# PX4FMUv2_3.net
KiCad netlist of a schematic drawn in EAGLE
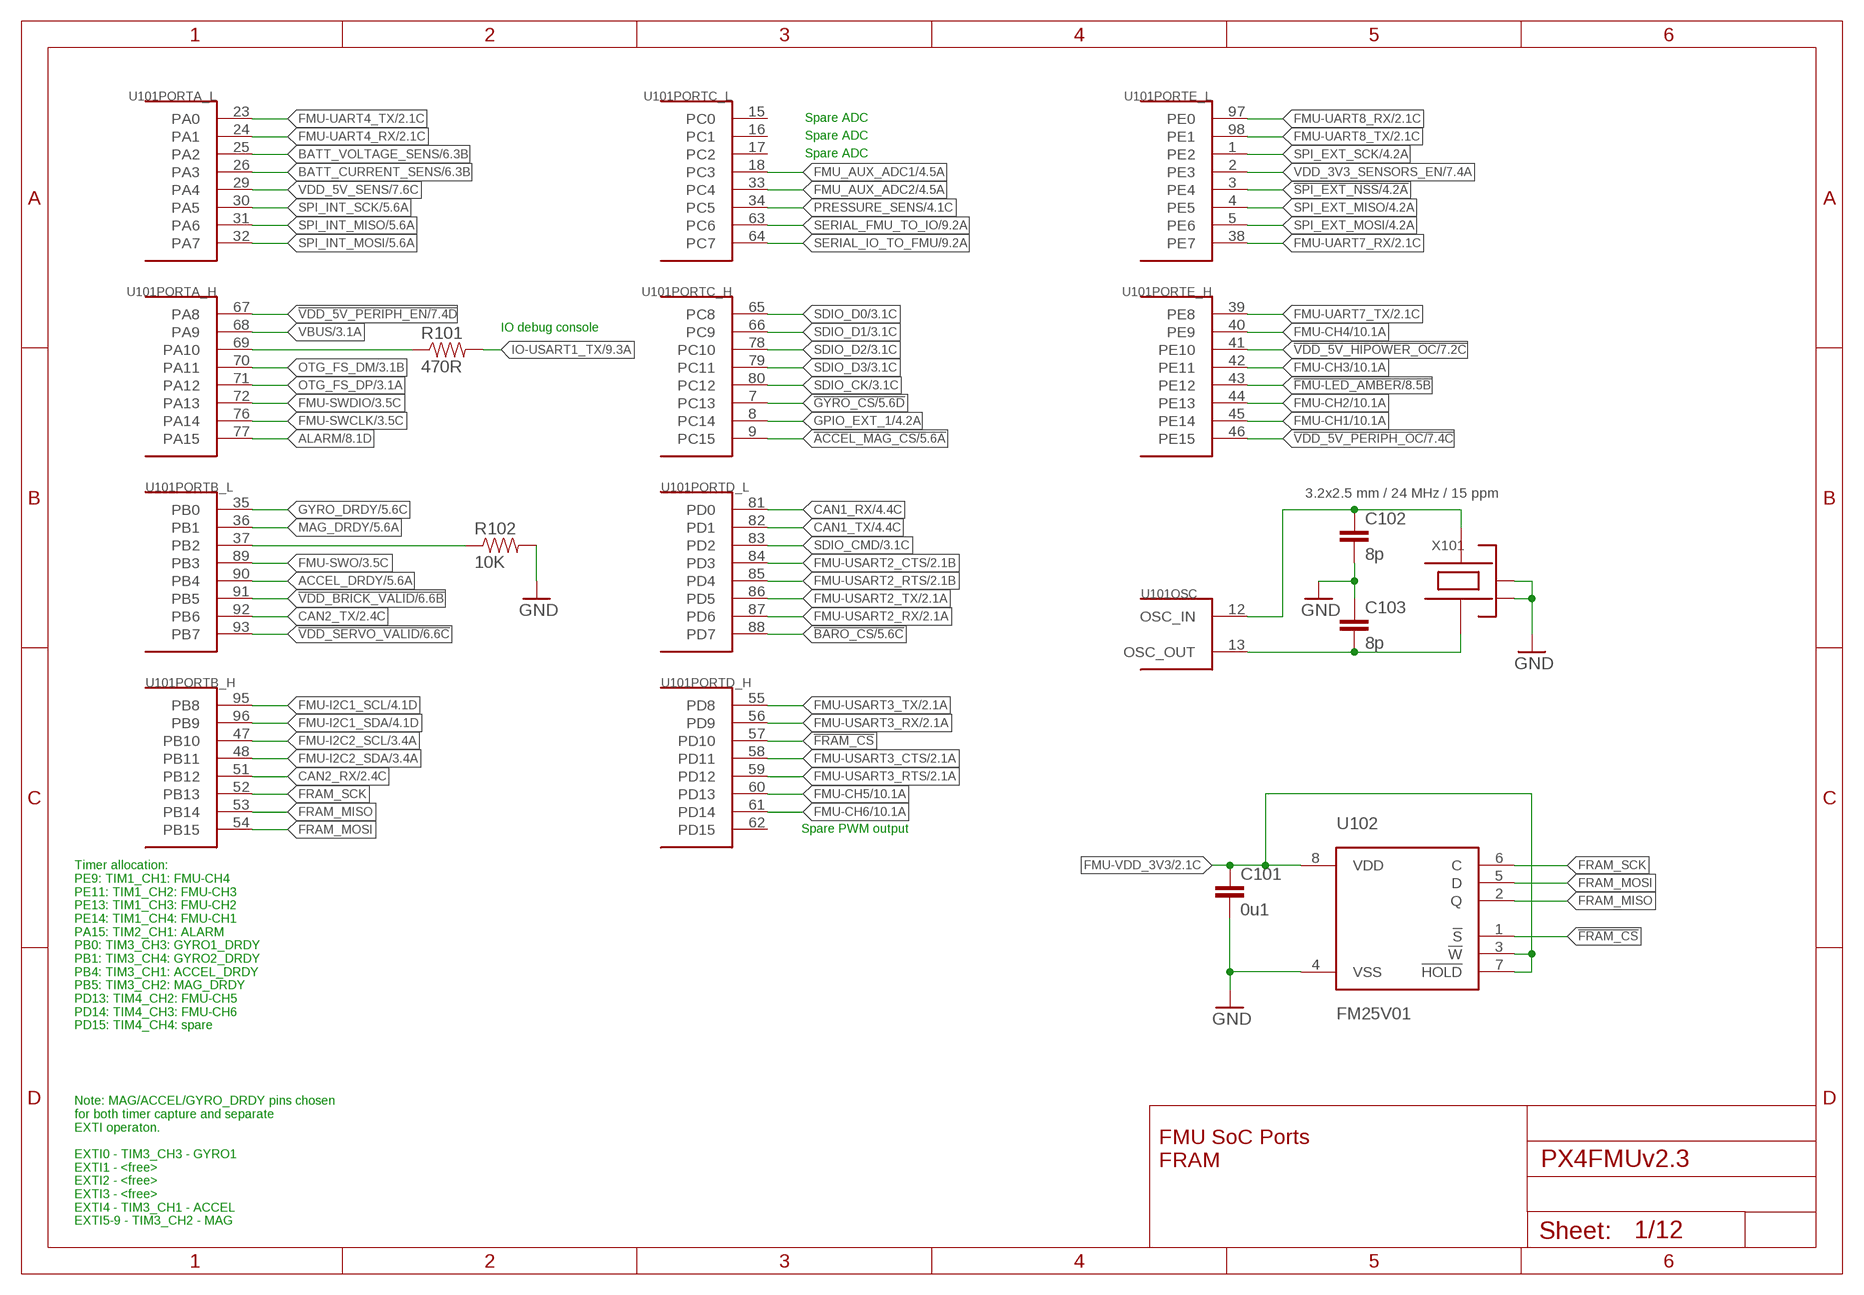
[diagram p0: schematic, sheet 1]
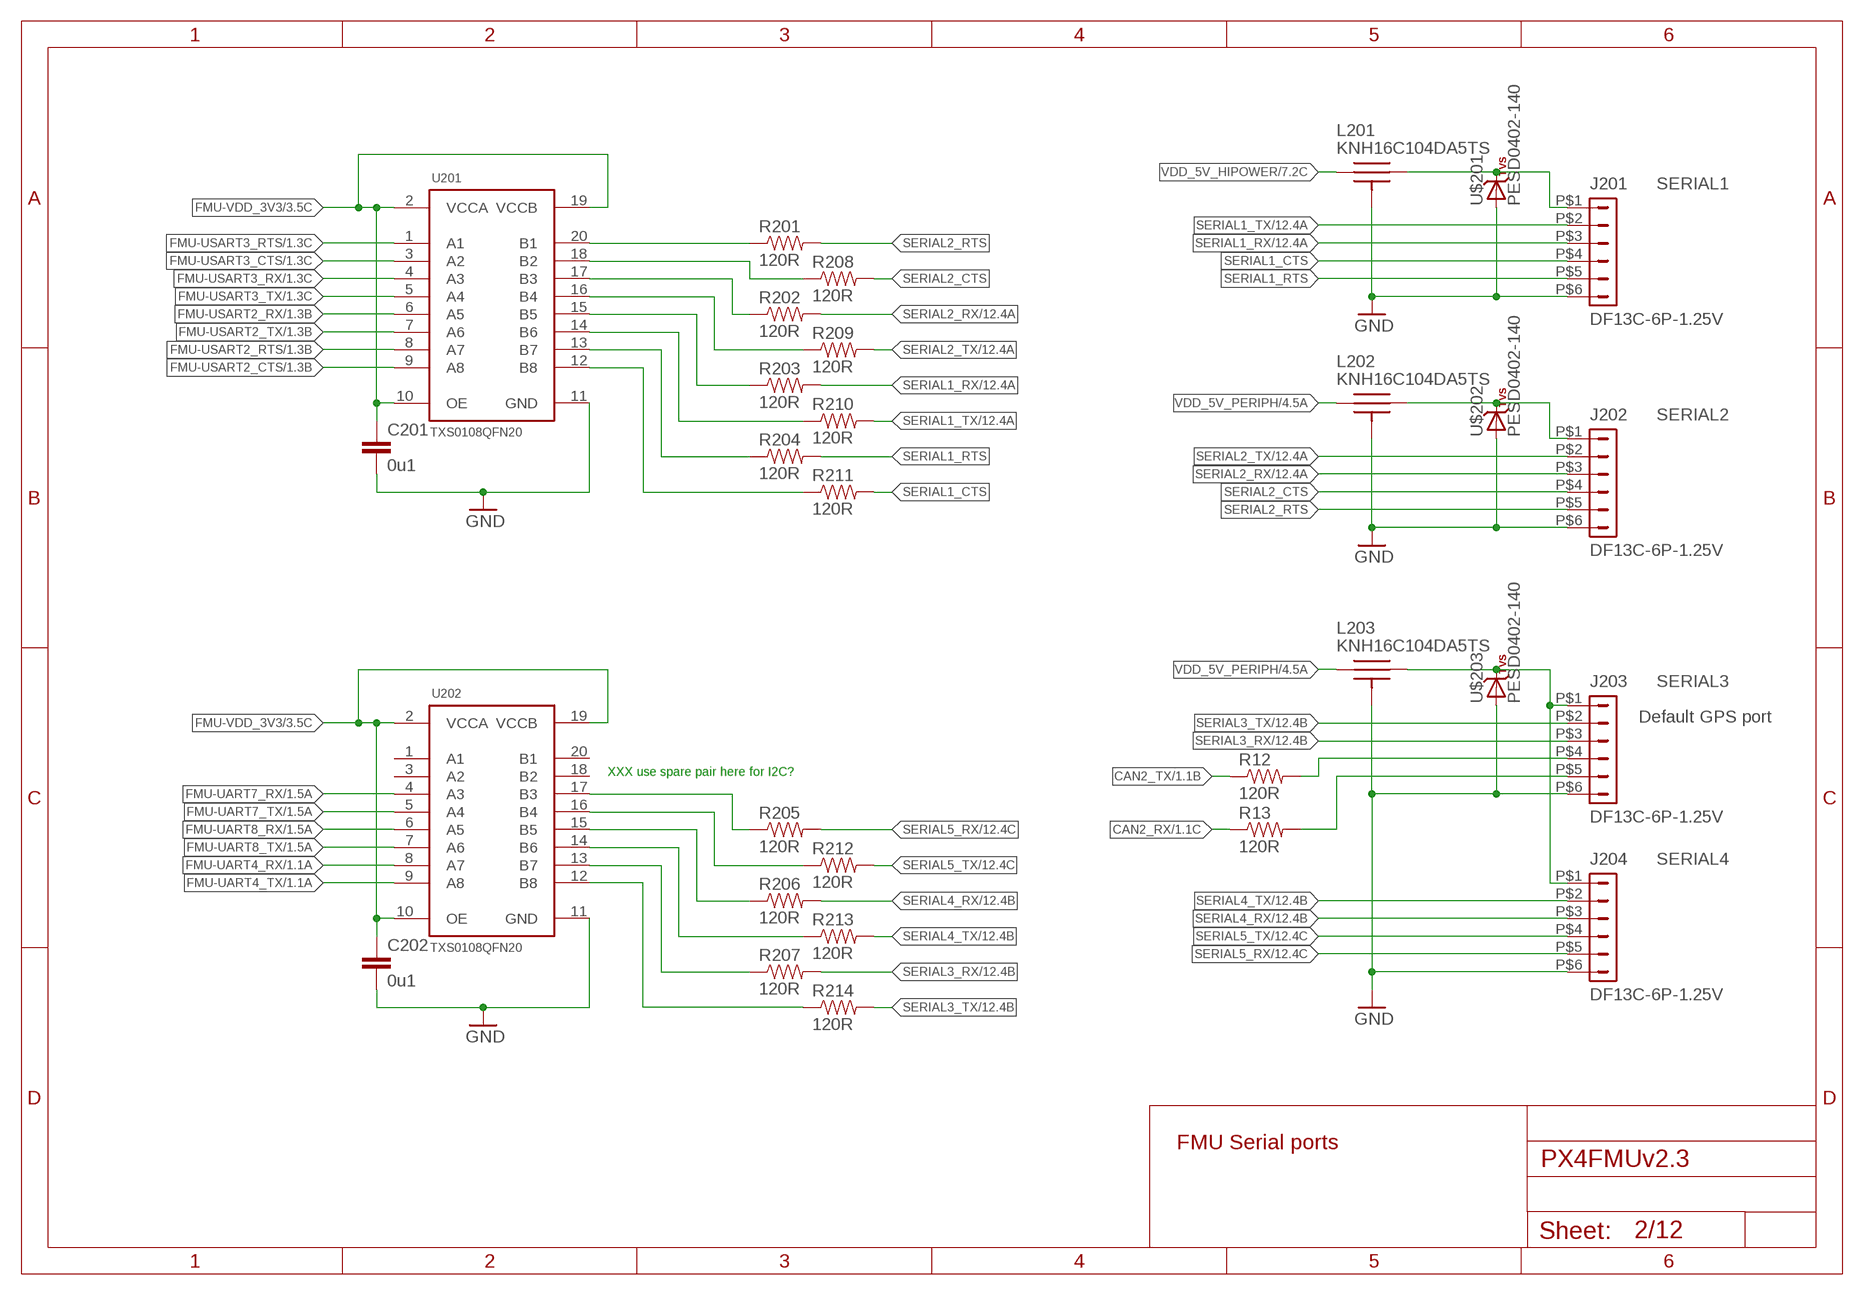
[diagram p1: schematic, sheet 2]
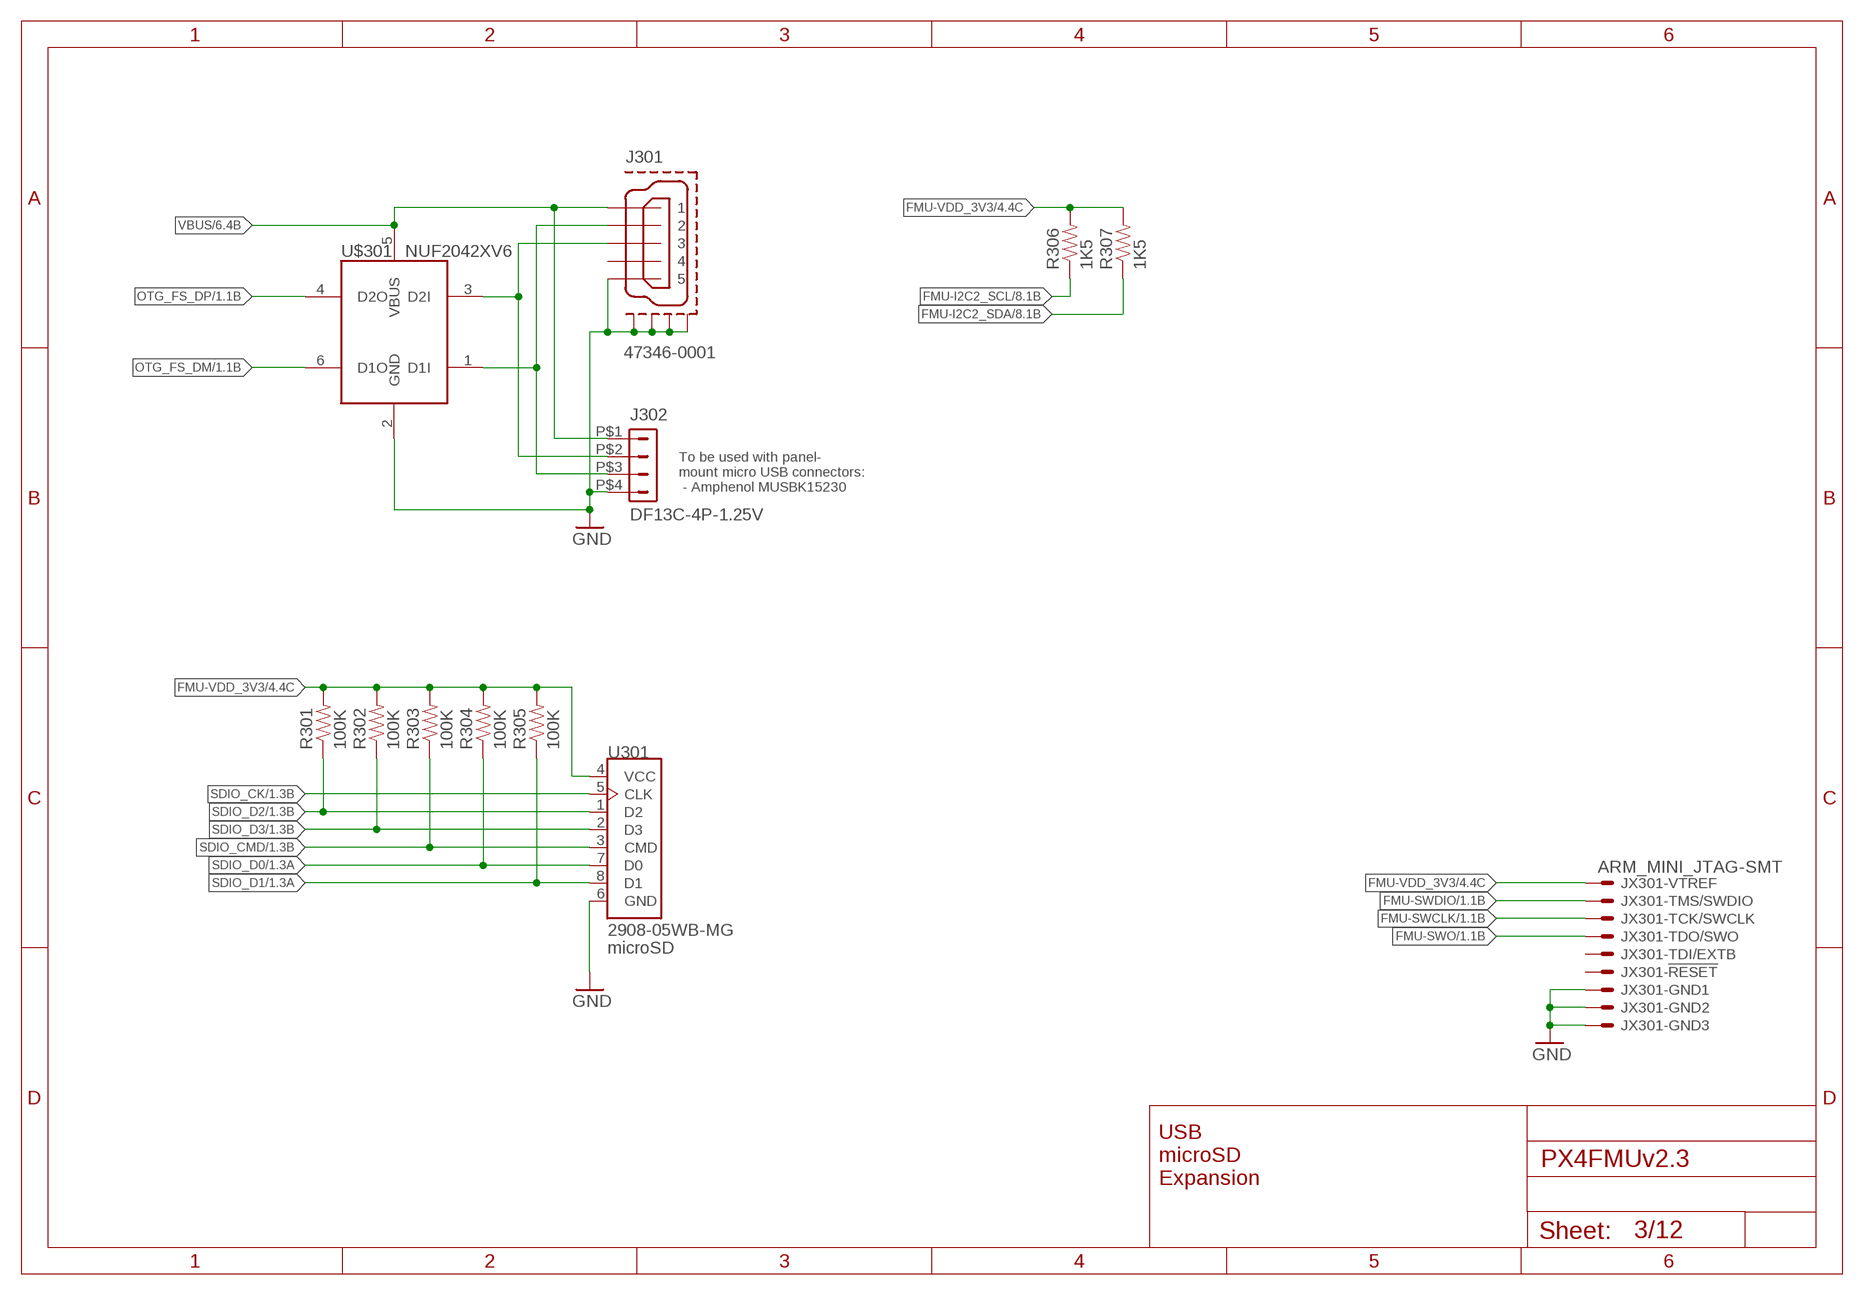
[diagram p2: schematic, sheet 3]
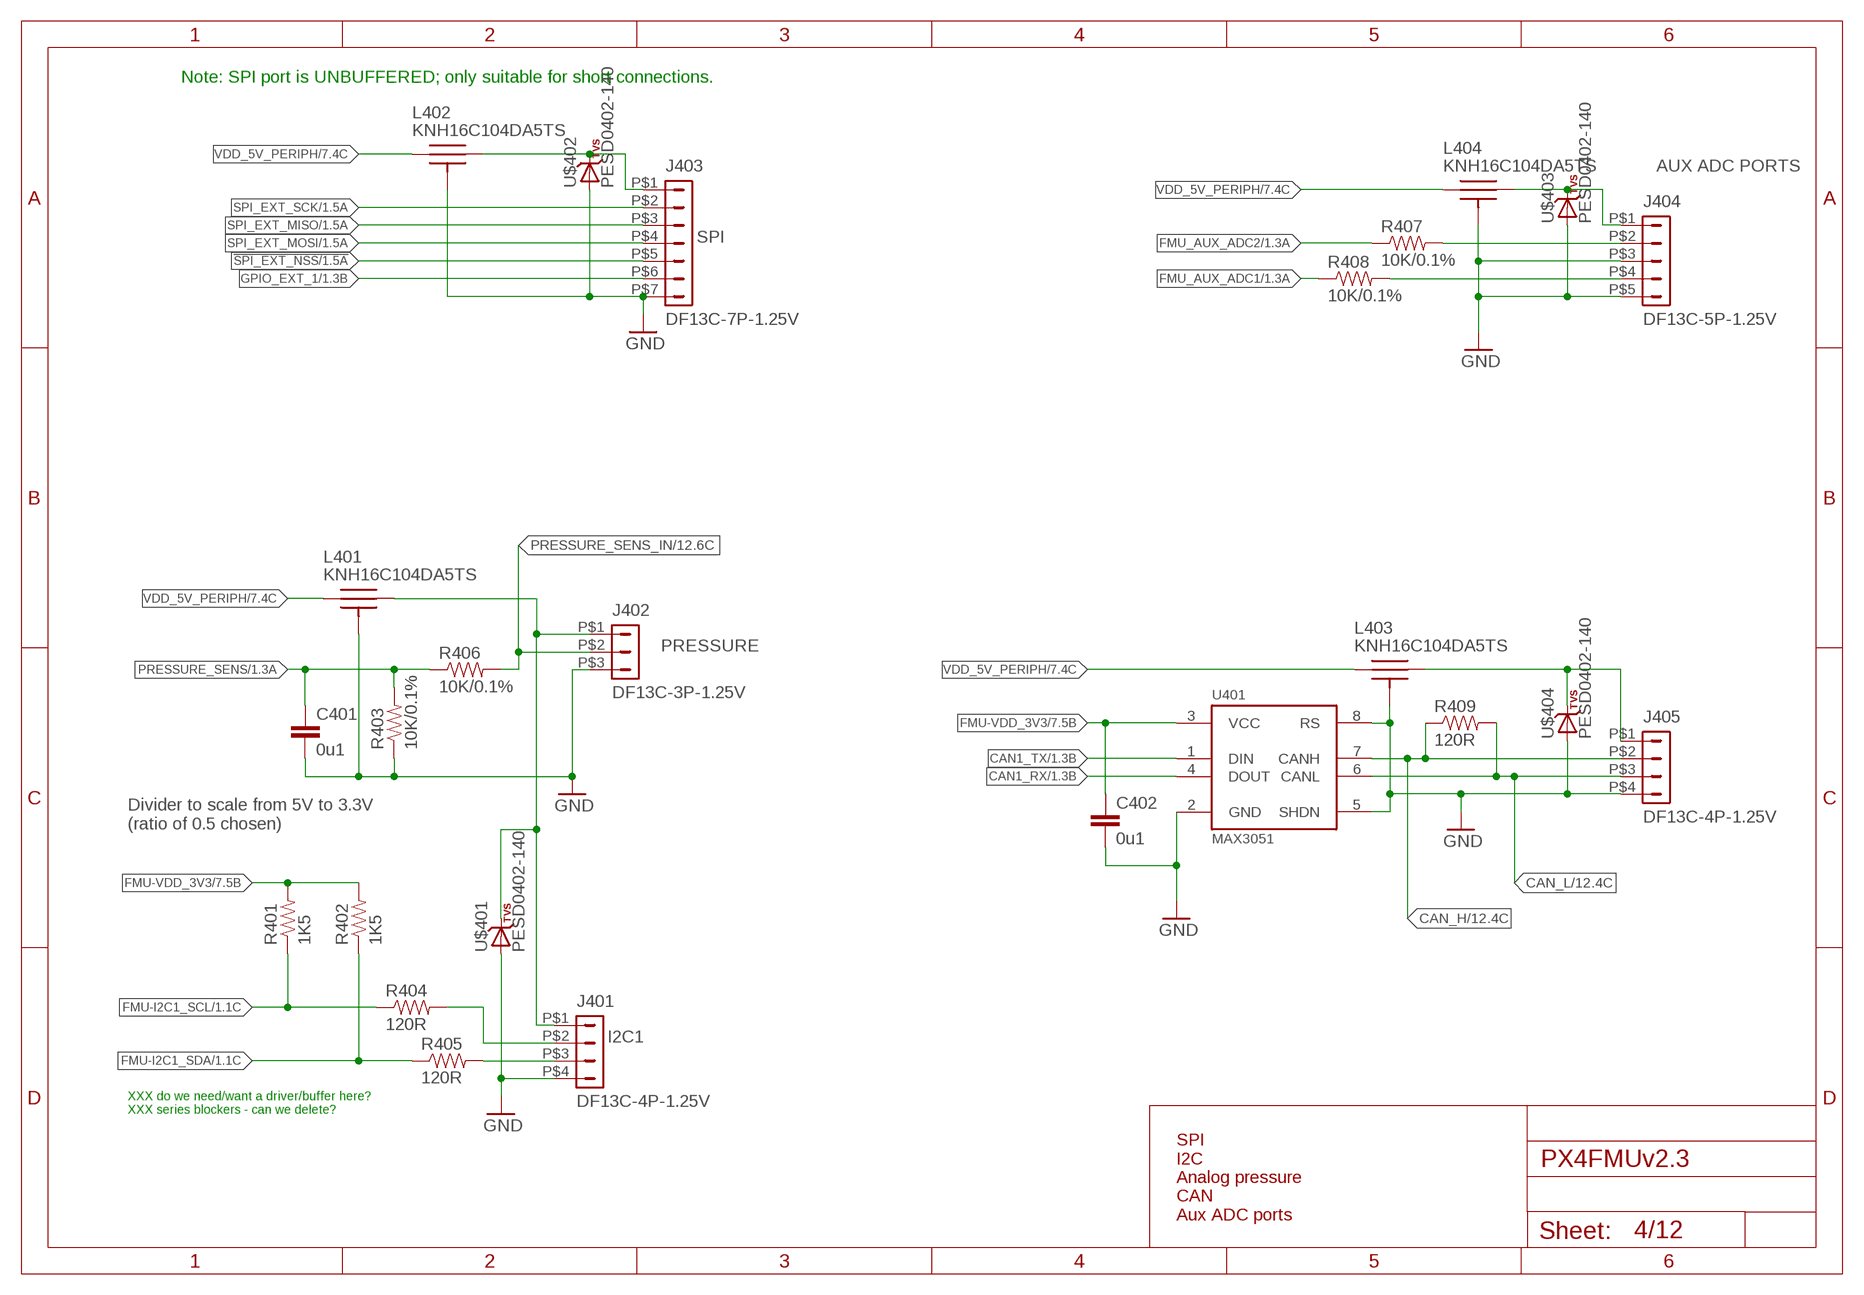
[diagram p3: schematic, sheet 4]
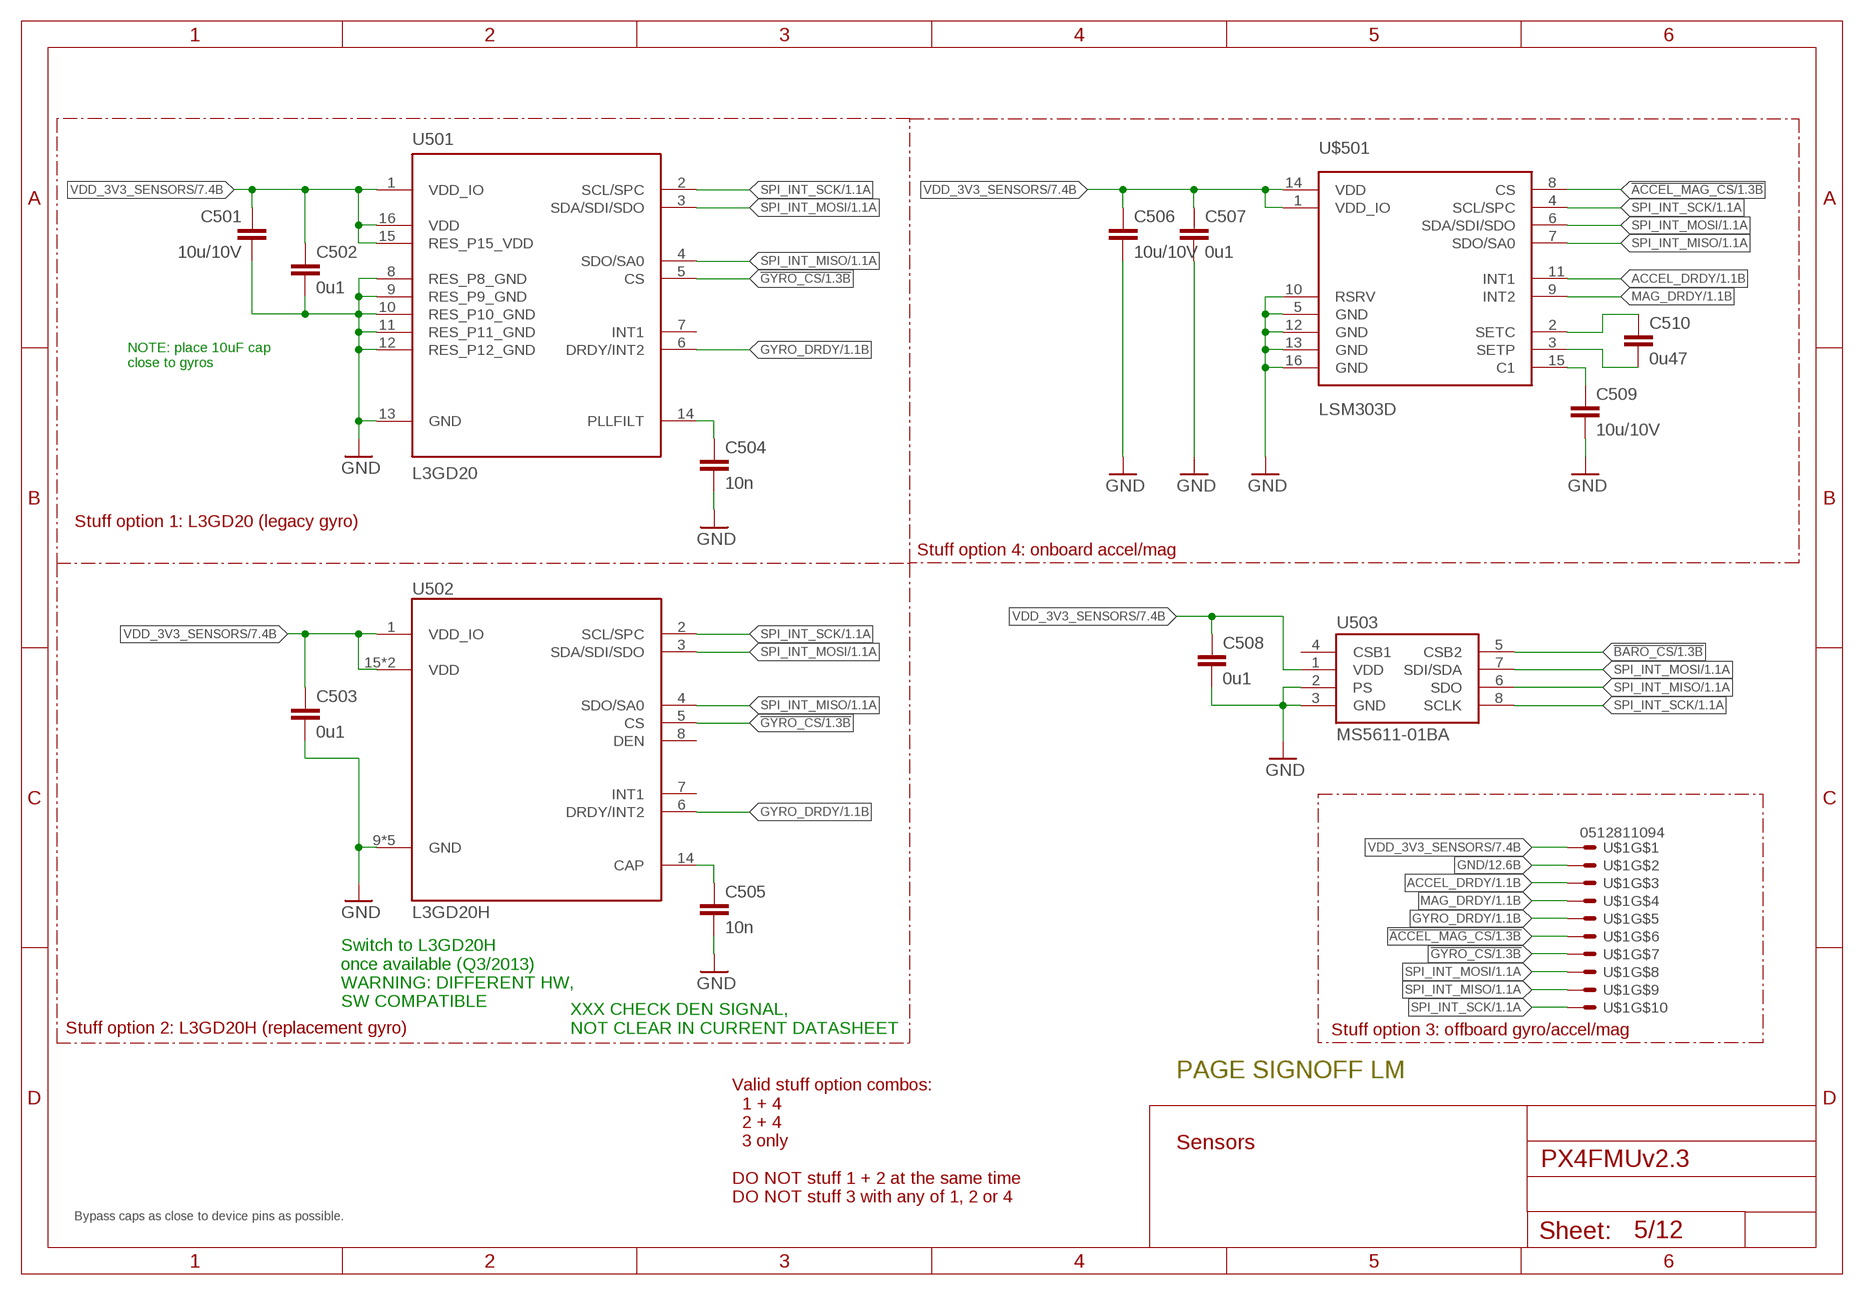
[diagram p4: schematic, sheet 5]
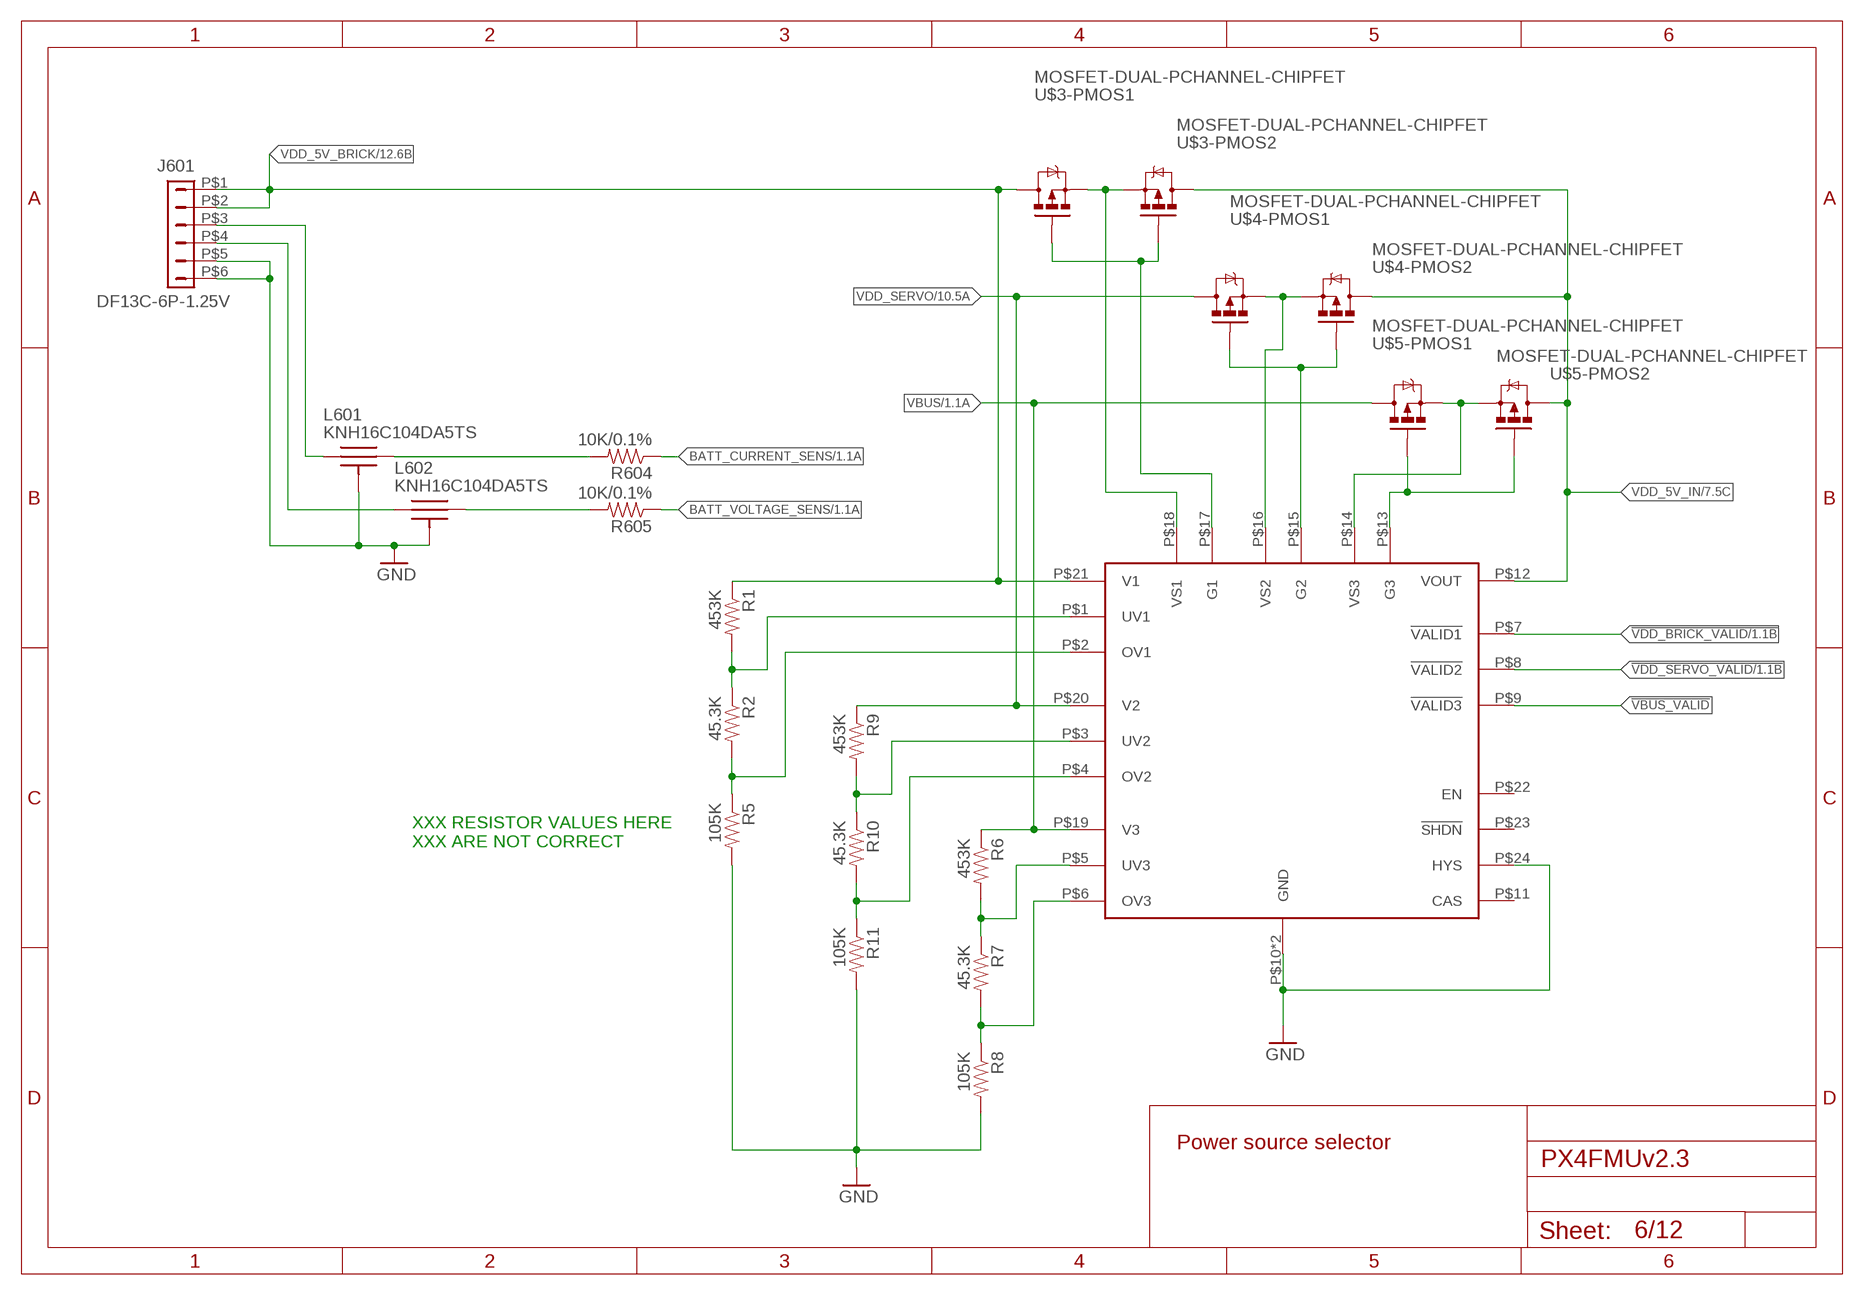
[diagram p5: schematic, sheet 6]
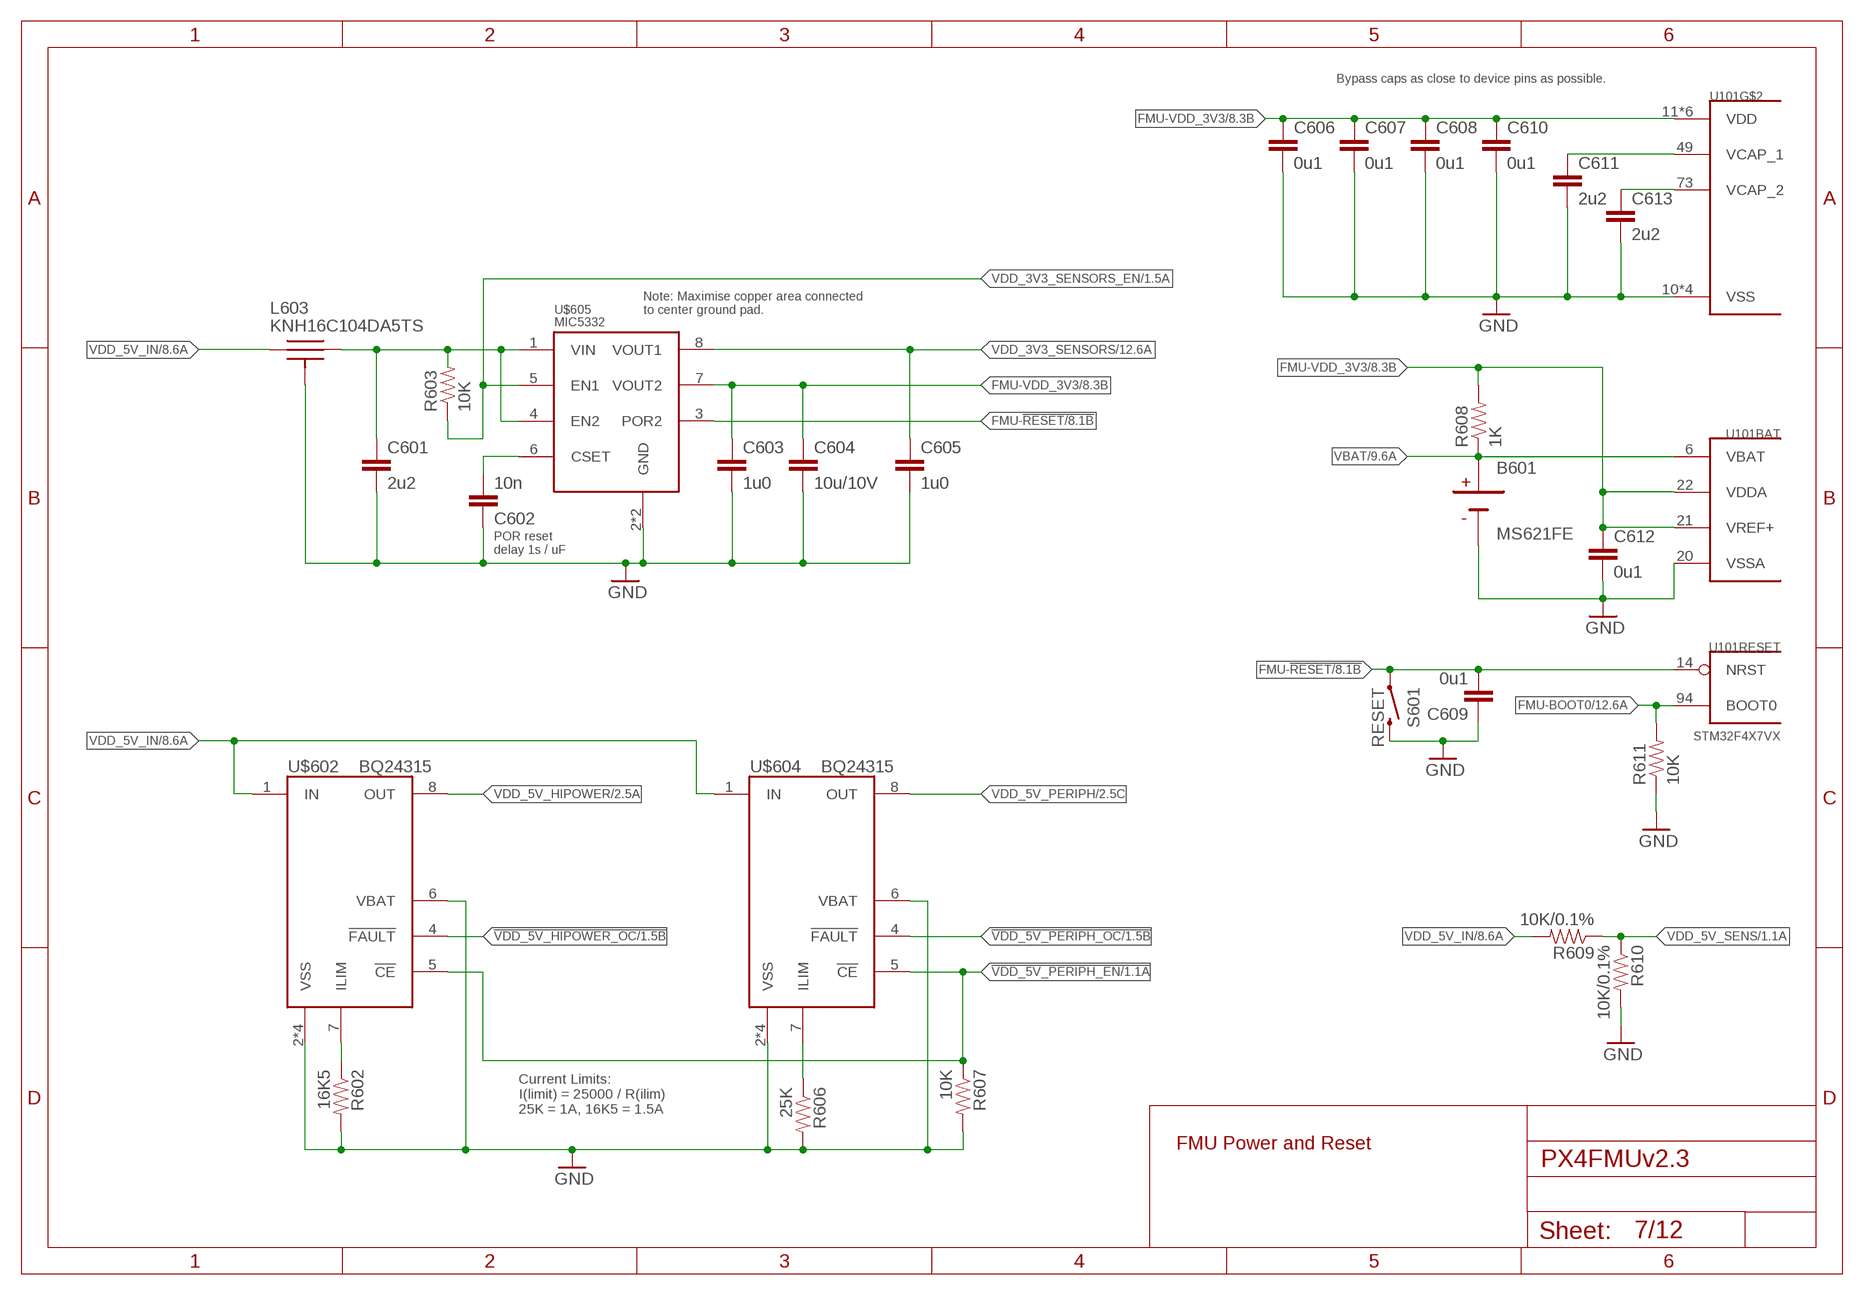
[diagram p6: schematic, sheet 7]
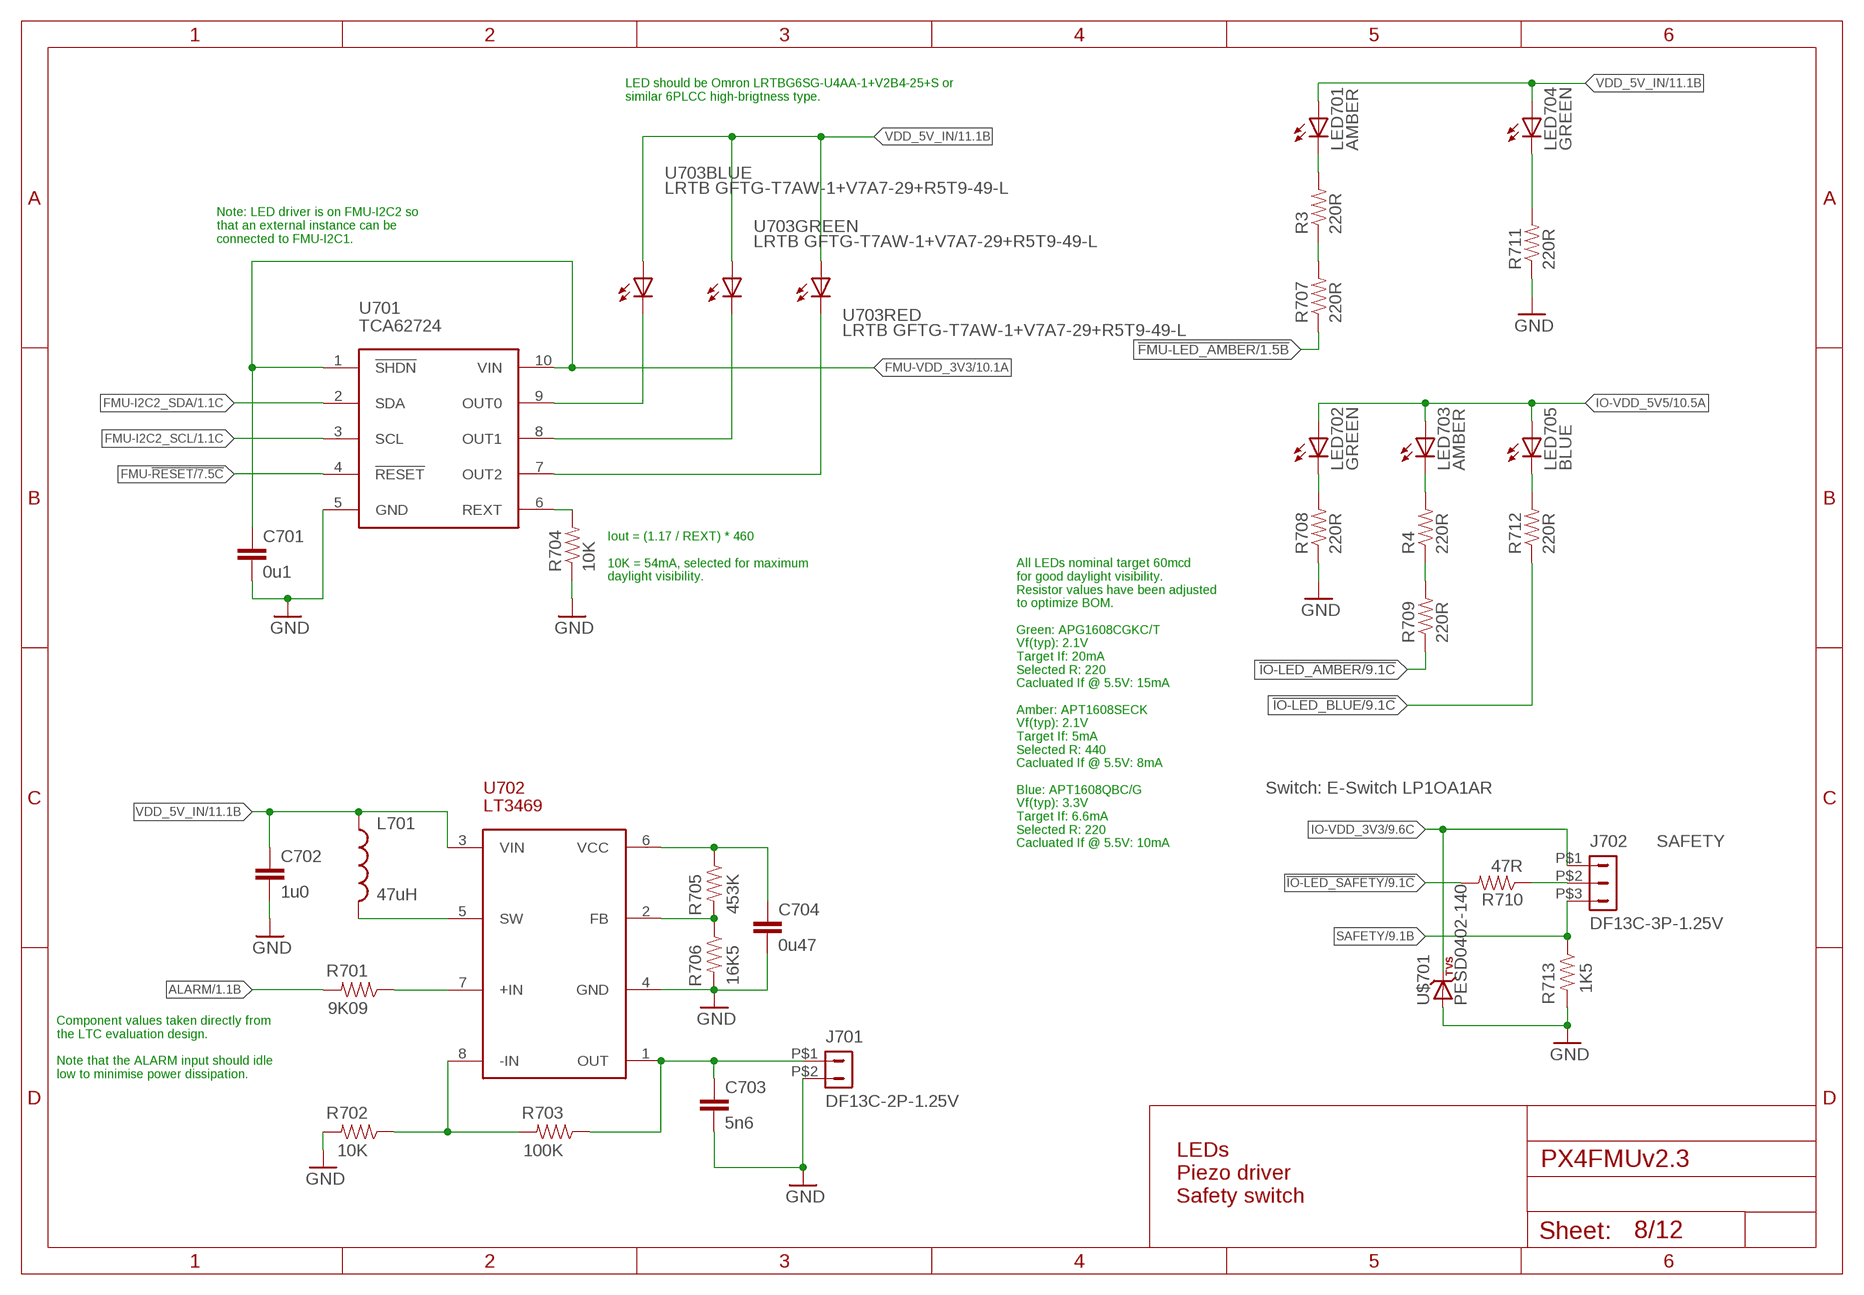
[diagram p7: schematic, sheet 8]
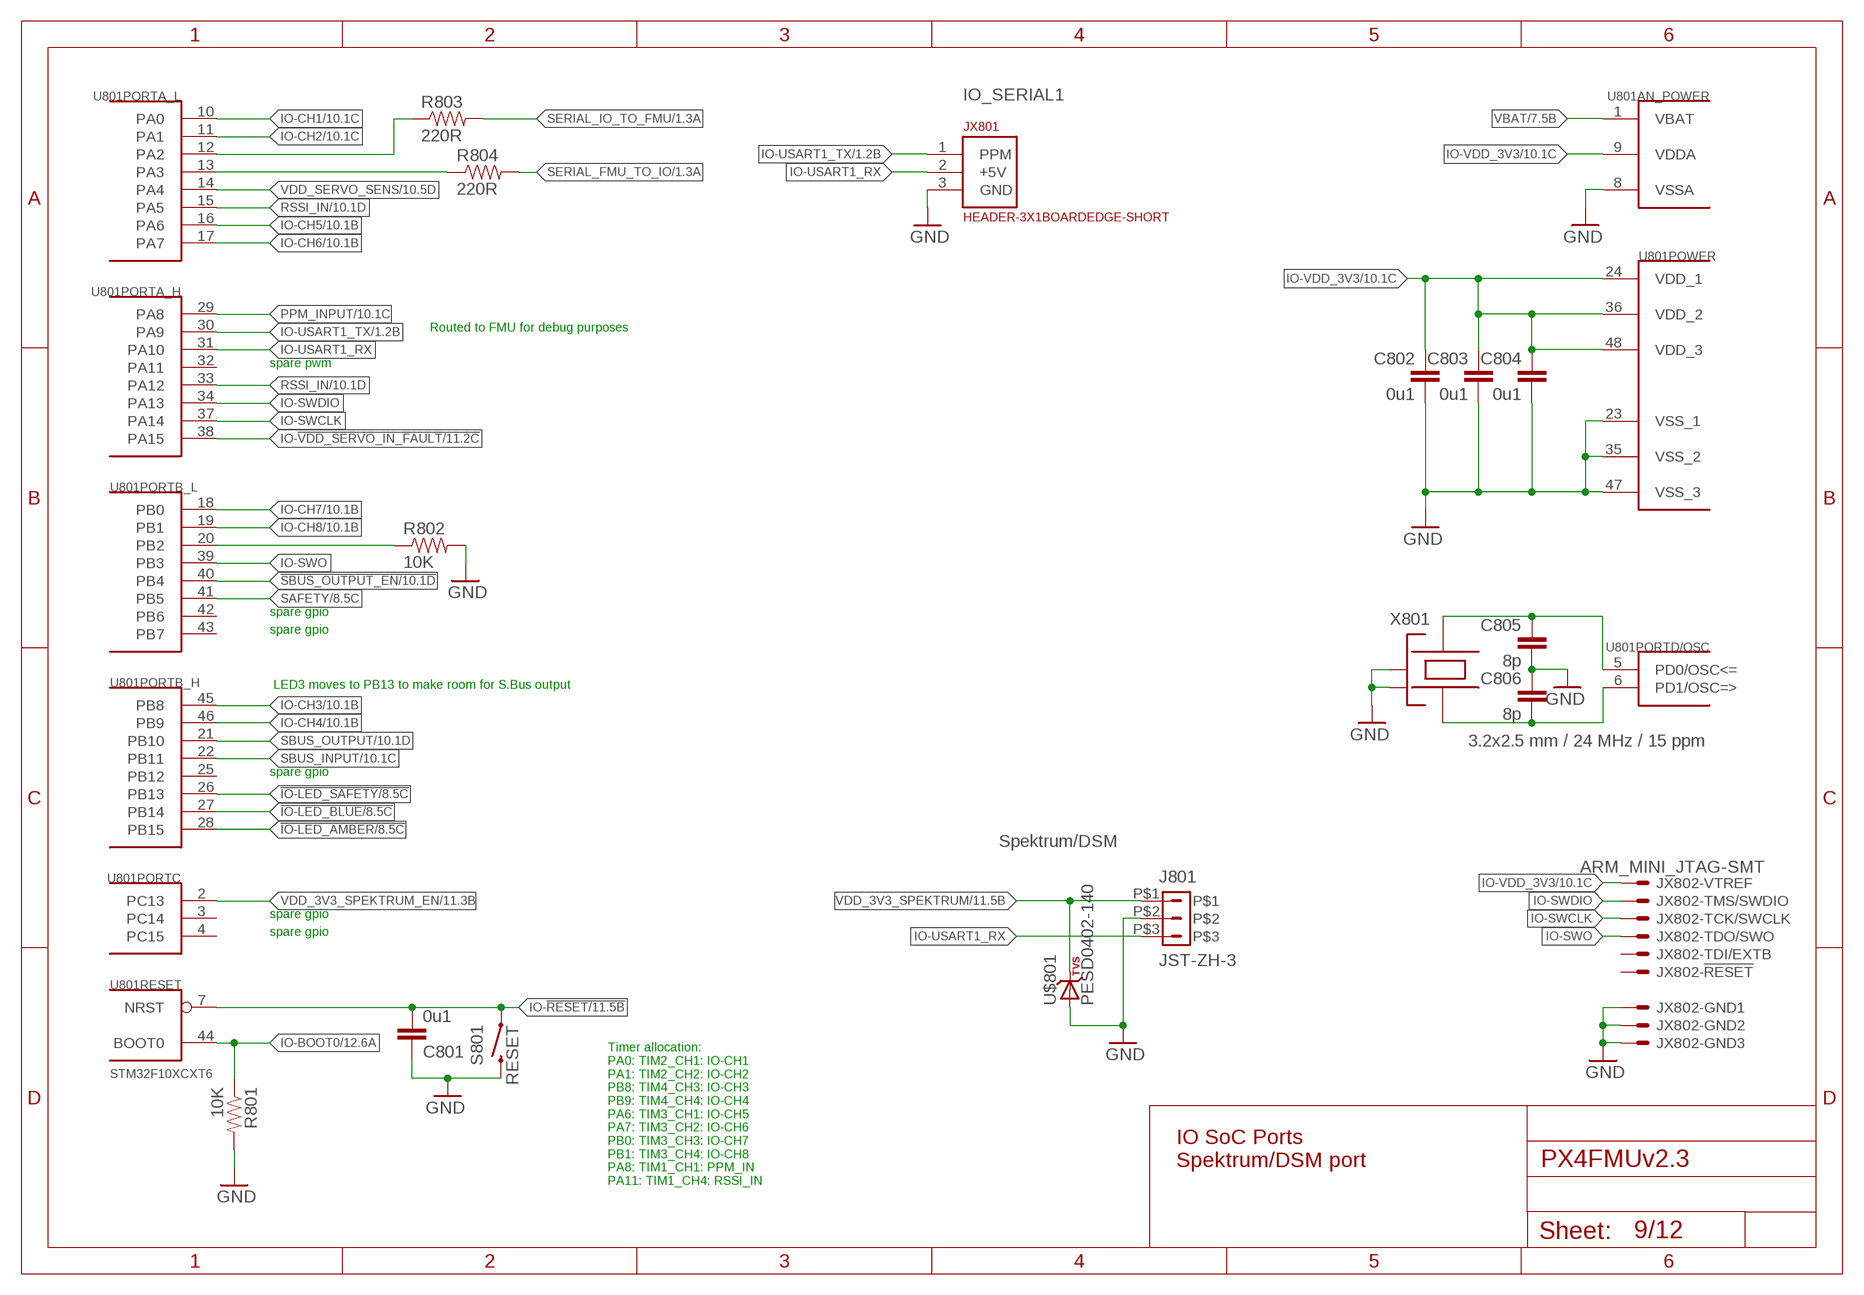
[diagram p8: schematic, sheet 9]
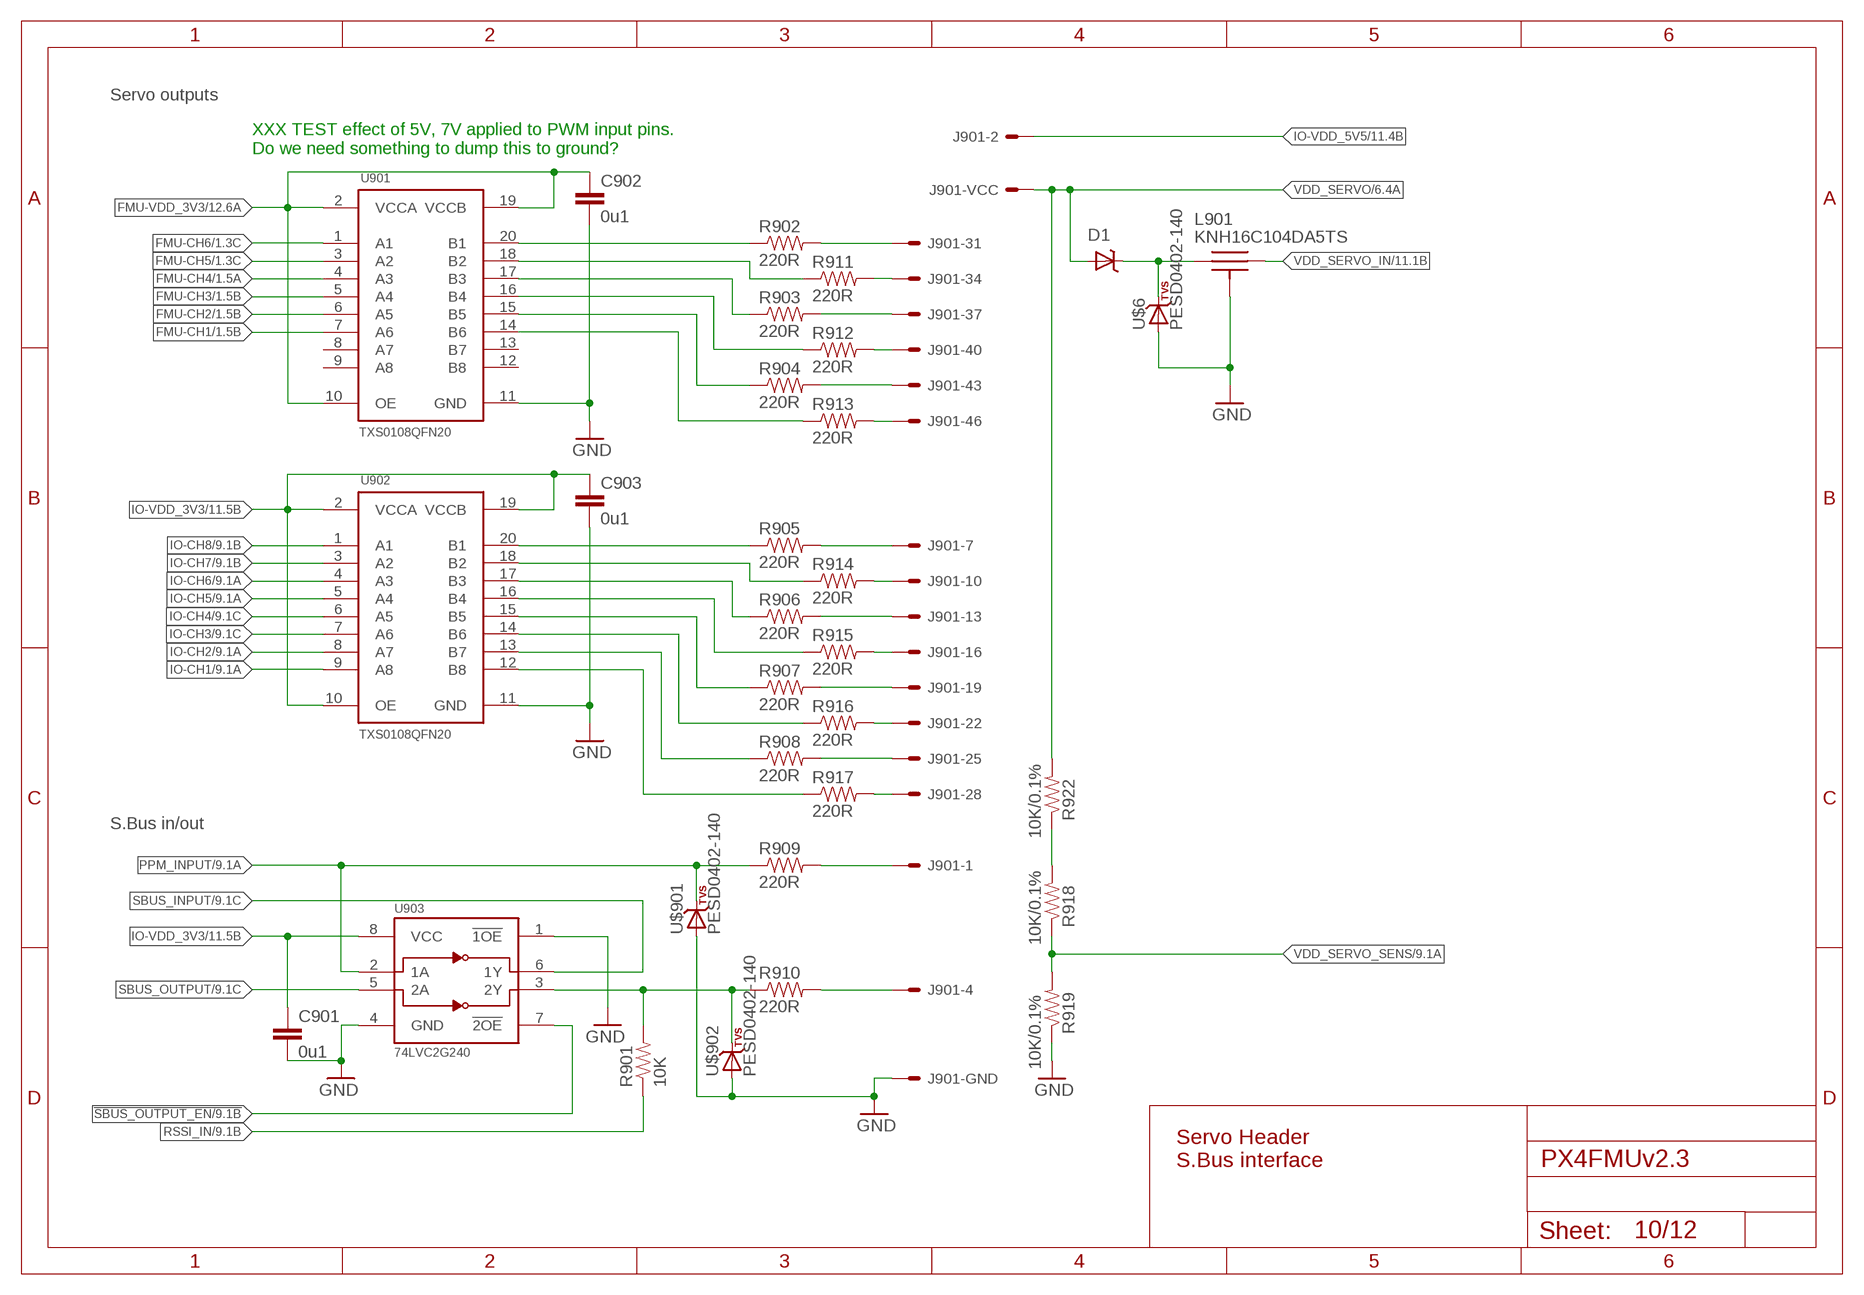
[diagram p9: schematic, sheet 10]
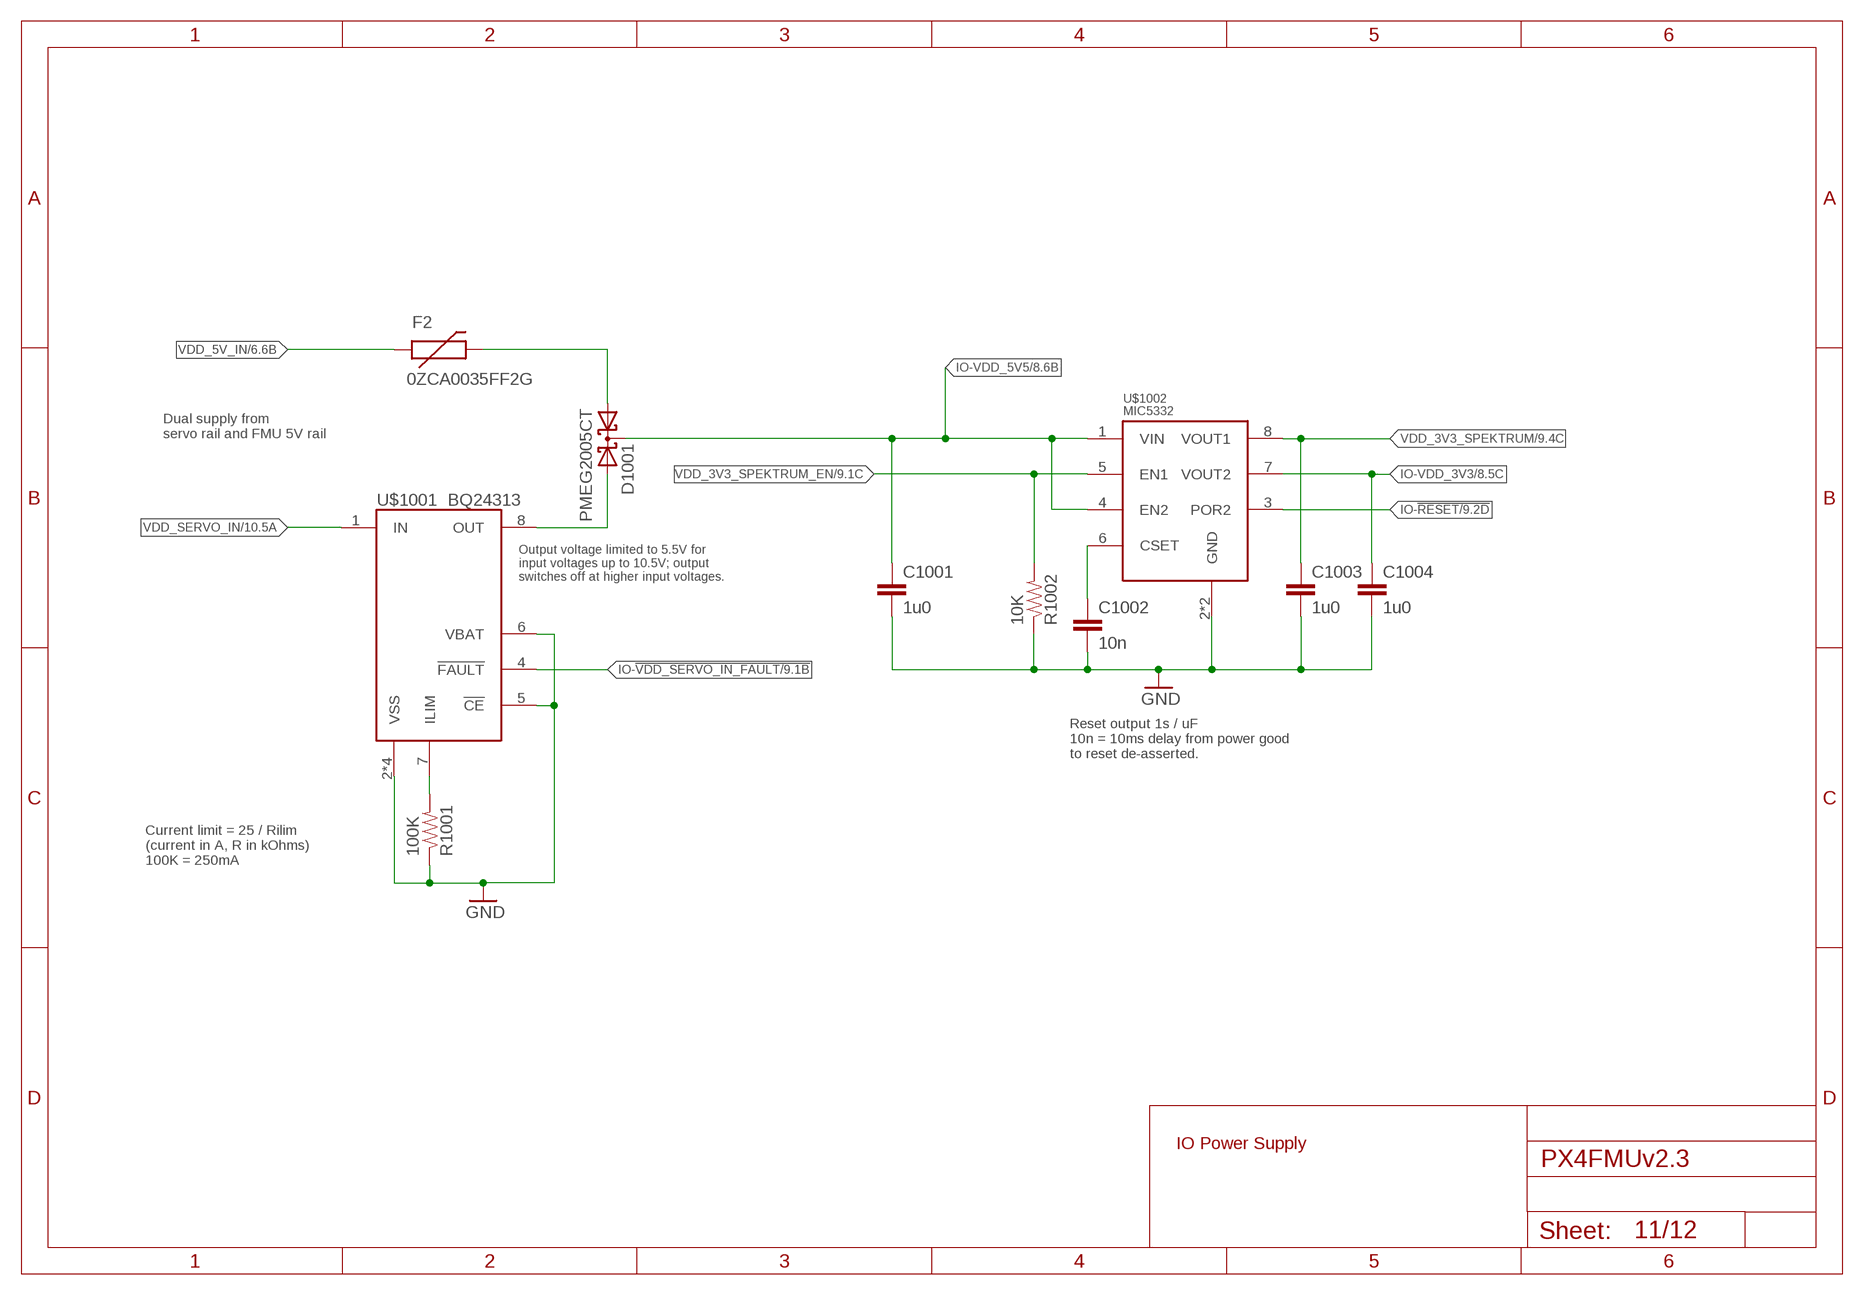
[diagram p10: schematic, sheet 11]
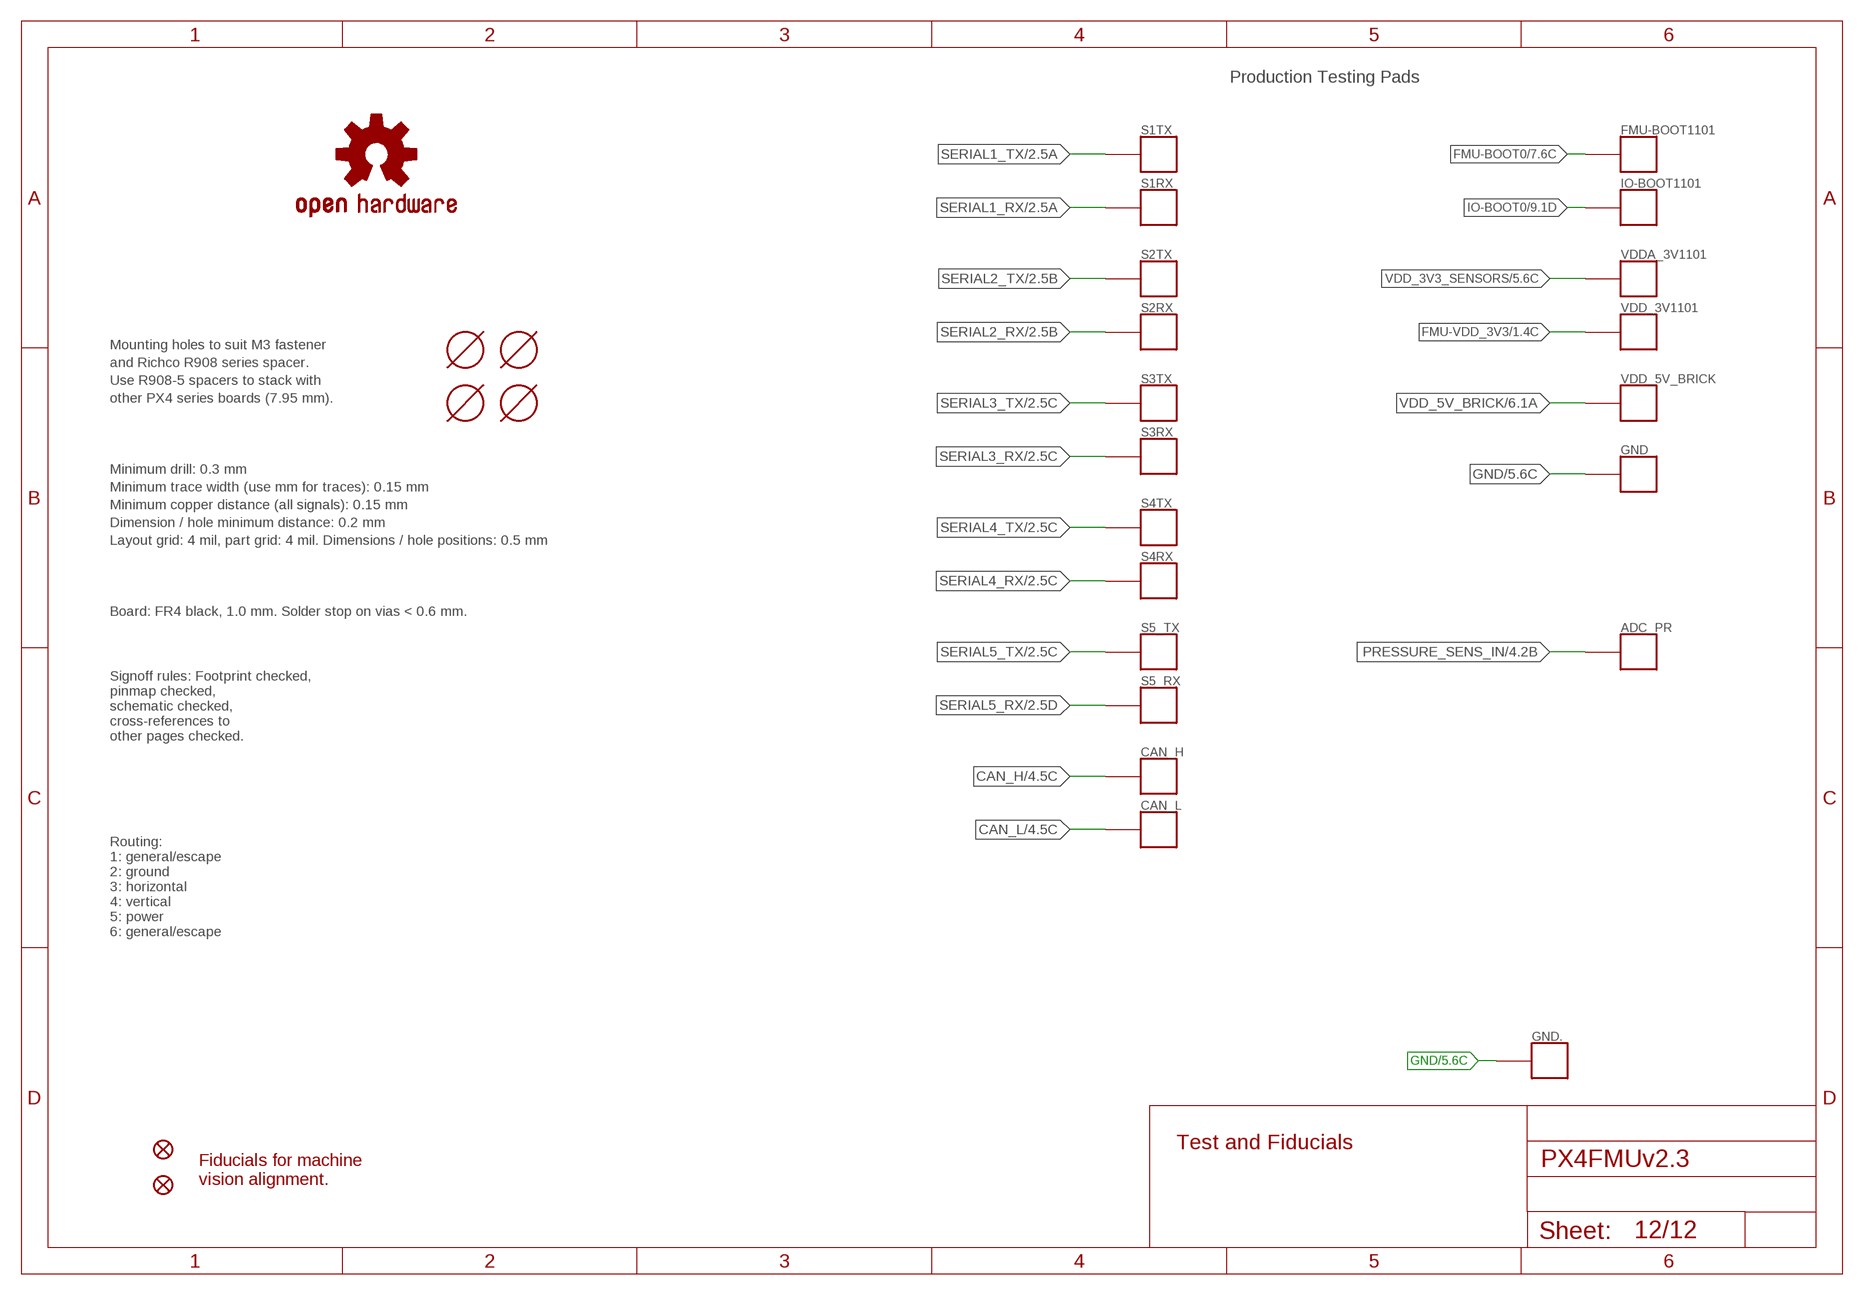
[diagram p11: schematic, sheet 12]

(export (version "E")
  (design (tool "Eeschema 10.0.6"))
  (components
    (comp (ref "C201")
      (value "0u1")
      (footprint "eagle-import:0402-CAP")
      (fields (field (name "PARTNO") "CC0402ZRY5V7BB104"))
      (libsource (lib "eagle-import") (part "CAP0402"))
    )
    (comp (ref "C202")
      (value "0u1")
      (footprint "eagle-import:0402-CAP")
      (fields (field (name "PARTNO") "CC0402ZRY5V7BB104"))
      (libsource (lib "eagle-import") (part "CAP0402"))
    )
    (comp (ref "J201")
      (value "DF13C-6P-1.25V")
      (footprint "eagle-import:DF13C-6P-1.25V")
      (fields (field (name "PARTNO") "DF13C-6P-1.25V(20)"))
      (libsource (lib "eagle-import") (part "DF13-6P-1.25V"))
    )
    (comp (ref "J202")
      (value "DF13C-6P-1.25V")
      (footprint "eagle-import:DF13C-6P-1.25V")
      (fields (field (name "PARTNO") "DF13C-6P-1.25V(20)"))
      (libsource (lib "eagle-import") (part "DF13-6P-1.25V"))
    )
    (comp (ref "J203")
      (value "DF13C-6P-1.25V")
      (footprint "eagle-import:DF13C-6P-1.25V")
      (fields (field (name "PARTNO") "DF13C-6P-1.25V(20)"))
      (libsource (lib "eagle-import") (part "DF13-6P-1.25V"))
    )
    (comp (ref "J204")
      (value "DF13C-6P-1.25V")
      (footprint "eagle-import:DF13C-6P-1.25V")
      (fields (field (name "PARTNO") "DF13C-6P-1.25V(20)"))
      (libsource (lib "eagle-import") (part "DF13-6P-1.25V"))
    )
    (comp (ref "L201")
      (value "KNH16C104DA5TS")
      (footprint "eagle-import:KYOCERA-KNH16-DA")
      (libsource (lib "eagle-import") (part "KNH16C104DA5TS"))
    )
    (comp (ref "L202")
      (value "KNH16C104DA5TS")
      (footprint "eagle-import:KYOCERA-KNH16-DA")
      (libsource (lib "eagle-import") (part "KNH16C104DA5TS"))
    )
    (comp (ref "L203")
      (value "KNH16C104DA5TS")
      (footprint "eagle-import:KYOCERA-KNH16-DA")
      (libsource (lib "eagle-import") (part "KNH16C104DA5TS"))
    )
    (comp (ref "R12")
      (value "120R")
      (footprint "eagle-import:0402-RES")
      (fields (field (name "PARTNO") "RC0402FR-07120RL"))
      (libsource (lib "eagle-import") (part "RESISTOR0402-RES"))
    )
    (comp (ref "R13")
      (value "120R")
      (footprint "eagle-import:0402-RES")
      (fields (field (name "PARTNO") "RC0402FR-07120RL"))
      (libsource (lib "eagle-import") (part "RESISTOR0402-RES"))
    )
    (comp (ref "R201")
      (value "120R")
      (footprint "eagle-import:0402-RES")
      (fields (field (name "PARTNO") "RC0402FR-07120RL"))
      (libsource (lib "eagle-import") (part "RESISTOR0402-RES"))
    )
    (comp (ref "R202")
      (value "120R")
      (footprint "eagle-import:0402-RES")
      (fields (field (name "PARTNO") "RC0402FR-07120RL"))
      (libsource (lib "eagle-import") (part "RESISTOR0402-RES"))
    )
    (comp (ref "R203")
      (value "120R")
      (footprint "eagle-import:0402-RES")
      (fields (field (name "PARTNO") "RC0402FR-07120RL"))
      (libsource (lib "eagle-import") (part "RESISTOR0402-RES"))
    )
    (comp (ref "R204")
      (value "120R")
      (footprint "eagle-import:0402-RES")
      (fields (field (name "PARTNO") "RC0402FR-07120RL"))
      (libsource (lib "eagle-import") (part "RESISTOR0402-RES"))
    )
    (comp (ref "R205")
      (value "120R")
      (footprint "eagle-import:0402-RES")
      (fields (field (name "PARTNO") "RC0402FR-07120RL"))
      (libsource (lib "eagle-import") (part "RESISTOR0402-RES"))
    )
    (comp (ref "R206")
      (value "120R")
      (footprint "eagle-import:0402-RES")
      (fields (field (name "PARTNO") "RC0402FR-07120RL"))
      (libsource (lib "eagle-import") (part "RESISTOR0402-RES"))
    )
    (comp (ref "R207")
      (value "120R")
      (footprint "eagle-import:0402-RES")
      (fields (field (name "PARTNO") "RC0402FR-07120RL"))
      (libsource (lib "eagle-import") (part "RESISTOR0402-RES"))
    )
    (comp (ref "R208")
      (value "120R")
      (footprint "eagle-import:0402-RES")
      (fields (field (name "PARTNO") "RC0402FR-07120RL"))
      (libsource (lib "eagle-import") (part "RESISTOR0402-RES"))
    )
    (comp (ref "R209")
      (value "120R")
      (footprint "eagle-import:0402-RES")
      (fields (field (name "PARTNO") "RC0402FR-07120RL"))
      (libsource (lib "eagle-import") (part "RESISTOR0402-RES"))
    )
    (comp (ref "R210")
      (value "120R")
      (footprint "eagle-import:0402-RES")
      (fields (field (name "PARTNO") "RC0402FR-07120RL"))
      (libsource (lib "eagle-import") (part "RESISTOR0402-RES"))
    )
    (comp (ref "R211")
      (value "120R")
      (footprint "eagle-import:0402-RES")
      (fields (field (name "PARTNO") "RC0402FR-07120RL"))
      (libsource (lib "eagle-import") (part "RESISTOR0402-RES"))
    )
    (comp (ref "R212")
      (value "120R")
      (footprint "eagle-import:0402-RES")
      (fields (field (name "PARTNO") "RC0402FR-07120RL"))
      (libsource (lib "eagle-import") (part "RESISTOR0402-RES"))
    )
    (comp (ref "R213")
      (value "120R")
      (footprint "eagle-import:0402-RES")
      (fields (field (name "PARTNO") "RC0402FR-07120RL"))
      (libsource (lib "eagle-import") (part "RESISTOR0402-RES"))
    )
    (comp (ref "R214")
      (value "120R")
      (footprint "eagle-import:0402-RES")
      (fields (field (name "PARTNO") "RC0402FR-07120RL"))
      (libsource (lib "eagle-import") (part "RESISTOR0402-RES"))
    )
    (comp (ref "U$201")
      (value "PESD0402-140")
      (footprint "eagle-import:0402-TVS")
      (libsource (lib "eagle-import") (part "DIODE-TVS"))
    )
    (comp (ref "U$202")
      (value "PESD0402-140")
      (footprint "eagle-import:0402-TVS")
      (libsource (lib "eagle-import") (part "DIODE-TVS"))
    )
    (comp (ref "U$203")
      (value "PESD0402-140")
      (footprint "eagle-import:0402-TVS")
      (libsource (lib "eagle-import") (part "DIODE-TVS"))
    )
    (comp (ref "U201")
      (value "TXS0108QFN20")
      (footprint "eagle-import:QFN20-RGY")
      (fields (field (name "PARTNO") "TXS0108ERGYR"))
      (libsource (lib "eagle-import") (part "TXS0108QFN20"))
    )
    (comp (ref "U202")
      (value "TXS0108QFN20")
      (footprint "eagle-import:QFN20-RGY")
      (fields (field (name "PARTNO") "TXS0108ERGYR"))
      (libsource (lib "eagle-import") (part "TXS0108QFN20"))
    )
    (comp (ref "C901")
      (value "0u1")
      (footprint "eagle-import:0402-CAP")
      (fields (field (name "PARTNO") "CC0402ZRY5V7BB104"))
      (libsource (lib "eagle-import") (part "CAP0402"))
    )
    (comp (ref "C902")
      (value "0u1")
      (footprint "eagle-import:0402-CAP")
      (fields (field (name "PARTNO") "CC0402ZRY5V7BB104"))
      (libsource (lib "eagle-import") (part "CAP0402"))
    )
    (comp (ref "C903")
      (value "0u1")
      (footprint "eagle-import:0402-CAP")
      (fields (field (name "PARTNO") "CC0402ZRY5V7BB104"))
      (libsource (lib "eagle-import") (part "CAP0402"))
    )
    (comp (ref "D1")
      (value "MSS1P4-M3")
      (footprint "eagle-import:MICROSMP")
      (fields (field (name "PARTNO") "MSS1P4-M3/89A"))
      (libsource (lib "eagle-import") (part "DIODE-SCHOTTKY_MSMP"))
    )
    (comp (ref "J901")
      (value "HEADER-3X163X16RA")
      (footprint "eagle-import:3X16RA")
      (fields (field (name "BOM") "EXCLUDE"))
      (libsource (lib "eagle-import") (part "HEADER-3X163X16RA"))
    )
    (comp (ref "L901")
      (value "KNH16C104DA5TS")
      (footprint "eagle-import:KYOCERA-KNH16-DA")
      (libsource (lib "eagle-import") (part "KNH16C104DA5TS"))
    )
    (comp (ref "R901")
      (value "10K")
      (footprint "eagle-import:0402-RES")
      (fields (field (name "PARTNO") "RC0402FR-0710KL"))
      (libsource (lib "eagle-import") (part "RESISTOR0402-RES"))
    )
    (comp (ref "R902")
      (value "220R")
      (footprint "eagle-import:0402-RES")
      (fields (field (name "PARTNO") "RC0402FR-07220RL"))
      (libsource (lib "eagle-import") (part "RESISTOR0402-RES"))
    )
    (comp (ref "R903")
      (value "220R")
      (footprint "eagle-import:0402-RES")
      (fields (field (name "PARTNO") "RC0402FR-07220RL"))
      (libsource (lib "eagle-import") (part "RESISTOR0402-RES"))
    )
    (comp (ref "R904")
      (value "220R")
      (footprint "eagle-import:0402-RES")
      (fields (field (name "PARTNO") "RC0402FR-07220RL"))
      (libsource (lib "eagle-import") (part "RESISTOR0402-RES"))
    )
    (comp (ref "R905")
      (value "220R")
      (footprint "eagle-import:0402-RES")
      (fields (field (name "PARTNO") "RC0402FR-07220RL"))
      (libsource (lib "eagle-import") (part "RESISTOR0402-RES"))
    )
    (comp (ref "R906")
      (value "220R")
      (footprint "eagle-import:0402-RES")
      (fields (field (name "PARTNO") "RC0402FR-07220RL"))
      (libsource (lib "eagle-import") (part "RESISTOR0402-RES"))
    )
    (comp (ref "R907")
      (value "220R")
      (footprint "eagle-import:0402-RES")
      (fields (field (name "PARTNO") "RC0402FR-07220RL"))
      (libsource (lib "eagle-import") (part "RESISTOR0402-RES"))
    )
    (comp (ref "R908")
      (value "220R")
      (footprint "eagle-import:0402-RES")
      (fields (field (name "PARTNO") "RC0402FR-07220RL"))
      (libsource (lib "eagle-import") (part "RESISTOR0402-RES"))
    )
    (comp (ref "R909")
      (value "220R")
      (footprint "eagle-import:0402-RES")
      (fields (field (name "PARTNO") "RC0402FR-07220RL"))
      (libsource (lib "eagle-import") (part "RESISTOR0402-RES"))
    )
    (comp (ref "R910")
      (value "220R")
      (footprint "eagle-import:0402-RES")
      (fields (field (name "PARTNO") "RC0402FR-07220RL"))
      (libsource (lib "eagle-import") (part "RESISTOR0402-RES"))
    )
    (comp (ref "R911")
      (value "220R")
      (footprint "eagle-import:0402-RES")
      (fields (field (name "PARTNO") "RC0402FR-07220RL"))
      (libsource (lib "eagle-import") (part "RESISTOR0402-RES"))
    )
    (comp (ref "R912")
      (value "220R")
      (footprint "eagle-import:0402-RES")
      (fields (field (name "PARTNO") "RC0402FR-07220RL"))
      (libsource (lib "eagle-import") (part "RESISTOR0402-RES"))
    )
    (comp (ref "R913")
      (value "220R")
      (footprint "eagle-import:0402-RES")
      (fields (field (name "PARTNO") "RC0402FR-07220RL"))
      (libsource (lib "eagle-import") (part "RESISTOR0402-RES"))
    )
    (comp (ref "R914")
      (value "220R")
      (footprint "eagle-import:0402-RES")
      (fields (field (name "PARTNO") "RC0402FR-07220RL"))
      (libsource (lib "eagle-import") (part "RESISTOR0402-RES"))
    )
    (comp (ref "R915")
      (value "220R")
      (footprint "eagle-import:0402-RES")
      (fields (field (name "PARTNO") "RC0402FR-07220RL"))
      (libsource (lib "eagle-import") (part "RESISTOR0402-RES"))
    )
    (comp (ref "R916")
      (value "220R")
      (footprint "eagle-import:0402-RES")
      (fields (field (name "PARTNO") "RC0402FR-07220RL"))
      (libsource (lib "eagle-import") (part "RESISTOR0402-RES"))
    )
    (comp (ref "R917")
      (value "220R")
      (footprint "eagle-import:0402-RES")
      (fields (field (name "PARTNO") "RC0402FR-07220RL"))
      (libsource (lib "eagle-import") (part "RESISTOR0402-RES"))
    )
    (comp (ref "R918")
      (value "10K/0.1%")
      (footprint "eagle-import:0402-RES")
      (fields (field (name "PARTNO") "ERA-2AEB103X"))
      (libsource (lib "eagle-import") (part "RESISTOR0402-RES"))
    )
    (comp (ref "R919")
      (value "10K/0.1%")
      (footprint "eagle-import:0402-RES")
      (fields (field (name "PARTNO") "ERA-2AEB103X"))
      (libsource (lib "eagle-import") (part "RESISTOR0402-RES"))
    )
    (comp (ref "R922")
      (value "10K/0.1%")
      (footprint "eagle-import:0402-RES")
      (fields (field (name "PARTNO") "ERA-2AEB103X"))
      (libsource (lib "eagle-import") (part "RESISTOR0402-RES"))
    )
    (comp (ref "U$6")
      (value "PESD0402-140")
      (footprint "eagle-import:0402-TVS")
      (libsource (lib "eagle-import") (part "DIODE-TVS"))
    )
    (comp (ref "U$901")
      (value "PESD0402-140")
      (footprint "eagle-import:0402-TVS")
      (libsource (lib "eagle-import") (part "DIODE-TVS"))
    )
    (comp (ref "U$902")
      (value "PESD0402-140")
      (footprint "eagle-import:0402-TVS")
      (libsource (lib "eagle-import") (part "DIODE-TVS"))
    )
    (comp (ref "U901")
      (value "TXS0108QFN20")
      (footprint "eagle-import:QFN20-RGY")
      (fields (field (name "PARTNO") "TXS0108ERGYR"))
      (libsource (lib "eagle-import") (part "TXS0108QFN20"))
    )
    (comp (ref "U902")
      (value "TXS0108QFN20")
      (footprint "eagle-import:QFN20-RGY")
      (fields (field (name "PARTNO") "TXS0108ERGYR"))
      (libsource (lib "eagle-import") (part "TXS0108QFN20"))
    )
    (comp (ref "U903")
      (value "74LVC2G240")
      (footprint "eagle-import:TSSOP8_SOT505-2")
      (fields (field (name "PARTNO") "74LVC2G240DP,125"))
      (libsource (lib "eagle-import") (part "74LVC2G240-TSSOP-8"))
    )
    (comp (ref "C401")
      (value "0u1")
      (footprint "eagle-import:0402-CAP")
      (fields (field (name "PARTNO") "CC0402ZRY5V7BB104"))
      (libsource (lib "eagle-import") (part "CAP0402"))
    )
    (comp (ref "C402")
      (value "0u1")
      (footprint "eagle-import:0402-CAP")
      (fields (field (name "PARTNO") "CC0402ZRY5V7BB104"))
      (libsource (lib "eagle-import") (part "CAP0402"))
    )
    (comp (ref "J401")
      (value "DF13C-4P-1.25V")
      (footprint "eagle-import:DF13C-4P-1.25V")
      (fields (field (name "PARTNO") "DF13C-4P-1.25V(20)"))
      (libsource (lib "eagle-import") (part "DF13-4P-1.25V"))
    )
    (comp (ref "J402")
      (value "DF13C-3P-1.25V")
      (footprint "eagle-import:DF13C-3P-1.25V")
      (fields (field (name "PARTNO") "DF13C-3P-1.25V(20)"))
      (libsource (lib "eagle-import") (part "DF13-3P-1.25V"))
    )
    (comp (ref "J403")
      (value "DF13C-7P-1.25V")
      (footprint "eagle-import:DF13C-7P-1.25V")
      (fields (field (name "PARTNO") "DF13C-7P-1.25V(20)"))
      (libsource (lib "eagle-import") (part "DF13-7P-1.25V"))
    )
    (comp (ref "J404")
      (value "DF13C-5P-1.25V")
      (footprint "eagle-import:DF13C-5P-1.25V")
      (fields (field (name "PARTNO") "DF13C-5P-1.25V(20)"))
      (libsource (lib "eagle-import") (part "DF13-5P-1.25V"))
    )
    (comp (ref "J405")
      (value "DF13C-4P-1.25V")
      (footprint "eagle-import:DF13C-4P-1.25V")
      (fields (field (name "PARTNO") "DF13C-4P-1.25V(20)"))
      (libsource (lib "eagle-import") (part "DF13-4P-1.25V"))
    )
    (comp (ref "L401")
      (value "KNH16C104DA5TS")
      (footprint "eagle-import:KYOCERA-KNH16-DA")
      (libsource (lib "eagle-import") (part "KNH16C104DA5TS"))
    )
    (comp (ref "L402")
      (value "KNH16C104DA5TS")
      (footprint "eagle-import:KYOCERA-KNH16-DA")
      (libsource (lib "eagle-import") (part "KNH16C104DA5TS"))
    )
    (comp (ref "L403")
      (value "KNH16C104DA5TS")
      (footprint "eagle-import:KYOCERA-KNH16-DA")
      (libsource (lib "eagle-import") (part "KNH16C104DA5TS"))
    )
    (comp (ref "L404")
      (value "KNH16C104DA5TS")
      (footprint "eagle-import:KYOCERA-KNH16-DA")
      (libsource (lib "eagle-import") (part "KNH16C104DA5TS"))
    )
    (comp (ref "R401")
      (value "1K5")
      (footprint "eagle-import:0402-RES")
      (fields (field (name "PARTNO") "RC0402FR-071K5L"))
      (libsource (lib "eagle-import") (part "RESISTOR0402-RES"))
    )
    (comp (ref "R402")
      (value "1K5")
      (footprint "eagle-import:0402-RES")
      (fields (field (name "PARTNO") "RC0402FR-071K5L"))
      (libsource (lib "eagle-import") (part "RESISTOR0402-RES"))
    )
    (comp (ref "R403")
      (value "10K/0.1%")
      (footprint "eagle-import:0402-RES")
      (fields (field (name "PARTNO") "ERA-2AEB103X"))
      (libsource (lib "eagle-import") (part "RESISTOR0402-RES"))
    )
    (comp (ref "R404")
      (value "120R")
      (footprint "eagle-import:0402-RES")
      (fields (field (name "PARTNO") "RC0402FR-07120RL"))
      (libsource (lib "eagle-import") (part "RESISTOR0402-RES"))
    )
    (comp (ref "R405")
      (value "120R")
      (footprint "eagle-import:0402-RES")
      (fields (field (name "PARTNO") "RC0402FR-07120RL"))
      (libsource (lib "eagle-import") (part "RESISTOR0402-RES"))
    )
    (comp (ref "R406")
      (value "10K/0.1%")
      (footprint "eagle-import:0402-RES")
      (fields (field (name "PARTNO") "ERA-2AEB103X"))
      (libsource (lib "eagle-import") (part "RESISTOR0402-RES"))
    )
    (comp (ref "R407")
      (value "10K/0.1%")
      (footprint "eagle-import:0402-RES")
      (fields (field (name "PARTNO") "ERA-2AEB103X"))
      (libsource (lib "eagle-import") (part "RESISTOR0402-RES"))
    )
    (comp (ref "R408")
      (value "10K/0.1%")
      (footprint "eagle-import:0402-RES")
      (fields (field (name "PARTNO") "ERA-2AEB103X"))
      (libsource (lib "eagle-import") (part "RESISTOR0402-RES"))
    )
    (comp (ref "R409")
      (value "120R")
      (footprint "eagle-import:0402-RES")
      (fields (field (name "PARTNO") "RC0402FR-07120RL"))
      (libsource (lib "eagle-import") (part "RESISTOR0402-RES"))
    )
    (comp (ref "U$401")
      (value "PESD0402-140")
      (footprint "eagle-import:0402-TVS")
      (libsource (lib "eagle-import") (part "DIODE-TVS"))
    )
    (comp (ref "U$402")
      (value "PESD0402-140")
      (footprint "eagle-import:0402-TVS")
      (libsource (lib "eagle-import") (part "DIODE-TVS"))
    )
    (comp (ref "U$403")
      (value "PESD0402-140")
      (footprint "eagle-import:0402-TVS")
      (libsource (lib "eagle-import") (part "DIODE-TVS"))
    )
    (comp (ref "U$404")
      (value "PESD0402-140")
      (footprint "eagle-import:0402-TVS")
      (libsource (lib "eagle-import") (part "DIODE-TVS"))
    )
    (comp (ref "U401")
      (value "MAX3051")
      (footprint "eagle-import:SOT23-8")
      (fields (field (name "PARTNO") "MAX3051EKA"))
      (libsource (lib "eagle-import") (part "MAX3051MAX3051EKA"))
    )
    (comp (ref "ADC_PR")
      (value "PAD.04")
      (footprint "eagle-import:PAD.04X.04")
      (libsource (lib "eagle-import") (part "PAD.04"))
    )
    (comp (ref "CAN_H")
      (value "PAD.04")
      (footprint "eagle-import:PAD.04X.04")
      (libsource (lib "eagle-import") (part "PAD.04"))
    )
    (comp (ref "CAN_L")
      (value "PAD.04")
      (footprint "eagle-import:PAD.04X.04")
      (libsource (lib "eagle-import") (part "PAD.04"))
    )
    (comp (ref "FMU-BOOT1101")
      (value "PAD.04")
      (footprint "eagle-import:PAD.04X.04")
      (libsource (lib "eagle-import") (part "PAD.04"))
    )
    (comp (ref "GND")
      (value "PAD.04")
      (footprint "eagle-import:PAD.04X.04")
      (libsource (lib "eagle-import") (part "PAD.04"))
    )
    (comp (ref "GND.")
      (value "PAD.04")
      (footprint "eagle-import:PAD.04X.04")
      (libsource (lib "eagle-import") (part "PAD.04"))
    )
    (comp (ref "IO-BOOT1101")
      (value "PAD.04")
      (footprint "eagle-import:PAD.04X.04")
      (libsource (lib "eagle-import") (part "PAD.04"))
    )
    (comp (ref "JP1")
      (value "FIDUCIAL1.5X3")
      (footprint "eagle-import:FIDUCIAL-1.5X3")
      (libsource (lib "eagle-import") (part "FIDUCIAL1.5X3"))
    )
    (comp (ref "JP2")
      (value "FIDUCIAL1.5X3")
      (footprint "eagle-import:FIDUCIAL-1.5X3")
      (libsource (lib "eagle-import") (part "FIDUCIAL1.5X3"))
    )
    (comp (ref "M3_MOUNT1101")
      (value "MOUNT-HOLE3.1MM")
      (footprint "eagle-import:MOUNT-HOLE3.1")
      (libsource (lib "eagle-import") (part "MOUNT-HOLE3.1MM"))
    )
    (comp (ref "M3_MOUNT1102")
      (value "MOUNT-HOLE3.1MM")
      (footprint "eagle-import:MOUNT-HOLE3.1")
      (libsource (lib "eagle-import") (part "MOUNT-HOLE3.1MM"))
    )
    (comp (ref "M3_MOUNT1103")
      (value "MOUNT-HOLE3.1MM")
      (footprint "eagle-import:MOUNT-HOLE3.1")
      (libsource (lib "eagle-import") (part "MOUNT-HOLE3.1MM"))
    )
    (comp (ref "M3_MOUNT1104")
      (value "MOUNT-HOLE3.1MM")
      (footprint "eagle-import:MOUNT-HOLE3.1")
      (libsource (lib "eagle-import") (part "MOUNT-HOLE3.1MM"))
    )
    (comp (ref "OSHW_LOGO")
      (value "OSHW-LOGOS")
      (footprint "eagle-import:OSHW-LOGO-S")
      (libsource (lib "eagle-import") (part "OSHW-LOGOS"))
    )
    (comp (ref "S1RX")
      (value "PAD.04")
      (footprint "eagle-import:PAD.04X.04")
      (libsource (lib "eagle-import") (part "PAD.04"))
    )
    (comp (ref "S1TX")
      (value "PAD.04")
      (footprint "eagle-import:PAD.04X.04")
      (libsource (lib "eagle-import") (part "PAD.04"))
    )
    (comp (ref "S2RX")
      (value "PAD.04")
      (footprint "eagle-import:PAD.04X.04")
      (libsource (lib "eagle-import") (part "PAD.04"))
    )
    (comp (ref "S2TX")
      (value "PAD.04")
      (footprint "eagle-import:PAD.04X.04")
      (libsource (lib "eagle-import") (part "PAD.04"))
    )
    (comp (ref "S3RX")
      (value "PAD.04")
      (footprint "eagle-import:PAD.04X.04")
      (libsource (lib "eagle-import") (part "PAD.04"))
    )
    (comp (ref "S3TX")
      (value "PAD.04")
      (footprint "eagle-import:PAD.04X.04")
      (libsource (lib "eagle-import") (part "PAD.04"))
    )
    (comp (ref "S4RX")
      (value "PAD.04")
      (footprint "eagle-import:PAD.04X.04")
      (libsource (lib "eagle-import") (part "PAD.04"))
    )
    (comp (ref "S4TX")
      (value "PAD.04")
      (footprint "eagle-import:PAD.04X.04")
      (libsource (lib "eagle-import") (part "PAD.04"))
    )
    (comp (ref "S5_RX")
      (value "PAD.04")
      (footprint "eagle-import:PAD.04X.04")
      (libsource (lib "eagle-import") (part "PAD.04"))
    )
    (comp (ref "S5_TX")
      (value "PAD.04")
      (footprint "eagle-import:PAD.04X.04")
      (libsource (lib "eagle-import") (part "PAD.04"))
    )
    (comp (ref "VDDA_3V1101")
      (value "PAD.04")
      (footprint "eagle-import:PAD.04X.04")
      (libsource (lib "eagle-import") (part "PAD.04"))
    )
    (comp (ref "VDD_3V1101")
      (value "PAD.04")
      (footprint "eagle-import:PAD.04X.04")
      (libsource (lib "eagle-import") (part "PAD.04"))
    )
    (comp (ref "VDD_5V_BRICK")
      (value "PAD.04")
      (footprint "eagle-import:PAD.04X.04")
      (libsource (lib "eagle-import") (part "PAD.04"))
    )
    (comp (ref "J601")
      (value "DF13C-6P-1.25V")
      (footprint "eagle-import:DF13C-6P-1.25V")
      (fields (field (name "PARTNO") "DF13C-6P-1.25V(20)"))
      (libsource (lib "eagle-import") (part "DF13-6P-1.25V"))
    )
    (comp (ref "L601")
      (value "KNH16C104DA5TS")
      (footprint "eagle-import:KYOCERA-KNH16-DA")
      (libsource (lib "eagle-import") (part "KNH16C104DA5TS"))
    )
    (comp (ref "L602")
      (value "KNH16C104DA5TS")
      (footprint "eagle-import:KYOCERA-KNH16-DA")
      (libsource (lib "eagle-import") (part "KNH16C104DA5TS"))
    )
    (comp (ref "R1")
      (value "453K")
      (footprint "eagle-import:0402-RES")
      (fields (field (name "PARTNO") "RMCF0402FT453K"))
      (libsource (lib "eagle-import") (part "RESISTOR0402-RES"))
    )
    (comp (ref "R2")
      (value "45.3K")
      (footprint "eagle-import:0402-RES")
      (libsource (lib "eagle-import") (part "RESISTOR0402-RES"))
    )
    (comp (ref "R5")
      (value "105K")
      (footprint "eagle-import:0402-RES")
      (libsource (lib "eagle-import") (part "RESISTOR0402-RES"))
    )
    (comp (ref "R6")
      (value "453K")
      (footprint "eagle-import:0402-RES")
      (fields (field (name "PARTNO") "RMCF0402FT453K"))
      (libsource (lib "eagle-import") (part "RESISTOR0402-RES"))
    )
    (comp (ref "R7")
      (value "45.3K")
      (footprint "eagle-import:0402-RES")
      (libsource (lib "eagle-import") (part "RESISTOR0402-RES"))
    )
    (comp (ref "R8")
      (value "105K")
      (footprint "eagle-import:0402-RES")
      (libsource (lib "eagle-import") (part "RESISTOR0402-RES"))
    )
    (comp (ref "R9")
      (value "453K")
      (footprint "eagle-import:0402-RES")
      (fields (field (name "PARTNO") "RMCF0402FT453K"))
      (libsource (lib "eagle-import") (part "RESISTOR0402-RES"))
    )
    (comp (ref "R10")
      (value "45.3K")
      (footprint "eagle-import:0402-RES")
      (libsource (lib "eagle-import") (part "RESISTOR0402-RES"))
    )
    (comp (ref "R11")
      (value "105K")
      (footprint "eagle-import:0402-RES")
      (libsource (lib "eagle-import") (part "RESISTOR0402-RES"))
    )
    (comp (ref "R604")
      (value "10K/0.1%")
      (footprint "eagle-import:0402-RES")
      (fields (field (name "PARTNO") "ERA-2AEB103X"))
      (libsource (lib "eagle-import") (part "RESISTOR0402-RES"))
    )
    (comp (ref "R605")
      (value "10K/0.1%")
      (footprint "eagle-import:0402-RES")
      (fields (field (name "PARTNO") "ERA-2AEB103X"))
      (libsource (lib "eagle-import") (part "RESISTOR0402-RES"))
    )
    (comp (ref "U$2")
      (value "LTC4417")
      (footprint "eagle-import:MO-220")
      (libsource (lib "eagle-import") (part "LTC4117"))
    )
    (comp (ref "U$3")
      (value "MOSFET-DUAL-PCHANNEL-CHIPFET")
      (footprint "eagle-import:1206-8")
      (fields (field (name "PARTNO") "*"))
      (libsource (lib "eagle-import") (part "MOSFET-DUAL-PCHANNEL-CHIPFET"))
    )
    (comp (ref "U$4")
      (value "MOSFET-DUAL-PCHANNEL-CHIPFET")
      (footprint "eagle-import:1206-8")
      (fields (field (name "PARTNO") "*"))
      (libsource (lib "eagle-import") (part "MOSFET-DUAL-PCHANNEL-CHIPFET"))
    )
    (comp (ref "U$5")
      (value "MOSFET-DUAL-PCHANNEL-CHIPFET")
      (footprint "eagle-import:1206-8")
      (fields (field (name "PARTNO") "*"))
      (libsource (lib "eagle-import") (part "MOSFET-DUAL-PCHANNEL-CHIPFET"))
    )
    (comp (ref "J301")
      (value "47346-0001")
      (footprint "eagle-import:MOLEX-47346-0001")
      (libsource (lib "eagle-import") (part "MOLEX-47346-0001"))
    )
    (comp (ref "J302")
      (value "DF13C-4P-1.25V")
      (footprint "eagle-import:DF13C-4P-1.25V")
      (fields (field (name "PARTNO") "DF13C-4P-1.25V(20)"))
      (libsource (lib "eagle-import") (part "DF13-4P-1.25V"))
    )
    (comp (ref "JX301")
      (value "ARM_MINI_JTAG-SMT")
      (footprint "eagle-import:FTSH-105-01-XXX-DV-K")
      (fields (field (name "BOM") "EXCLUDE") (field (name "PARTNO") "M50-3900542"))
      (libsource (lib "eagle-import") (part "ARM_MINI_JTAG-SMT"))
    )
    (comp (ref "R301")
      (value "100K")
      (footprint "eagle-import:0402-RES")
      (fields (field (name "PARTNO") "RC0402FR-07100KL"))
      (libsource (lib "eagle-import") (part "RESISTOR0402-RES"))
    )
    (comp (ref "R302")
      (value "100K")
      (footprint "eagle-import:0402-RES")
      (fields (field (name "PARTNO") "RC0402FR-07100KL"))
      (libsource (lib "eagle-import") (part "RESISTOR0402-RES"))
    )
    (comp (ref "R303")
      (value "100K")
      (footprint "eagle-import:0402-RES")
      (fields (field (name "PARTNO") "RC0402FR-07100KL"))
      (libsource (lib "eagle-import") (part "RESISTOR0402-RES"))
    )
    (comp (ref "R304")
      (value "100K")
      (footprint "eagle-import:0402-RES")
      (fields (field (name "PARTNO") "RC0402FR-07100KL"))
      (libsource (lib "eagle-import") (part "RESISTOR0402-RES"))
    )
    (comp (ref "R305")
      (value "100K")
      (footprint "eagle-import:0402-RES")
      (fields (field (name "PARTNO") "RC0402FR-07100KL"))
      (libsource (lib "eagle-import") (part "RESISTOR0402-RES"))
    )
    (comp (ref "R306")
      (value "1K5")
      (footprint "eagle-import:0402-RES")
      (fields (field (name "PARTNO") "RC0402FR-071K5L"))
      (libsource (lib "eagle-import") (part "RESISTOR0402-RES"))
    )
    (comp (ref "R307")
      (value "1K5")
      (footprint "eagle-import:0402-RES")
      (fields (field (name "PARTNO") "RC0402FR-071K5L"))
      (libsource (lib "eagle-import") (part "RESISTOR0402-RES"))
    )
    (comp (ref "U$301")
      (value "NUF2042XV6")
      (footprint "eagle-import:SOT563-6")
      (fields (field (name "PARTNO") "NUF2042XV6T1G"))
      (libsource (lib "eagle-import") (part "NUF2042XV6"))
    )
    (comp (ref "U301")
      (value "2908-05WB-MG")
      (footprint "eagle-import:MICROSD")
      (libsource (lib "eagle-import") (part "MICROSDSDI"))
    )
    (comp (ref "C701")
      (value "0u1")
      (footprint "eagle-import:0402-CAP")
      (fields (field (name "PARTNO") "CC0402ZRY5V7BB104"))
      (libsource (lib "eagle-import") (part "CAP0402"))
    )
    (comp (ref "C702")
      (value "1u0")
      (footprint "eagle-import:0603-CAP")
      (fields (field (name "PARTNO") "CC0603ZRY5V7BB105"))
      (libsource (lib "eagle-import") (part "CAP0603"))
    )
    (comp (ref "C703")
      (value "5n6")
      (footprint "eagle-import:0402-CAP")
      (fields (field (name "PARTNO") "CC0402KRX7R7BB562"))
      (libsource (lib "eagle-import") (part "CAP0402"))
    )
    (comp (ref "C704")
      (value "0u47")
      (footprint "eagle-import:0402-CAP")
      (fields (field (name "PARTNO") "C1005X5R1C474K050BC"))
      (libsource (lib "eagle-import") (part "CAP0402"))
    )
    (comp (ref "J701")
      (value "DF13C-2P-1.25V")
      (footprint "eagle-import:DF13C-2P-1.25V")
      (fields (field (name "PARTNO") "DF13C-2P-1.25V(20)"))
      (libsource (lib "eagle-import") (part "DF13-2P-1.25V"))
    )
    (comp (ref "J702")
      (value "DF13C-3P-1.25V")
      (footprint "eagle-import:DF13C-3P-1.25V")
      (fields (field (name "PARTNO") "DF13C-3P-1.25V(20)"))
      (libsource (lib "eagle-import") (part "DF13-3P-1.25V"))
    )
    (comp (ref "L701")
      (value "47uH")
      (footprint "eagle-import:0805-IND")
      (fields (field (name "PARTNO") "MLZ2012M470W"))
      (libsource (lib "eagle-import") (part "INDUCTOR0805"))
    )
    (comp (ref "LED701")
      (value "AMBER")
      (footprint "eagle-import:0603-LED")
      (fields (field (name "PARTNO") "APTD1608SECK"))
      (libsource (lib "eagle-import") (part "LED0603"))
    )
    (comp (ref "LED702")
      (value "GREEN")
      (footprint "eagle-import:0603-LED")
      (fields (field (name "PARTNO") "APTD1608CGCK"))
      (libsource (lib "eagle-import") (part "LED0603"))
    )
    (comp (ref "LED703")
      (value "AMBER")
      (footprint "eagle-import:0603-LED")
      (fields (field (name "PARTNO") "APTD1608SECK"))
      (libsource (lib "eagle-import") (part "LED0603"))
    )
    (comp (ref "LED704")
      (value "GREEN")
      (footprint "eagle-import:0603-LED")
      (fields (field (name "PARTNO") "APTD1608CGCK"))
      (libsource (lib "eagle-import") (part "LED0603"))
    )
    (comp (ref "LED705")
      (value "BLUE")
      (footprint "eagle-import:0603-LED")
      (fields (field (name "PARTNO") "APTD1608QBC/D"))
      (libsource (lib "eagle-import") (part "LED0603"))
    )
    (comp (ref "R3")
      (value "220R")
      (footprint "eagle-import:0402-RES")
      (fields (field (name "PARTNO") "RC0402FR-07220RL"))
      (libsource (lib "eagle-import") (part "RESISTOR0402-RES"))
    )
    (comp (ref "R4")
      (value "220R")
      (footprint "eagle-import:0402-RES")
      (fields (field (name "PARTNO") "RC0402FR-07220RL"))
      (libsource (lib "eagle-import") (part "RESISTOR0402-RES"))
    )
    (comp (ref "R701")
      (value "9K09")
      (footprint "eagle-import:0402-RES")
      (fields (field (name "PARTNO") "RMCF0402FT9K09"))
      (libsource (lib "eagle-import") (part "RESISTOR0402-RES"))
    )
    (comp (ref "R702")
      (value "10K")
      (footprint "eagle-import:0402-RES")
      (fields (field (name "PARTNO") "RC0402FR-0710KL"))
      (libsource (lib "eagle-import") (part "RESISTOR0402-RES"))
    )
    (comp (ref "R703")
      (value "100K")
      (footprint "eagle-import:0402-RES")
      (fields (field (name "PARTNO") "RC0402FR-07100KL"))
      (libsource (lib "eagle-import") (part "RESISTOR0402-RES"))
    )
    (comp (ref "R704")
      (value "10K")
      (footprint "eagle-import:0402-RES")
      (fields (field (name "PARTNO") "RC0402FR-0710KL"))
      (libsource (lib "eagle-import") (part "RESISTOR0402-RES"))
    )
    (comp (ref "R705")
      (value "453K")
      (footprint "eagle-import:0402-RES")
      (fields (field (name "PARTNO") "RMCF0402FT453K"))
      (libsource (lib "eagle-import") (part "RESISTOR0402-RES"))
    )
    (comp (ref "R706")
      (value "16K5")
      (footprint "eagle-import:0402-RES")
      (fields (field (name "PARTNO") "RMCF0402FT16K5"))
      (libsource (lib "eagle-import") (part "RESISTOR0402-RES"))
    )
    (comp (ref "R707")
      (value "220R")
      (footprint "eagle-import:0402-RES")
      (fields (field (name "PARTNO") "RC0402FR-07220RL"))
      (libsource (lib "eagle-import") (part "RESISTOR0402-RES"))
    )
    (comp (ref "R708")
      (value "220R")
      (footprint "eagle-import:0402-RES")
      (fields (field (name "PARTNO") "RC0402FR-07220RL"))
      (libsource (lib "eagle-import") (part "RESISTOR0402-RES"))
    )
    (comp (ref "R709")
      (value "220R")
      (footprint "eagle-import:0402-RES")
      (fields (field (name "PARTNO") "RC0402FR-07220RL"))
      (libsource (lib "eagle-import") (part "RESISTOR0402-RES"))
    )
    (comp (ref "R710")
      (value "47R")
      (footprint "eagle-import:0402-RES")
      (fields (field (name "PARTNO") "RC0402JR-0747RL"))
      (libsource (lib "eagle-import") (part "RESISTOR0402-RES"))
    )
    (comp (ref "R711")
      (value "220R")
      (footprint "eagle-import:0402-RES")
      (fields (field (name "PARTNO") "RC0402FR-07220RL"))
      (libsource (lib "eagle-import") (part "RESISTOR0402-RES"))
    )
    (comp (ref "R712")
      (value "220R")
      (footprint "eagle-import:0402-RES")
      (fields (field (name "PARTNO") "RC0402FR-07220RL"))
      (libsource (lib "eagle-import") (part "RESISTOR0402-RES"))
    )
    (comp (ref "R713")
      (value "1K5")
      (footprint "eagle-import:0402-RES")
      (fields (field (name "PARTNO") "RC0402FR-071K5L"))
      (libsource (lib "eagle-import") (part "RESISTOR0402-RES"))
    )
    (comp (ref "U$701")
      (value "PESD0402-140")
      (footprint "eagle-import:0402-TVS")
      (libsource (lib "eagle-import") (part "DIODE-TVS"))
    )
    (comp (ref "U701")
      (value "TCA62724FMG")
      (footprint "eagle-import:SON10")
      (libsource (lib "eagle-import") (part "TCA62724FMG"))
    )
    (comp (ref "U702")
      (value "LT3469")
      (footprint "eagle-import:SOT23-8")
      (fields (field (name "PARTNO") "LT3469ETS8"))
      (libsource (lib "eagle-import") (part "LT3469"))
    )
    (comp (ref "U703")
      (value "LRTB GFTG-T7AW-1+V7A7-29+R5T9-49-L")
      (footprint "eagle-import:6-PLCC")
      (fields (field (name "PARTNO") "LRTB GFTG-T7AW-1+V7A7-29+R5T9-49-L"))
      (libsource (lib "eagle-import") (part "RGB-LED6-PLCC"))
    )
    (comp (ref "B601")
      (value "MS621FE")
      (footprint "eagle-import:MS621FE")
      (fields (field (name "PARTNO") "MS621FE-FL11E"))
      (libsource (lib "eagle-import") (part "MS621FE"))
    )
    (comp (ref "C601")
      (value "2u2")
      (footprint "eagle-import:0603-CAP")
      (fields (field (name "PARTNO") "C1608Y5V1C225Z"))
      (libsource (lib "eagle-import") (part "CAP0603"))
    )
    (comp (ref "C602")
      (value "10n")
      (footprint "eagle-import:0402-CAP")
      (fields (field (name "PARTNO") "CC0402KRX7R7BB103"))
      (libsource (lib "eagle-import") (part "CAP0402"))
    )
    (comp (ref "C603")
      (value "1u0")
      (footprint "eagle-import:0603-CAP")
      (fields (field (name "PARTNO") "CC0603ZRY5V7BB105"))
      (libsource (lib "eagle-import") (part "CAP0603"))
    )
    (comp (ref "C604")
      (value "10u/10V")
      (footprint "eagle-import:0805-CAP")
      (fields (field (name "PARTNO") "CC0805ZKY5V6BB106"))
      (libsource (lib "eagle-import") (part "CAP0805"))
    )
    (comp (ref "C605")
      (value "1u0")
      (footprint "eagle-import:0603-CAP")
      (fields (field (name "PARTNO") "CC0603ZRY5V7BB105"))
      (libsource (lib "eagle-import") (part "CAP0603"))
    )
    (comp (ref "C606")
      (value "0u1")
      (footprint "eagle-import:0402-CAP")
      (fields (field (name "PARTNO") "CC0402ZRY5V7BB104"))
      (libsource (lib "eagle-import") (part "CAP0402"))
    )
    (comp (ref "C607")
      (value "0u1")
      (footprint "eagle-import:0402-CAP")
      (fields (field (name "PARTNO") "CC0402ZRY5V7BB104"))
      (libsource (lib "eagle-import") (part "CAP0402"))
    )
    (comp (ref "C608")
      (value "0u1")
      (footprint "eagle-import:0402-CAP")
      (fields (field (name "PARTNO") "CC0402ZRY5V7BB104"))
      (libsource (lib "eagle-import") (part "CAP0402"))
    )
    (comp (ref "C609")
      (value "0u1")
      (footprint "eagle-import:0402-CAP")
      (fields (field (name "PARTNO") "CC0402ZRY5V7BB104"))
      (libsource (lib "eagle-import") (part "CAP0402"))
    )
    (comp (ref "C610")
      (value "0u1")
      (footprint "eagle-import:0402-CAP")
      (fields (field (name "PARTNO") "CC0402ZRY5V7BB104"))
      (libsource (lib "eagle-import") (part "CAP0402"))
    )
    (comp (ref "C611")
      (value "2u2")
      (footprint "eagle-import:0603-CAP")
      (fields (field (name "PARTNO") "C1608Y5V1C225Z"))
      (libsource (lib "eagle-import") (part "CAP0603"))
    )
    (comp (ref "C612")
      (value "0u1")
      (footprint "eagle-import:0402-CAP")
      (fields (field (name "PARTNO") "CC0402ZRY5V7BB104"))
      (libsource (lib "eagle-import") (part "CAP0402"))
    )
    (comp (ref "C613")
      (value "2u2")
      (footprint "eagle-import:0603-CAP")
      (fields (field (name "PARTNO") "C1608Y5V1C225Z"))
      (libsource (lib "eagle-import") (part "CAP0603"))
    )
    (comp (ref "L603")
      (value "KNH16C104DA5TS")
      (footprint "eagle-import:KYOCERA-KNH16-DA")
      (libsource (lib "eagle-import") (part "KNH16C104DA5TS"))
    )
    (comp (ref "R602")
      (value "16K5")
      (footprint "eagle-import:0402-RES")
      (fields (field (name "PARTNO") "RMCF0402FT16K5"))
      (libsource (lib "eagle-import") (part "RESISTOR0402-RES"))
    )
    (comp (ref "R603")
      (value "10K")
      (footprint "eagle-import:0402-RES")
      (fields (field (name "PARTNO") "RC0402FR-0710KL"))
      (libsource (lib "eagle-import") (part "RESISTOR0402-RES"))
    )
    (comp (ref "R606")
      (value "25K")
      (footprint "eagle-import:0402-RES")
      (fields (field (name "PARTNO") "RMCF0402FT25K5"))
      (libsource (lib "eagle-import") (part "RESISTOR0402-RES"))
    )
    (comp (ref "R607")
      (value "10K")
      (footprint "eagle-import:0402-RES")
      (fields (field (name "PARTNO") "RC0402FR-0710KL"))
      (libsource (lib "eagle-import") (part "RESISTOR0402-RES"))
    )
    (comp (ref "R608")
      (value "1K")
      (footprint "eagle-import:0402-RES")
      (fields (field (name "PARTNO") "RC0402FR-071KL"))
      (libsource (lib "eagle-import") (part "RESISTOR0402-RES"))
    )
    (comp (ref "R609")
      (value "10K/0.1%")
      (footprint "eagle-import:0402-RES")
      (fields (field (name "PARTNO") "ERA-2AEB103X"))
      (libsource (lib "eagle-import") (part "RESISTOR0402-RES"))
    )
    (comp (ref "R610")
      (value "10K/0.1%")
      (footprint "eagle-import:0402-RES")
      (fields (field (name "PARTNO") "ERA-2AEB103X"))
      (libsource (lib "eagle-import") (part "RESISTOR0402-RES"))
    )
    (comp (ref "R611")
      (value "10K")
      (footprint "eagle-import:0402-RES")
      (fields (field (name "PARTNO") "RC0402FR-0710KL"))
      (libsource (lib "eagle-import") (part "RESISTOR0402-RES"))
    )
    (comp (ref "S601")
      (value "RESET")
      (footprint "eagle-import:EVQP7J01K")
      (fields (field (name "PARTNO") "EVQP7J01K"))
      (libsource (lib "eagle-import") (part "SWITCH-MOMENTARY-2"))
    )
    (comp (ref "U$602")
      (value "BQ24315")
      (footprint "eagle-import:QFN8-DSG")
      (fields (field (name "PARTNO") "BQ24315DSGR"))
      (libsource (lib "eagle-import") (part "BQ24315"))
    )
    (comp (ref "U$604")
      (value "BQ24315")
      (footprint "eagle-import:QFN8-DSG")
      (fields (field (name "PARTNO") "BQ24315DSGR"))
      (libsource (lib "eagle-import") (part "BQ24315"))
    )
    (comp (ref "U$605")
      (value "MIC5332")
      (footprint "eagle-import:MLF-8-EPAD")
      (fields (field (name "PARTNO") "MIC5332-SSYMT"))
      (libsource (lib "eagle-import") (part "MIC5332"))
    )
    (comp (ref "U101")
      (value "STM32F4X7VX")
      (footprint "eagle-import:TQFP100")
      (fields (field (name "PARTNO") "STM32F427VI"))
      (libsource (lib "eagle-import") (part "STM32F4X7VX"))
    )
    (comp (ref "C1001")
      (value "1u0")
      (footprint "eagle-import:0603-CAP")
      (fields (field (name "PARTNO") "CC0603ZRY5V7BB105"))
      (libsource (lib "eagle-import") (part "CAP0603"))
    )
    (comp (ref "C1002")
      (value "10n")
      (footprint "eagle-import:0402-CAP")
      (fields (field (name "PARTNO") "CC0402KRX7R7BB103"))
      (libsource (lib "eagle-import") (part "CAP0402"))
    )
    (comp (ref "C1003")
      (value "1u0")
      (footprint "eagle-import:0603-CAP")
      (fields (field (name "PARTNO") "CC0603ZRY5V7BB105"))
      (libsource (lib "eagle-import") (part "CAP0603"))
    )
    (comp (ref "C1004")
      (value "1u0")
      (footprint "eagle-import:0603-CAP")
      (fields (field (name "PARTNO") "CC0603ZRY5V7BB105"))
      (libsource (lib "eagle-import") (part "CAP0603"))
    )
    (comp (ref "D1001")
      (value "PMEG2005CT")
      (footprint "eagle-import:SOT23-3")
      (libsource (lib "eagle-import") (part "PMEG2005CT"))
    )
    (comp (ref "F2")
      (value "0ZCA0035FF2G")
      (footprint "eagle-import:PTC-1206")
      (libsource (lib "eagle-import") (part "PTCSMD"))
    )
    (comp (ref "R1001")
      (value "100K")
      (footprint "eagle-import:0402-RES")
      (fields (field (name "PARTNO") "RC0402FR-07100KL"))
      (libsource (lib "eagle-import") (part "RESISTOR0402-RES"))
    )
    (comp (ref "R1002")
      (value "10K")
      (footprint "eagle-import:0402-RES")
      (fields (field (name "PARTNO") "RC0402FR-0710KL"))
      (libsource (lib "eagle-import") (part "RESISTOR0402-RES"))
    )
    (comp (ref "U$1001")
      (value "BQ24313")
      (footprint "eagle-import:QFN8-DSG")
      (fields (field (name "PARTNO") "BQ24313DSGT"))
      (libsource (lib "eagle-import") (part "BQ24313"))
    )
    (comp (ref "U$1002")
      (value "MIC5332")
      (footprint "eagle-import:MLF-8-EPAD")
      (fields (field (name "PARTNO") "MIC5332-SSYMT"))
      (libsource (lib "eagle-import") (part "MIC5332"))
    )
    (comp (ref "C501")
      (value "10u/10V")
      (footprint "eagle-import:0805-CAP")
      (fields (field (name "PARTNO") "CC0805ZKY5V6BB106"))
      (libsource (lib "eagle-import") (part "CAP0805"))
    )
    (comp (ref "C502")
      (value "0u1")
      (footprint "eagle-import:0402-CAP")
      (fields (field (name "PARTNO") "CC0402ZRY5V7BB104"))
      (libsource (lib "eagle-import") (part "CAP0402"))
    )
    (comp (ref "C503")
      (value "0u1")
      (footprint "eagle-import:0402-CAP")
      (fields (field (name "PARTNO") "CC0402ZRY5V7BB104"))
      (libsource (lib "eagle-import") (part "CAP0402"))
    )
    (comp (ref "C504")
      (value "10n")
      (footprint "eagle-import:0402-CAP")
      (fields (field (name "PARTNO") "CC0402KRX7R7BB103"))
      (libsource (lib "eagle-import") (part "CAP0402"))
    )
    (comp (ref "C505")
      (value "10n")
      (footprint "eagle-import:0402-CAP")
      (fields (field (name "PARTNO") "CC0402KRX7R7BB103"))
      (libsource (lib "eagle-import") (part "CAP0402"))
    )
    (comp (ref "C506")
      (value "10u/10V")
      (footprint "eagle-import:0805-CAP")
      (fields (field (name "PARTNO") "CC0805ZKY5V6BB106"))
      (libsource (lib "eagle-import") (part "CAP0805"))
    )
    (comp (ref "C507")
      (value "0u1")
      (footprint "eagle-import:0402-CAP")
      (fields (field (name "PARTNO") "CC0402ZRY5V7BB104"))
      (libsource (lib "eagle-import") (part "CAP0402"))
    )
    (comp (ref "C508")
      (value "0u1")
      (footprint "eagle-import:0402-CAP")
      (fields (field (name "PARTNO") "CC0402ZRY5V7BB104"))
      (libsource (lib "eagle-import") (part "CAP0402"))
    )
    (comp (ref "C509")
      (value "10u/10V")
      (footprint "eagle-import:0805-CAP")
      (fields (field (name "PARTNO") "CC0805ZKY5V6BB106"))
      (libsource (lib "eagle-import") (part "CAP0805"))
    )
    (comp (ref "C510")
      (value "0u47")
      (footprint "eagle-import:0402-CAP")
      (fields (field (name "PARTNO") "C1005X5R1C474K050BC"))
      (libsource (lib "eagle-import") (part "CAP0402"))
    )
    (comp (ref "U$1")
      (value "0512811094")
      (footprint "eagle-import:51281-1094")
      (fields (field (name "PARTNO") "0781191109"))
      (libsource (lib "eagle-import") (part "CONN_FPC_10RA"))
    )
    (comp (ref "U$501")
      (value "LSM303D")
      (footprint "eagle-import:LGA-16L")
      (libsource (lib "eagle-import") (part "LSM303D"))
    )
    (comp (ref "U501")
      (value "L3GD20")
      (footprint "eagle-import:L3G4200DH-MAN")
      (libsource (lib "eagle-import") (part "L3G4200DH-LL"))
    )
    (comp (ref "U502")
      (value "L3GD20H")
      (footprint "eagle-import:LGA-16L")
      (libsource (lib "eagle-import") (part "L3GD20H"))
    )
    (comp (ref "U503")
      (value "MS5611-01BA")
      (footprint "eagle-import:MS5611-01BA")
      (libsource (lib "eagle-import") (part "MS5611-01BA"))
    )
    (comp (ref "C101")
      (value "0u1")
      (footprint "eagle-import:0402-CAP")
      (fields (field (name "PARTNO") "CC0402ZRY5V7BB104"))
      (libsource (lib "eagle-import") (part "CAP0402"))
    )
    (comp (ref "C102")
      (value "8p")
      (footprint "eagle-import:0402-CAP")
      (fields (field (name "PARTNO") "C1005C0G1H080C"))
      (libsource (lib "eagle-import") (part "CAP0402"))
    )
    (comp (ref "C103")
      (value "8p")
      (footprint "eagle-import:0402-CAP")
      (fields (field (name "PARTNO") "C1005C0G1H080C"))
      (libsource (lib "eagle-import") (part "CAP0402"))
    )
    (comp (ref "R101")
      (value "470R")
      (footprint "eagle-import:0402-RES")
      (fields (field (name "PARTNO") "RC0402FR-07470RL"))
      (libsource (lib "eagle-import") (part "RESISTOR0402-RES"))
    )
    (comp (ref "R102")
      (value "10K")
      (footprint "eagle-import:0402-RES")
      (fields (field (name "PARTNO") "RC0402FR-0710KL"))
      (libsource (lib "eagle-import") (part "RESISTOR0402-RES"))
    )
    (comp (ref "U102")
      (value "FM25V01")
      (footprint "eagle-import:SO08")
      (fields (field (name "PARTNO") "FM25V01-G"))
      (libsource (lib "eagle-import") (part "FM25V01"))
    )
    (comp (ref "X101")
      (value "3.2x2.5 mm / 24 MHz / 15 ppm")
      (footprint "eagle-import:OSCILLATOR-3.2X2.5")
      (fields (field (name "PARTNO") "NX3225SA-24.000000MHZ"))
      (libsource (lib "eagle-import") (part "OSCILLATOR-3.2X2.5"))
    )
    (comp (ref "C801")
      (value "0u1")
      (footprint "eagle-import:0402-CAP")
      (fields (field (name "PARTNO") "CC0402ZRY5V7BB104"))
      (libsource (lib "eagle-import") (part "CAP0402"))
    )
    (comp (ref "C802")
      (value "0u1")
      (footprint "eagle-import:0402-CAP")
      (fields (field (name "PARTNO") "CC0402ZRY5V7BB104"))
      (libsource (lib "eagle-import") (part "CAP0402"))
    )
    (comp (ref "C803")
      (value "0u1")
      (footprint "eagle-import:0402-CAP")
      (fields (field (name "PARTNO") "CC0402ZRY5V7BB104"))
      (libsource (lib "eagle-import") (part "CAP0402"))
    )
    (comp (ref "C804")
      (value "0u1")
      (footprint "eagle-import:0402-CAP")
      (fields (field (name "PARTNO") "CC0402ZRY5V7BB104"))
      (libsource (lib "eagle-import") (part "CAP0402"))
    )
    (comp (ref "C805")
      (value "8p")
      (footprint "eagle-import:0402-CAP")
      (fields (field (name "PARTNO") "C1005C0G1H080C"))
      (libsource (lib "eagle-import") (part "CAP0402"))
    )
    (comp (ref "C806")
      (value "8p")
      (footprint "eagle-import:0402-CAP")
      (fields (field (name "PARTNO") "C1005C0G1H080C"))
      (libsource (lib "eagle-import") (part "CAP0402"))
    )
    (comp (ref "J801")
      (value "JST-ZH-3")
      (footprint "eagle-import:JST-ZH-SMT-VERTICAL")
      (fields (field (name "PARTNO") "B3B-ZR-SM4-TF (LF)(SN)(P)"))
      (libsource (lib "eagle-import") (part "JST-ZH-3"))
    )
    (comp (ref "JX801")
      (value "HEADER-3X1BOARDEDGE-SHORT")
      (footprint "eagle-import:HEADER_3X01_SMD_H_BOARD_EDGE_SHORT")
      (libsource (lib "eagle-import") (part "HEADER-3X1BOARDEDGE-SHORT"))
    )
    (comp (ref "JX802")
      (value "ARM_MINI_JTAG-SMT")
      (footprint "eagle-import:FTSH-105-01-XXX-DV-K")
      (fields (field (name "BOM") "EXCLUDE") (field (name "PARTNO") "M50-3900542"))
      (libsource (lib "eagle-import") (part "ARM_MINI_JTAG-SMT"))
    )
    (comp (ref "R801")
      (value "10K")
      (footprint "eagle-import:0402-RES")
      (fields (field (name "PARTNO") "RC0402FR-0710KL"))
      (libsource (lib "eagle-import") (part "RESISTOR0402-RES"))
    )
    (comp (ref "R802")
      (value "10K")
      (footprint "eagle-import:0402-RES")
      (fields (field (name "PARTNO") "RC0402FR-0710KL"))
      (libsource (lib "eagle-import") (part "RESISTOR0402-RES"))
    )
    (comp (ref "R803")
      (value "220R")
      (footprint "eagle-import:0402-RES")
      (fields (field (name "PARTNO") "RC0402FR-07220RL"))
      (libsource (lib "eagle-import") (part "RESISTOR0402-RES"))
    )
    (comp (ref "R804")
      (value "220R")
      (footprint "eagle-import:0402-RES")
      (fields (field (name "PARTNO") "RC0402FR-07220RL"))
      (libsource (lib "eagle-import") (part "RESISTOR0402-RES"))
    )
    (comp (ref "S801")
      (value "RESET")
      (footprint "eagle-import:EVQP7J01K")
      (fields (field (name "PARTNO") "EVQP7J01K"))
      (libsource (lib "eagle-import") (part "SWITCH-MOMENTARY-2"))
    )
    (comp (ref "U$801")
      (value "PESD0402-140")
      (footprint "eagle-import:0402-TVS")
      (libsource (lib "eagle-import") (part "DIODE-TVS"))
    )
    (comp (ref "U801")
      (value "STM32F10XCXT6")
      (footprint "eagle-import:TQFP48")
      (fields (field (name "PARTNO") "STM32F100C8T6B"))
      (libsource (lib "eagle-import") (part "STM32F10XCXT6"))
    )
    (comp (ref "X801")
      (value "3.2x2.5 mm / 24 MHz / 15 ppm")
      (footprint "eagle-import:OSCILLATOR-3.2X2.5")
      (fields (field (name "PARTNO") "NX3225SA-24.000000MHZ"))
      (libsource (lib "eagle-import") (part "OSCILLATOR-3.2X2.5"))
    )
  )
  (nets
    (net (code "1") (name "ACCEL_DRDY") (class "Default")
      (node (ref "U$1") (pin "3") (pinfunction "S_3") (pintype "passive"))
      (node (ref "U$501") (pin "11") (pinfunction "INT1_11") (pintype "bidirectional"))
      (node (ref "U101") (pin "90") (pinfunction "PB4_90") (pintype "bidirectional"))
    )
    (net (code "2") (name "ALARM") (class "Default")
      (node (ref "R701") (pin "P$2") (pinfunction "2_P$2") (pintype "passive"))
      (node (ref "U101") (pin "77") (pinfunction "PA15_77") (pintype "bidirectional"))
    )
    (net (code "3") (name "BATT_CURRENT_SENS") (class "Default")
      (node (ref "R604") (pin "P$1") (pinfunction "1_P$1") (pintype "passive"))
      (node (ref "U101") (pin "26") (pinfunction "PA3_26") (pintype "bidirectional"))
    )
    (net (code "4") (name "BATT_VOLTAGE_SENS") (class "Default")
      (node (ref "R605") (pin "P$1") (pinfunction "1_P$1") (pintype "passive"))
      (node (ref "U101") (pin "25") (pinfunction "PA2_25") (pintype "bidirectional"))
    )
    (net (code "5") (name "CAN1_RX") (class "Default")
      (node (ref "U101") (pin "81") (pinfunction "PD0_81") (pintype "bidirectional"))
      (node (ref "U401") (pin "4") (pinfunction "DOUT_4") (pintype "output"))
    )
    (net (code "6") (name "CAN1_TX") (class "Default")
      (node (ref "U101") (pin "82") (pinfunction "PD1_82") (pintype "bidirectional"))
      (node (ref "U401") (pin "1") (pinfunction "DIN_1") (pintype "input"))
    )
    (net (code "7") (name "CAN2_RX") (class "Default")
      (node (ref "R13") (pin "P$1") (pinfunction "1_P$1") (pintype "passive"))
      (node (ref "U101") (pin "51") (pinfunction "PB12_51") (pintype "bidirectional"))
    )
    (net (code "8") (name "CAN2_TX") (class "Default")
      (node (ref "R12") (pin "P$1") (pinfunction "1_P$1") (pintype "passive"))
      (node (ref "U101") (pin "92") (pinfunction "PB6_92") (pintype "bidirectional"))
    )
    (net (code "9") (name "CAN_H") (class "Default")
      (node (ref "CAN_H") (pin "P$1") (pinfunction "P$1_P$1") (pintype "passive"))
      (node (ref "J405") (pin "P$2") (pinfunction "2_P$2") (pintype "passive"))
      (node (ref "R409") (pin "P$1") (pinfunction "1_P$1") (pintype "passive"))
      (node (ref "U401") (pin "7") (pinfunction "CANH_7") (pintype "bidirectional"))
    )
    (net (code "10") (name "CAN_L") (class "Default")
      (node (ref "CAN_L") (pin "P$1") (pinfunction "P$1_P$1") (pintype "passive"))
      (node (ref "J405") (pin "P$3") (pinfunction "3_P$3") (pintype "passive"))
      (node (ref "R409") (pin "P$2") (pinfunction "2_P$2") (pintype "passive"))
      (node (ref "U401") (pin "6") (pinfunction "CANL_6") (pintype "bidirectional"))
    )
    (net (code "11") (name "FMU-BOOT0") (class "Default")
      (node (ref "FMU-BOOT1101") (pin "P$1") (pinfunction "P$1_P$1") (pintype "passive"))
      (node (ref "R611") (pin "P$2") (pinfunction "2_P$2") (pintype "passive"))
      (node (ref "U101") (pin "94") (pinfunction "BOOT0_94") (pintype "input"))
    )
    (net (code "12") (name "FMU-CH1") (class "Default")
      (node (ref "U101") (pin "45") (pinfunction "PE14_45") (pintype "bidirectional"))
      (node (ref "U901") (pin "7") (pinfunction "A6_7") (pintype "bidirectional"))
    )
    (net (code "13") (name "FMU-CH2") (class "Default")
      (node (ref "U101") (pin "44") (pinfunction "PE13_44") (pintype "bidirectional"))
      (node (ref "U901") (pin "6") (pinfunction "A5_6") (pintype "bidirectional"))
    )
    (net (code "14") (name "FMU-CH3") (class "Default")
      (node (ref "U101") (pin "42") (pinfunction "PE11_42") (pintype "bidirectional"))
      (node (ref "U901") (pin "5") (pinfunction "A4_5") (pintype "bidirectional"))
    )
    (net (code "15") (name "FMU-CH4") (class "Default")
      (node (ref "U101") (pin "40") (pinfunction "PE9_40") (pintype "bidirectional"))
      (node (ref "U901") (pin "4") (pinfunction "A3_4") (pintype "bidirectional"))
    )
    (net (code "16") (name "FMU-CH5") (class "Default")
      (node (ref "U101") (pin "60") (pinfunction "PD13_60") (pintype "bidirectional"))
      (node (ref "U901") (pin "3") (pinfunction "A2_3") (pintype "bidirectional"))
    )
    (net (code "17") (name "FMU-CH6") (class "Default")
      (node (ref "U101") (pin "61") (pinfunction "PD14_61") (pintype "bidirectional"))
      (node (ref "U901") (pin "1") (pinfunction "A1_1") (pintype "bidirectional"))
    )
    (net (code "18") (name "FMU-I2C1_SCL") (class "Default")
      (node (ref "R401") (pin "P$1") (pinfunction "1_P$1") (pintype "passive"))
      (node (ref "R404") (pin "P$1") (pinfunction "1_P$1") (pintype "passive"))
      (node (ref "U101") (pin "95") (pinfunction "PB8_95") (pintype "bidirectional"))
    )
    (net (code "19") (name "FMU-I2C1_SDA") (class "Default")
      (node (ref "R402") (pin "P$1") (pinfunction "1_P$1") (pintype "passive"))
      (node (ref "R405") (pin "P$1") (pinfunction "1_P$1") (pintype "passive"))
      (node (ref "U101") (pin "96") (pinfunction "PB9_96") (pintype "bidirectional"))
    )
    (net (code "20") (name "FMU-I2C2_SCL") (class "Default")
      (node (ref "R306") (pin "P$1") (pinfunction "1_P$1") (pintype "passive"))
      (node (ref "U101") (pin "47") (pinfunction "PB10_47") (pintype "bidirectional"))
      (node (ref "U701") (pin "3") (pinfunction "SCL_3") (pintype "bidirectional"))
    )
    (net (code "21") (name "FMU-I2C2_SDA") (class "Default")
      (node (ref "R307") (pin "P$1") (pinfunction "1_P$1") (pintype "passive"))
      (node (ref "U101") (pin "48") (pinfunction "PB11_48") (pintype "bidirectional"))
      (node (ref "U701") (pin "2") (pinfunction "SDA_2") (pintype "bidirectional"))
    )
    (net (code "22") (name "FMU-SWCLK") (class "Default")
      (node (ref "JX301") (pin "4") (pinfunction "S_4") (pintype "passive"))
      (node (ref "U101") (pin "76") (pinfunction "PA14_76") (pintype "bidirectional"))
    )
    (net (code "23") (name "FMU-SWDIO") (class "Default")
      (node (ref "JX301") (pin "2") (pinfunction "S_2") (pintype "passive"))
      (node (ref "U101") (pin "72") (pinfunction "PA13_72") (pintype "bidirectional"))
    )
    (net (code "24") (name "FMU-SWO") (class "Default")
      (node (ref "JX301") (pin "6") (pinfunction "S_6") (pintype "passive"))
      (node (ref "U101") (pin "89") (pinfunction "PB3_89") (pintype "bidirectional"))
    )
    (net (code "25") (name "FMU-UART4_RX") (class "Default")
      (node (ref "U101") (pin "24") (pinfunction "PA1_24") (pintype "bidirectional"))
      (node (ref "U202") (pin "8") (pinfunction "A7_8") (pintype "bidirectional"))
    )
    (net (code "26") (name "FMU-UART4_TX") (class "Default")
      (node (ref "U101") (pin "23") (pinfunction "PA0_23") (pintype "bidirectional"))
      (node (ref "U202") (pin "9") (pinfunction "A8_9") (pintype "bidirectional"))
    )
    (net (code "27") (name "FMU-UART7_RX") (class "Default")
      (node (ref "U101") (pin "38") (pinfunction "PE7_38") (pintype "bidirectional"))
      (node (ref "U202") (pin "4") (pinfunction "A3_4") (pintype "bidirectional"))
    )
    (net (code "28") (name "FMU-UART7_TX") (class "Default")
      (node (ref "U101") (pin "39") (pinfunction "PE8_39") (pintype "bidirectional"))
      (node (ref "U202") (pin "5") (pinfunction "A4_5") (pintype "bidirectional"))
    )
    (net (code "29") (name "FMU-UART8_RX") (class "Default")
      (node (ref "U101") (pin "97") (pinfunction "PE0_97") (pintype "bidirectional"))
      (node (ref "U202") (pin "6") (pinfunction "A5_6") (pintype "bidirectional"))
    )
    (net (code "30") (name "FMU-UART8_TX") (class "Default")
      (node (ref "U101") (pin "98") (pinfunction "PE1_98") (pintype "bidirectional"))
      (node (ref "U202") (pin "7") (pinfunction "A6_7") (pintype "bidirectional"))
    )
    (net (code "31") (name "FMU-USART2_CTS") (class "Default")
      (node (ref "U101") (pin "84") (pinfunction "PD3_84") (pintype "bidirectional"))
      (node (ref "U201") (pin "9") (pinfunction "A8_9") (pintype "bidirectional"))
    )
    (net (code "32") (name "FMU-USART2_RTS") (class "Default")
      (node (ref "U101") (pin "85") (pinfunction "PD4_85") (pintype "bidirectional"))
      (node (ref "U201") (pin "8") (pinfunction "A7_8") (pintype "bidirectional"))
    )
    (net (code "33") (name "FMU-USART2_RX") (class "Default")
      (node (ref "U101") (pin "87") (pinfunction "PD6_87") (pintype "bidirectional"))
      (node (ref "U201") (pin "6") (pinfunction "A5_6") (pintype "bidirectional"))
    )
    (net (code "34") (name "FMU-USART2_TX") (class "Default")
      (node (ref "U101") (pin "86") (pinfunction "PD5_86") (pintype "bidirectional"))
      (node (ref "U201") (pin "7") (pinfunction "A6_7") (pintype "bidirectional"))
    )
    (net (code "35") (name "FMU-USART3_CTS") (class "Default")
      (node (ref "U101") (pin "58") (pinfunction "PD11_58") (pintype "bidirectional"))
      (node (ref "U201") (pin "3") (pinfunction "A2_3") (pintype "bidirectional"))
    )
    (net (code "36") (name "FMU-USART3_RTS") (class "Default")
      (node (ref "U101") (pin "59") (pinfunction "PD12_59") (pintype "bidirectional"))
      (node (ref "U201") (pin "1") (pinfunction "A1_1") (pintype "bidirectional"))
    )
    (net (code "37") (name "FMU-USART3_RX") (class "Default")
      (node (ref "U101") (pin "56") (pinfunction "PD9_56") (pintype "bidirectional"))
      (node (ref "U201") (pin "4") (pinfunction "A3_4") (pintype "bidirectional"))
    )
    (net (code "38") (name "FMU-USART3_TX") (class "Default")
      (node (ref "U101") (pin "55") (pinfunction "PD8_55") (pintype "bidirectional"))
      (node (ref "U201") (pin "5") (pinfunction "A4_5") (pintype "bidirectional"))
    )
    (net (code "39") (name "FMU-VDD_3V3") (class "Default")
      (node (ref "C101") (pin "P$1") (pinfunction "1_P$1") (pintype "passive"))
      (node (ref "C201") (pin "P$1") (pinfunction "1_P$1") (pintype "passive"))
      (node (ref "C202") (pin "P$1") (pinfunction "1_P$1") (pintype "passive"))
      (node (ref "C402") (pin "P$1") (pinfunction "1_P$1") (pintype "passive"))
      (node (ref "C603") (pin "P$1") (pinfunction "1_P$1") (pintype "passive"))
      (node (ref "C604") (pin "P$1") (pinfunction "1_P$1") (pintype "passive"))
      (node (ref "C606") (pin "P$1") (pinfunction "1_P$1") (pintype "passive"))
      (node (ref "C607") (pin "P$1") (pinfunction "1_P$1") (pintype "passive"))
      (node (ref "C608") (pin "P$1") (pinfunction "1_P$1") (pintype "passive"))
      (node (ref "C610") (pin "P$1") (pinfunction "1_P$1") (pintype "passive"))
      (node (ref "C612") (pin "P$1") (pinfunction "1_P$1") (pintype "passive"))
      (node (ref "C701") (pin "P$1") (pinfunction "1_P$1") (pintype "passive"))
      (node (ref "C902") (pin "P$1") (pinfunction "1_P$1") (pintype "passive"))
      (node (ref "JX301") (pin "1") (pinfunction "S_1") (pintype "passive"))
      (node (ref "R301") (pin "P$2") (pinfunction "2_P$2") (pintype "passive"))
      (node (ref "R302") (pin "P$2") (pinfunction "2_P$2") (pintype "passive"))
      (node (ref "R303") (pin "P$2") (pinfunction "2_P$2") (pintype "passive"))
      (node (ref "R304") (pin "P$2") (pinfunction "2_P$2") (pintype "passive"))
      (node (ref "R305") (pin "P$2") (pinfunction "2_P$2") (pintype "passive"))
      (node (ref "R306") (pin "P$2") (pinfunction "2_P$2") (pintype "passive"))
      (node (ref "R307") (pin "P$2") (pinfunction "2_P$2") (pintype "passive"))
      (node (ref "R401") (pin "P$2") (pinfunction "2_P$2") (pintype "passive"))
      (node (ref "R402") (pin "P$2") (pinfunction "2_P$2") (pintype "passive"))
      (node (ref "R608") (pin "P$2") (pinfunction "2_P$2") (pintype "passive"))
      (node (ref "U$605") (pin "7") (pinfunction "VOUT2_7") (pintype "bidirectional"))
      (node (ref "U101") (pin "100") (pinfunction "VDD_100") (pintype "power_in"))
      (node (ref "U101") (pin "11") (pinfunction "VDD_11") (pintype "power_in"))
      (node (ref "U101") (pin "19") (pinfunction "VDD_19") (pintype "power_in"))
      (node (ref "U101") (pin "21") (pinfunction "VREF+_21") (pintype "input"))
      (node (ref "U101") (pin "22") (pinfunction "VDDA_22") (pintype "power_in"))
      (node (ref "U101") (pin "28") (pinfunction "VDD_28") (pintype "power_in"))
      (node (ref "U101") (pin "50") (pinfunction "VDD_50") (pintype "power_in"))
      (node (ref "U101") (pin "75") (pinfunction "VDD_75") (pintype "power_in"))
      (node (ref "U102") (pin "3") (pinfunction "~{W}_3") (pintype "bidirectional"))
      (node (ref "U102") (pin "7") (pinfunction "~{HOLD}_7") (pintype "bidirectional"))
      (node (ref "U102") (pin "8") (pinfunction "VDD_8") (pintype "bidirectional"))
      (node (ref "U201") (pin "10") (pinfunction "OE_10") (pintype "input"))
      (node (ref "U201") (pin "19") (pinfunction "VCCB_19") (pintype "input"))
      (node (ref "U201") (pin "2") (pinfunction "VCCA_2") (pintype "input"))
      (node (ref "U202") (pin "10") (pinfunction "OE_10") (pintype "input"))
      (node (ref "U202") (pin "19") (pinfunction "VCCB_19") (pintype "input"))
      (node (ref "U202") (pin "2") (pinfunction "VCCA_2") (pintype "input"))
      (node (ref "U301") (pin "4") (pinfunction "VCC_4") (pintype "passive"))
      (node (ref "U401") (pin "3") (pinfunction "VCC_3") (pintype "input"))
      (node (ref "U701") (pin "1") (pinfunction "~{SHDN}_1") (pintype "input"))
      (node (ref "U701") (pin "10") (pinfunction "VIN_10") (pintype "power_in"))
      (node (ref "U901") (pin "10") (pinfunction "OE_10") (pintype "input"))
      (node (ref "U901") (pin "19") (pinfunction "VCCB_19") (pintype "input"))
      (node (ref "U901") (pin "2") (pinfunction "VCCA_2") (pintype "input"))
      (node (ref "VDD_3V1101") (pin "P$1") (pinfunction "P$1_P$1") (pintype "passive"))
    )
    (net (code "40") (name "FMU-~{RESET}") (class "Default")
      (node (ref "C609") (pin "P$2") (pinfunction "2_P$2") (pintype "passive"))
      (node (ref "S601") (pin "A1") (pinfunction "1_A1") (pintype "passive"))
      (node (ref "U$605") (pin "3") (pinfunction "POR2_3") (pintype "bidirectional"))
      (node (ref "U101") (pin "14") (pinfunction "NRST_14") (pintype "input"))
      (node (ref "U701") (pin "4") (pinfunction "~{RESET}_4") (pintype "input"))
    )
    (net (code "41") (name "FMU_AUX_ADC1") (class "Default")
      (node (ref "R408") (pin "P$1") (pinfunction "1_P$1") (pintype "passive"))
      (node (ref "U101") (pin "18") (pinfunction "PC3_18") (pintype "bidirectional"))
    )
    (net (code "42") (name "FMU_AUX_ADC2") (class "Default")
      (node (ref "R407") (pin "P$1") (pinfunction "1_P$1") (pintype "passive"))
      (node (ref "U101") (pin "33") (pinfunction "PC4_33") (pintype "bidirectional"))
    )
    (net (code "43") (name "FRAM_MISO") (class "Default")
      (node (ref "U101") (pin "53") (pinfunction "PB14_53") (pintype "bidirectional"))
      (node (ref "U102") (pin "2") (pinfunction "Q_2") (pintype "bidirectional"))
    )
    (net (code "44") (name "FRAM_MOSI") (class "Default")
      (node (ref "U101") (pin "54") (pinfunction "PB15_54") (pintype "bidirectional"))
      (node (ref "U102") (pin "5") (pinfunction "D_5") (pintype "bidirectional"))
    )
    (net (code "45") (name "FRAM_SCK") (class "Default")
      (node (ref "U101") (pin "52") (pinfunction "PB13_52") (pintype "bidirectional"))
      (node (ref "U102") (pin "6") (pinfunction "C_6") (pintype "bidirectional"))
    )
    (net (code "46") (name "GND") (class "Default")
      (node (ref "B601") (pin "2") (pinfunction "NEG_2") (pintype "bidirectional"))
      (node (ref "C1001") (pin "P$2") (pinfunction "2_P$2") (pintype "passive"))
      (node (ref "C1002") (pin "P$2") (pinfunction "2_P$2") (pintype "passive"))
      (node (ref "C1003") (pin "P$2") (pinfunction "2_P$2") (pintype "passive"))
      (node (ref "C1004") (pin "P$2") (pinfunction "2_P$2") (pintype "passive"))
      (node (ref "C101") (pin "P$2") (pinfunction "2_P$2") (pintype "passive"))
      (node (ref "C102") (pin "P$2") (pinfunction "2_P$2") (pintype "passive"))
      (node (ref "C103") (pin "P$1") (pinfunction "1_P$1") (pintype "passive"))
      (node (ref "C201") (pin "P$2") (pinfunction "2_P$2") (pintype "passive"))
      (node (ref "C202") (pin "P$2") (pinfunction "2_P$2") (pintype "passive"))
      (node (ref "C401") (pin "P$2") (pinfunction "2_P$2") (pintype "passive"))
      (node (ref "C402") (pin "P$2") (pinfunction "2_P$2") (pintype "passive"))
      (node (ref "C501") (pin "P$2") (pinfunction "2_P$2") (pintype "passive"))
      (node (ref "C502") (pin "P$2") (pinfunction "2_P$2") (pintype "passive"))
      (node (ref "C503") (pin "P$2") (pinfunction "2_P$2") (pintype "passive"))
      (node (ref "C504") (pin "P$2") (pinfunction "2_P$2") (pintype "passive"))
      (node (ref "C505") (pin "P$2") (pinfunction "2_P$2") (pintype "passive"))
      (node (ref "C506") (pin "P$2") (pinfunction "2_P$2") (pintype "passive"))
      (node (ref "C507") (pin "P$2") (pinfunction "2_P$2") (pintype "passive"))
      (node (ref "C508") (pin "P$2") (pinfunction "2_P$2") (pintype "passive"))
      (node (ref "C509") (pin "P$2") (pinfunction "2_P$2") (pintype "passive"))
      (node (ref "C601") (pin "P$2") (pinfunction "2_P$2") (pintype "passive"))
      (node (ref "C602") (pin "P$1") (pinfunction "1_P$1") (pintype "passive"))
      (node (ref "C603") (pin "P$2") (pinfunction "2_P$2") (pintype "passive"))
      (node (ref "C604") (pin "P$2") (pinfunction "2_P$2") (pintype "passive"))
      (node (ref "C605") (pin "P$2") (pinfunction "2_P$2") (pintype "passive"))
      (node (ref "C606") (pin "P$2") (pinfunction "2_P$2") (pintype "passive"))
      (node (ref "C607") (pin "P$2") (pinfunction "2_P$2") (pintype "passive"))
      (node (ref "C608") (pin "P$2") (pinfunction "2_P$2") (pintype "passive"))
      (node (ref "C609") (pin "P$1") (pinfunction "1_P$1") (pintype "passive"))
      (node (ref "C610") (pin "P$2") (pinfunction "2_P$2") (pintype "passive"))
      (node (ref "C611") (pin "P$2") (pinfunction "2_P$2") (pintype "passive"))
      (node (ref "C612") (pin "P$2") (pinfunction "2_P$2") (pintype "passive"))
      (node (ref "C613") (pin "P$2") (pinfunction "2_P$2") (pintype "passive"))
      (node (ref "C701") (pin "P$2") (pinfunction "2_P$2") (pintype "passive"))
      (node (ref "C702") (pin "P$2") (pinfunction "2_P$2") (pintype "passive"))
      (node (ref "C703") (pin "P$2") (pinfunction "2_P$2") (pintype "passive"))
      (node (ref "C704") (pin "P$2") (pinfunction "2_P$2") (pintype "passive"))
      (node (ref "C801") (pin "P$1") (pinfunction "1_P$1") (pintype "passive"))
      (node (ref "C802") (pin "P$2") (pinfunction "2_P$2") (pintype "passive"))
      (node (ref "C803") (pin "P$2") (pinfunction "2_P$2") (pintype "passive"))
      (node (ref "C804") (pin "P$2") (pinfunction "2_P$2") (pintype "passive"))
      (node (ref "C805") (pin "P$2") (pinfunction "2_P$2") (pintype "passive"))
      (node (ref "C806") (pin "P$1") (pinfunction "1_P$1") (pintype "passive"))
      (node (ref "C901") (pin "P$2") (pinfunction "2_P$2") (pintype "passive"))
      (node (ref "C902") (pin "P$2") (pinfunction "2_P$2") (pintype "passive"))
      (node (ref "C903") (pin "P$2") (pinfunction "2_P$2") (pintype "passive"))
      (node (ref "GND") (pin "P$1") (pinfunction "P$1_P$1") (pintype "passive"))
      (node (ref "GND.") (pin "P$1") (pinfunction "P$1_P$1") (pintype "passive"))
      (node (ref "J201") (pin "P$6") (pinfunction "6_P$6") (pintype "passive"))
      (node (ref "J202") (pin "P$6") (pinfunction "6_P$6") (pintype "passive"))
      (node (ref "J203") (pin "P$6") (pinfunction "6_P$6") (pintype "passive"))
      (node (ref "J204") (pin "P$6") (pinfunction "6_P$6") (pintype "passive"))
      (node (ref "J301") (pin "GND") (pinfunction "5_GND") (pintype "power_in"))
      (node (ref "J301") (pin "GND1") (pinfunction "GND1_GND1") (pintype "bidirectional"))
      (node (ref "J301") (pin "GND2") (pinfunction "GND2_GND2") (pintype "bidirectional"))
      (node (ref "J301") (pin "GND3") (pinfunction "GND3_GND3") (pintype "bidirectional"))
      (node (ref "J301") (pin "GND4") (pinfunction "GND4_GND4") (pintype "bidirectional"))
      (node (ref "J302") (pin "P$4") (pinfunction "4_P$4") (pintype "passive"))
      (node (ref "J401") (pin "P$4") (pinfunction "4_P$4") (pintype "passive"))
      (node (ref "J402") (pin "P$3") (pinfunction "3_P$3") (pintype "passive"))
      (node (ref "J403") (pin "P$7") (pinfunction "7_P$7") (pintype "passive"))
      (node (ref "J404") (pin "P$3") (pinfunction "3_P$3") (pintype "passive"))
      (node (ref "J404") (pin "P$5") (pinfunction "5_P$5") (pintype "passive"))
      (node (ref "J405") (pin "P$4") (pinfunction "4_P$4") (pintype "passive"))
      (node (ref "J601") (pin "P$5") (pinfunction "5_P$5") (pintype "passive"))
      (node (ref "J601") (pin "P$6") (pinfunction "6_P$6") (pintype "passive"))
      (node (ref "J701") (pin "P$2") (pinfunction "2_P$2") (pintype "passive"))
      (node (ref "J801") (pin "P$2") (pinfunction "P$2_P$2") (pintype "bidirectional"))
      (node (ref "J901") (pin "12") (pinfunction "S_12") (pintype "passive"))
      (node (ref "J901") (pin "15") (pinfunction "S_15") (pintype "passive"))
      (node (ref "J901") (pin "18") (pinfunction "S_18") (pintype "passive"))
      (node (ref "J901") (pin "21") (pinfunction "S_21") (pintype "passive"))
      (node (ref "J901") (pin "24") (pinfunction "S_24") (pintype "passive"))
      (node (ref "J901") (pin "27") (pinfunction "S_27") (pintype "passive"))
      (node (ref "J901") (pin "3") (pinfunction "S_3") (pintype "passive"))
      (node (ref "J901") (pin "30") (pinfunction "S_30") (pintype "passive"))
      (node (ref "J901") (pin "33") (pinfunction "S_33") (pintype "passive"))
      (node (ref "J901") (pin "36") (pinfunction "S_36") (pintype "passive"))
      (node (ref "J901") (pin "39") (pinfunction "S_39") (pintype "passive"))
      (node (ref "J901") (pin "42") (pinfunction "S_42") (pintype "passive"))
      (node (ref "J901") (pin "45") (pinfunction "S_45") (pintype "passive"))
      (node (ref "J901") (pin "48") (pinfunction "S_48") (pintype "passive"))
      (node (ref "J901") (pin "6") (pinfunction "S_6") (pintype "passive"))
      (node (ref "J901") (pin "9") (pinfunction "S_9") (pintype "passive"))
      (node (ref "JX301") (pin "3") (pinfunction "S_3") (pintype "passive"))
      (node (ref "JX301") (pin "5") (pinfunction "S_5") (pintype "passive"))
      (node (ref "JX301") (pin "9") (pinfunction "S_9") (pintype "passive"))
      (node (ref "JX801") (pin "3") (pinfunction "GND_3") (pintype "bidirectional"))
      (node (ref "JX802") (pin "3") (pinfunction "S_3") (pintype "passive"))
      (node (ref "JX802") (pin "5") (pinfunction "S_5") (pintype "passive"))
      (node (ref "JX802") (pin "9") (pinfunction "S_9") (pintype "passive"))
      (node (ref "L201") (pin "P$3") (pinfunction "P$3_P$3") (pintype "bidirectional"))
      (node (ref "L201") (pin "P$4") (pinfunction "P$3_P$4") (pintype "bidirectional"))
      (node (ref "L201") (pin "P$5") (pinfunction "P$3_P$5") (pintype "bidirectional"))
      (node (ref "L202") (pin "P$3") (pinfunction "P$3_P$3") (pintype "bidirectional"))
      (node (ref "L202") (pin "P$4") (pinfunction "P$3_P$4") (pintype "bidirectional"))
      (node (ref "L202") (pin "P$5") (pinfunction "P$3_P$5") (pintype "bidirectional"))
      (node (ref "L203") (pin "P$3") (pinfunction "P$3_P$3") (pintype "bidirectional"))
      (node (ref "L203") (pin "P$4") (pinfunction "P$3_P$4") (pintype "bidirectional"))
      (node (ref "L203") (pin "P$5") (pinfunction "P$3_P$5") (pintype "bidirectional"))
      (node (ref "L401") (pin "P$3") (pinfunction "P$3_P$3") (pintype "bidirectional"))
      (node (ref "L401") (pin "P$4") (pinfunction "P$3_P$4") (pintype "bidirectional"))
      (node (ref "L401") (pin "P$5") (pinfunction "P$3_P$5") (pintype "bidirectional"))
      (node (ref "L402") (pin "P$3") (pinfunction "P$3_P$3") (pintype "bidirectional"))
      (node (ref "L402") (pin "P$4") (pinfunction "P$3_P$4") (pintype "bidirectional"))
      (node (ref "L402") (pin "P$5") (pinfunction "P$3_P$5") (pintype "bidirectional"))
      (node (ref "L403") (pin "P$3") (pinfunction "P$3_P$3") (pintype "bidirectional"))
      (node (ref "L403") (pin "P$4") (pinfunction "P$3_P$4") (pintype "bidirectional"))
      (node (ref "L403") (pin "P$5") (pinfunction "P$3_P$5") (pintype "bidirectional"))
      (node (ref "L404") (pin "P$3") (pinfunction "P$3_P$3") (pintype "bidirectional"))
      (node (ref "L404") (pin "P$4") (pinfunction "P$3_P$4") (pintype "bidirectional"))
      (node (ref "L404") (pin "P$5") (pinfunction "P$3_P$5") (pintype "bidirectional"))
      (node (ref "L601") (pin "P$3") (pinfunction "P$3_P$3") (pintype "bidirectional"))
      (node (ref "L601") (pin "P$4") (pinfunction "P$3_P$4") (pintype "bidirectional"))
      (node (ref "L601") (pin "P$5") (pinfunction "P$3_P$5") (pintype "bidirectional"))
      (node (ref "L602") (pin "P$3") (pinfunction "P$3_P$3") (pintype "bidirectional"))
      (node (ref "L602") (pin "P$4") (pinfunction "P$3_P$4") (pintype "bidirectional"))
      (node (ref "L602") (pin "P$5") (pinfunction "P$3_P$5") (pintype "bidirectional"))
      (node (ref "L603") (pin "P$3") (pinfunction "P$3_P$3") (pintype "bidirectional"))
      (node (ref "L603") (pin "P$4") (pinfunction "P$3_P$4") (pintype "bidirectional"))
      (node (ref "L603") (pin "P$5") (pinfunction "P$3_P$5") (pintype "bidirectional"))
      (node (ref "L901") (pin "P$3") (pinfunction "P$3_P$3") (pintype "bidirectional"))
      (node (ref "L901") (pin "P$4") (pinfunction "P$3_P$4") (pintype "bidirectional"))
      (node (ref "L901") (pin "P$5") (pinfunction "P$3_P$5") (pintype "bidirectional"))
      (node (ref "R1001") (pin "P$1") (pinfunction "1_P$1") (pintype "passive"))
      (node (ref "R1002") (pin "P$1") (pinfunction "1_P$1") (pintype "passive"))
      (node (ref "R102") (pin "P$2") (pinfunction "2_P$2") (pintype "passive"))
      (node (ref "R11") (pin "P$2") (pinfunction "2_P$2") (pintype "passive"))
      (node (ref "R403") (pin "P$1") (pinfunction "1_P$1") (pintype "passive"))
      (node (ref "R5") (pin "P$2") (pinfunction "2_P$2") (pintype "passive"))
      (node (ref "R602") (pin "P$2") (pinfunction "2_P$2") (pintype "passive"))
      (node (ref "R606") (pin "P$2") (pinfunction "2_P$2") (pintype "passive"))
      (node (ref "R607") (pin "P$2") (pinfunction "2_P$2") (pintype "passive"))
      (node (ref "R610") (pin "P$2") (pinfunction "2_P$2") (pintype "passive"))
      (node (ref "R611") (pin "P$1") (pinfunction "1_P$1") (pintype "passive"))
      (node (ref "R702") (pin "P$2") (pinfunction "2_P$2") (pintype "passive"))
      (node (ref "R704") (pin "P$1") (pinfunction "1_P$1") (pintype "passive"))
      (node (ref "R706") (pin "P$2") (pinfunction "2_P$2") (pintype "passive"))
      (node (ref "R708") (pin "P$1") (pinfunction "1_P$1") (pintype "passive"))
      (node (ref "R711") (pin "P$1") (pinfunction "1_P$1") (pintype "passive"))
      (node (ref "R713") (pin "P$2") (pinfunction "2_P$2") (pintype "passive"))
      (node (ref "R8") (pin "P$2") (pinfunction "2_P$2") (pintype "passive"))
      (node (ref "R801") (pin "P$2") (pinfunction "2_P$2") (pintype "passive"))
      (node (ref "R802") (pin "P$2") (pinfunction "2_P$2") (pintype "passive"))
      (node (ref "R919") (pin "P$1") (pinfunction "1_P$1") (pintype "passive"))
      (node (ref "S601") (pin "B3") (pinfunction "2_B3") (pintype "passive"))
      (node (ref "S801") (pin "B3") (pinfunction "2_B3") (pintype "passive"))
      (node (ref "U$1") (pin "2") (pinfunction "S_2") (pintype "passive"))
      (node (ref "U$1001") (pin "2") (pinfunction "VSS_2") (pintype "bidirectional"))
      (node (ref "U$1001") (pin "5") (pinfunction "~{CE}_5") (pintype "bidirectional"))
      (node (ref "U$1001") (pin "6") (pinfunction "VBAT_6") (pintype "bidirectional"))
      (node (ref "U$1001") (pin "GND") (pinfunction "VSS_GND") (pintype "bidirectional"))
      (node (ref "U$1001") (pin "P$2") (pinfunction "VSS_P$2") (pintype "bidirectional"))
      (node (ref "U$1001") (pin "P$3") (pinfunction "VSS_P$3") (pintype "bidirectional"))
      (node (ref "U$1002") (pin "2") (pinfunction "GND_2") (pintype "bidirectional"))
      (node (ref "U$1002") (pin "GND") (pinfunction "GND_GND") (pintype "bidirectional"))
      (node (ref "U$2") (pin "P$10") (pinfunction "GND_P$10") (pintype "bidirectional"))
      (node (ref "U$2") (pin "P$24") (pinfunction "HYS_P$24") (pintype "bidirectional"))
      (node (ref "U$2") (pin "P$25") (pinfunction "GND_P$25") (pintype "bidirectional"))
      (node (ref "U$201") (pin "A") (pinfunction "A_A") (pintype "passive"))
      (node (ref "U$202") (pin "A") (pinfunction "A_A") (pintype "passive"))
      (node (ref "U$203") (pin "A") (pinfunction "A_A") (pintype "passive"))
      (node (ref "U$301") (pin "2") (pinfunction "GND_2") (pintype "bidirectional"))
      (node (ref "U$401") (pin "A") (pinfunction "A_A") (pintype "passive"))
      (node (ref "U$402") (pin "A") (pinfunction "A_A") (pintype "passive"))
      (node (ref "U$403") (pin "A") (pinfunction "A_A") (pintype "passive"))
      (node (ref "U$404") (pin "A") (pinfunction "A_A") (pintype "passive"))
      (node (ref "U$501") (pin "10") (pinfunction "RSRV_10") (pintype "bidirectional"))
      (node (ref "U$501") (pin "12") (pinfunction "GND_12") (pintype "bidirectional"))
      (node (ref "U$501") (pin "13") (pinfunction "GND_13") (pintype "bidirectional"))
      (node (ref "U$501") (pin "16") (pinfunction "GND_16") (pintype "bidirectional"))
      (node (ref "U$501") (pin "5") (pinfunction "GND_5") (pintype "bidirectional"))
      (node (ref "U$6") (pin "A") (pinfunction "A_A") (pintype "passive"))
      (node (ref "U$602") (pin "2") (pinfunction "VSS_2") (pintype "bidirectional"))
      (node (ref "U$602") (pin "6") (pinfunction "VBAT_6") (pintype "bidirectional"))
      (node (ref "U$602") (pin "GND") (pinfunction "VSS_GND") (pintype "bidirectional"))
      (node (ref "U$602") (pin "P$2") (pinfunction "VSS_P$2") (pintype "bidirectional"))
      (node (ref "U$602") (pin "P$3") (pinfunction "VSS_P$3") (pintype "bidirectional"))
      (node (ref "U$604") (pin "2") (pinfunction "VSS_2") (pintype "bidirectional"))
      (node (ref "U$604") (pin "6") (pinfunction "VBAT_6") (pintype "bidirectional"))
      (node (ref "U$604") (pin "GND") (pinfunction "VSS_GND") (pintype "bidirectional"))
      (node (ref "U$604") (pin "P$2") (pinfunction "VSS_P$2") (pintype "bidirectional"))
      (node (ref "U$604") (pin "P$3") (pinfunction "VSS_P$3") (pintype "bidirectional"))
      (node (ref "U$605") (pin "2") (pinfunction "GND_2") (pintype "bidirectional"))
      (node (ref "U$605") (pin "GND") (pinfunction "GND_GND") (pintype "bidirectional"))
      (node (ref "U$701") (pin "A") (pinfunction "A_A") (pintype "passive"))
      (node (ref "U$801") (pin "A") (pinfunction "A_A") (pintype "passive"))
      (node (ref "U$901") (pin "A") (pinfunction "A_A") (pintype "passive"))
      (node (ref "U$902") (pin "A") (pinfunction "A_A") (pintype "passive"))
      (node (ref "U101") (pin "10") (pinfunction "VSS_10") (pintype "power_in"))
      (node (ref "U101") (pin "20") (pinfunction "VSSA_20") (pintype "power_in"))
      (node (ref "U101") (pin "27") (pinfunction "VSS_27") (pintype "power_in"))
      (node (ref "U101") (pin "74") (pinfunction "VSS_74") (pintype "power_in"))
      (node (ref "U101") (pin "99") (pinfunction "VSS_99") (pintype "power_in"))
      (node (ref "U102") (pin "4") (pinfunction "VSS_4") (pintype "bidirectional"))
      (node (ref "U201") (pin "11") (pinfunction "GND_11") (pintype "power_in"))
      (node (ref "U202") (pin "11") (pinfunction "GND_11") (pintype "power_in"))
      (node (ref "U301") (pin "6") (pinfunction "GND_6") (pintype "power_in"))
      (node (ref "U401") (pin "2") (pinfunction "GND_2") (pintype "power_in"))
      (node (ref "U401") (pin "5") (pinfunction "SHDN_5") (pintype "input"))
      (node (ref "U401") (pin "8") (pinfunction "RS_8") (pintype "input"))
      (node (ref "U501") (pin "10") (pinfunction "RES_P10_GND_10") (pintype "bidirectional"))
      (node (ref "U501") (pin "11") (pinfunction "RES_P11_GND_11") (pintype "bidirectional"))
      (node (ref "U501") (pin "12") (pinfunction "RES_P12_GND_12") (pintype "bidirectional"))
      (node (ref "U501") (pin "13") (pinfunction "GND_13") (pintype "bidirectional"))
      (node (ref "U501") (pin "8") (pinfunction "RES_P8_GND_8") (pintype "bidirectional"))
      (node (ref "U501") (pin "9") (pinfunction "RES_P9_GND_9") (pintype "bidirectional"))
      (node (ref "U502") (pin "10") (pinfunction "GND_10") (pintype "bidirectional"))
      (node (ref "U502") (pin "11") (pinfunction "GND_11") (pintype "bidirectional"))
      (node (ref "U502") (pin "12") (pinfunction "GND_12") (pintype "bidirectional"))
      (node (ref "U502") (pin "13") (pinfunction "GND_13") (pintype "bidirectional"))
      (node (ref "U502") (pin "9") (pinfunction "GND_9") (pintype "bidirectional"))
      (node (ref "U503") (pin "2") (pinfunction "PS_2") (pintype "bidirectional"))
      (node (ref "U503") (pin "3") (pinfunction "GND_3") (pintype "bidirectional"))
      (node (ref "U701") (pin "5") (pinfunction "GND_5") (pintype "power_in"))
      (node (ref "U702") (pin "4") (pinfunction "GND_4") (pintype "power_in"))
      (node (ref "U801") (pin "23") (pinfunction "VSS_1_23") (pintype "power_in"))
      (node (ref "U801") (pin "35") (pinfunction "VSS_2_35") (pintype "power_in"))
      (node (ref "U801") (pin "47") (pinfunction "VSS_3_47") (pintype "power_in"))
      (node (ref "U801") (pin "8") (pinfunction "VSSA_8") (pintype "power_in"))
      (node (ref "U901") (pin "11") (pinfunction "GND_11") (pintype "power_in"))
      (node (ref "U902") (pin "11") (pinfunction "GND_11") (pintype "power_in"))
      (node (ref "U903") (pin "1") (pinfunction "~{1OE}_1") (pintype "input"))
      (node (ref "U903") (pin "4") (pinfunction "GND_4") (pintype "power_in"))
      (node (ref "X101") (pin "2") (pinfunction "NC_2_2") (pintype "power_in"))
      (node (ref "X101") (pin "4") (pinfunction "NC_4_4") (pintype "power_in"))
      (node (ref "X801") (pin "2") (pinfunction "NC_2_2") (pintype "power_in"))
      (node (ref "X801") (pin "4") (pinfunction "NC_4_4") (pintype "power_in"))
    )
    (net (code "47") (name "GPIO_EXT_1") (class "Default")
      (node (ref "J403") (pin "P$6") (pinfunction "6_P$6") (pintype "passive"))
      (node (ref "U101") (pin "8") (pinfunction "PC14_8") (pintype "bidirectional"))
    )
    (net (code "48") (name "GYRO_DRDY") (class "Default")
      (node (ref "U$1") (pin "5") (pinfunction "S_5") (pintype "passive"))
      (node (ref "U101") (pin "35") (pinfunction "PB0_35") (pintype "bidirectional"))
      (node (ref "U501") (pin "6") (pinfunction "DRDY/INT2_6") (pintype "output"))
      (node (ref "U502") (pin "6") (pinfunction "DRDY/INT2_6") (pintype "bidirectional"))
    )
    (net (code "49") (name "IO-BOOT0") (class "Default")
      (node (ref "IO-BOOT1101") (pin "P$1") (pinfunction "P$1_P$1") (pintype "passive"))
      (node (ref "R801") (pin "P$1") (pinfunction "1_P$1") (pintype "passive"))
      (node (ref "U801") (pin "44") (pinfunction "BOOT0_44") (pintype "input"))
    )
    (net (code "50") (name "IO-CH1") (class "Default")
      (node (ref "U801") (pin "10") (pinfunction "PA0_10") (pintype "bidirectional"))
      (node (ref "U902") (pin "9") (pinfunction "A8_9") (pintype "bidirectional"))
    )
    (net (code "51") (name "IO-CH2") (class "Default")
      (node (ref "U801") (pin "11") (pinfunction "PA1_11") (pintype "bidirectional"))
      (node (ref "U902") (pin "8") (pinfunction "A7_8") (pintype "bidirectional"))
    )
    (net (code "52") (name "IO-CH3") (class "Default")
      (node (ref "U801") (pin "45") (pinfunction "PB8_45") (pintype "bidirectional"))
      (node (ref "U902") (pin "7") (pinfunction "A6_7") (pintype "bidirectional"))
    )
    (net (code "53") (name "IO-CH4") (class "Default")
      (node (ref "U801") (pin "46") (pinfunction "PB9_46") (pintype "bidirectional"))
      (node (ref "U902") (pin "6") (pinfunction "A5_6") (pintype "bidirectional"))
    )
    (net (code "54") (name "IO-CH5") (class "Default")
      (node (ref "U801") (pin "16") (pinfunction "PA6_16") (pintype "bidirectional"))
      (node (ref "U902") (pin "5") (pinfunction "A4_5") (pintype "bidirectional"))
    )
    (net (code "55") (name "IO-CH6") (class "Default")
      (node (ref "U801") (pin "17") (pinfunction "PA7_17") (pintype "bidirectional"))
      (node (ref "U902") (pin "4") (pinfunction "A3_4") (pintype "bidirectional"))
    )
    (net (code "56") (name "IO-CH7") (class "Default")
      (node (ref "U801") (pin "18") (pinfunction "PB0_18") (pintype "bidirectional"))
      (node (ref "U902") (pin "3") (pinfunction "A2_3") (pintype "bidirectional"))
    )
    (net (code "57") (name "IO-CH8") (class "Default")
      (node (ref "U801") (pin "19") (pinfunction "PB1_19") (pintype "bidirectional"))
      (node (ref "U902") (pin "1") (pinfunction "A1_1") (pintype "bidirectional"))
    )
    (net (code "58") (name "IO-SWCLK") (class "Default")
      (node (ref "JX802") (pin "4") (pinfunction "S_4") (pintype "passive"))
      (node (ref "U801") (pin "37") (pinfunction "PA14_37") (pintype "bidirectional"))
    )
    (net (code "59") (name "IO-SWDIO") (class "Default")
      (node (ref "JX802") (pin "2") (pinfunction "S_2") (pintype "passive"))
      (node (ref "U801") (pin "34") (pinfunction "PA13_34") (pintype "bidirectional"))
    )
    (net (code "60") (name "IO-SWO") (class "Default")
      (node (ref "JX802") (pin "6") (pinfunction "S_6") (pintype "passive"))
      (node (ref "U801") (pin "39") (pinfunction "PB3_39") (pintype "bidirectional"))
    )
    (net (code "61") (name "IO-USART1_RX") (class "Default")
      (node (ref "J801") (pin "P$3") (pinfunction "P$3_P$3") (pintype "bidirectional"))
      (node (ref "JX801") (pin "2") (pinfunction "+5V_2") (pintype "bidirectional"))
      (node (ref "U801") (pin "31") (pinfunction "PA10_31") (pintype "bidirectional"))
    )
    (net (code "62") (name "IO-USART1_TX") (class "Default")
      (node (ref "JX801") (pin "1") (pinfunction "PPM_1") (pintype "bidirectional"))
      (node (ref "R101") (pin "P$2") (pinfunction "2_P$2") (pintype "passive"))
      (node (ref "U801") (pin "30") (pinfunction "PA9_30") (pintype "bidirectional"))
    )
    (net (code "63") (name "IO-VDD_3V3") (class "Default")
      (node (ref "C1004") (pin "P$1") (pinfunction "1_P$1") (pintype "passive"))
      (node (ref "C802") (pin "P$1") (pinfunction "1_P$1") (pintype "passive"))
      (node (ref "C803") (pin "P$1") (pinfunction "1_P$1") (pintype "passive"))
      (node (ref "C804") (pin "P$1") (pinfunction "1_P$1") (pintype "passive"))
      (node (ref "C901") (pin "P$1") (pinfunction "1_P$1") (pintype "passive"))
      (node (ref "C903") (pin "P$1") (pinfunction "1_P$1") (pintype "passive"))
      (node (ref "J702") (pin "P$1") (pinfunction "1_P$1") (pintype "passive"))
      (node (ref "JX802") (pin "1") (pinfunction "S_1") (pintype "passive"))
      (node (ref "U$1002") (pin "7") (pinfunction "VOUT2_7") (pintype "bidirectional"))
      (node (ref "U$701") (pin "C") (pinfunction "C_C") (pintype "passive"))
      (node (ref "U801") (pin "24") (pinfunction "VDD_1_24") (pintype "power_in"))
      (node (ref "U801") (pin "36") (pinfunction "VDD_2_36") (pintype "power_in"))
      (node (ref "U801") (pin "48") (pinfunction "VDD_3_48") (pintype "power_in"))
      (node (ref "U801") (pin "9") (pinfunction "VDDA_9") (pintype "power_in"))
      (node (ref "U902") (pin "10") (pinfunction "OE_10") (pintype "input"))
      (node (ref "U902") (pin "19") (pinfunction "VCCB_19") (pintype "input"))
      (node (ref "U902") (pin "2") (pinfunction "VCCA_2") (pintype "input"))
      (node (ref "U903") (pin "8") (pinfunction "VCC_8") (pintype "power_in"))
    )
    (net (code "64") (name "IO-VDD_5V5") (class "Default")
      (node (ref "C1001") (pin "P$1") (pinfunction "1_P$1") (pintype "passive"))
      (node (ref "D1001") (pin "3") (pinfunction "CC_3") (pintype "passive"))
      (node (ref "J901") (pin "2") (pinfunction "S_2") (pintype "passive"))
      (node (ref "LED702") (pin "A") (pinfunction "A_A") (pintype "passive"))
      (node (ref "LED703") (pin "A") (pinfunction "A_A") (pintype "passive"))
      (node (ref "LED705") (pin "A") (pinfunction "A_A") (pintype "passive"))
      (node (ref "U$1002") (pin "1") (pinfunction "VIN_1") (pintype "bidirectional"))
      (node (ref "U$1002") (pin "4") (pinfunction "EN2_4") (pintype "bidirectional"))
    )
    (net (code "65") (name "IO-~{RESET}") (class "Default")
      (node (ref "C801") (pin "P$2") (pinfunction "2_P$2") (pintype "passive"))
      (node (ref "S801") (pin "A1") (pinfunction "1_A1") (pintype "passive"))
      (node (ref "U$1002") (pin "3") (pinfunction "POR2_3") (pintype "bidirectional"))
      (node (ref "U801") (pin "7") (pinfunction "NRST_7") (pintype "input"))
    )
    (net (code "66") (name "IO-~{VDD_SERVO_IN_FAULT}") (class "Default")
      (node (ref "U$1001") (pin "4") (pinfunction "~{FAULT}_4") (pintype "bidirectional"))
      (node (ref "U801") (pin "38") (pinfunction "PA15_38") (pintype "bidirectional"))
    )
    (net (code "67") (name "MAG_DRDY") (class "Default")
      (node (ref "U$1") (pin "4") (pinfunction "S_4") (pintype "passive"))
      (node (ref "U$501") (pin "9") (pinfunction "INT2_9") (pintype "bidirectional"))
      (node (ref "U101") (pin "36") (pinfunction "PB1_36") (pintype "bidirectional"))
    )
    (net (code "68") (name "Net-(C102-1)") (class "Default")
      (node (ref "C102") (pin "P$1") (pinfunction "1_P$1") (pintype "passive"))
      (node (ref "U101") (pin "12") (pinfunction "OSC_IN_12") (pintype "input"))
      (node (ref "X101") (pin "3") (pinfunction "3_3") (pintype "bidirectional"))
    )
    (net (code "69") (name "Net-(C103-2)") (class "Default")
      (node (ref "C103") (pin "P$2") (pinfunction "2_P$2") (pintype "passive"))
      (node (ref "U101") (pin "13") (pinfunction "OSC_OUT_13") (pintype "output"))
      (node (ref "X101") (pin "1") (pinfunction "1_1") (pintype "bidirectional"))
    )
    (net (code "70") (name "Net-(C504-1)") (class "Default")
      (node (ref "C504") (pin "P$1") (pinfunction "1_P$1") (pintype "passive"))
      (node (ref "U501") (pin "14") (pinfunction "PLLFILT_14") (pintype "bidirectional"))
    )
    (net (code "71") (name "Net-(C505-1)") (class "Default")
      (node (ref "C505") (pin "P$1") (pinfunction "1_P$1") (pintype "passive"))
      (node (ref "U502") (pin "14") (pinfunction "CAP_14") (pintype "bidirectional"))
    )
    (net (code "72") (name "Net-(C509-1)") (class "Default")
      (node (ref "C509") (pin "P$1") (pinfunction "1_P$1") (pintype "passive"))
      (node (ref "U$501") (pin "15") (pinfunction "C1_15") (pintype "bidirectional"))
    )
    (net (code "73") (name "Net-(C510-1)") (class "Default")
      (node (ref "C510") (pin "P$1") (pinfunction "1_P$1") (pintype "passive"))
      (node (ref "U$501") (pin "2") (pinfunction "SETC_2") (pintype "bidirectional"))
    )
    (net (code "74") (name "Net-(C510-2)") (class "Default")
      (node (ref "C510") (pin "P$2") (pinfunction "2_P$2") (pintype "passive"))
      (node (ref "U$501") (pin "3") (pinfunction "SETP_3") (pintype "bidirectional"))
    )
    (net (code "75") (name "Net-(C601-1)") (class "Default")
      (node (ref "C601") (pin "P$1") (pinfunction "1_P$1") (pintype "passive"))
      (node (ref "L603") (pin "P$2") (pinfunction "P$2_P$2") (pintype "bidirectional"))
      (node (ref "R603") (pin "P$2") (pinfunction "2_P$2") (pintype "passive"))
      (node (ref "U$605") (pin "1") (pinfunction "VIN_1") (pintype "bidirectional"))
      (node (ref "U$605") (pin "4") (pinfunction "EN2_4") (pintype "bidirectional"))
    )
    (net (code "76") (name "Net-(C602-2)") (class "Default")
      (node (ref "C602") (pin "P$2") (pinfunction "2_P$2") (pintype "passive"))
      (node (ref "U$605") (pin "6") (pinfunction "CSET_6") (pintype "bidirectional"))
    )
    (net (code "77") (name "Net-(C611-1)") (class "Default")
      (node (ref "C611") (pin "P$1") (pinfunction "1_P$1") (pintype "passive"))
      (node (ref "U101") (pin "49") (pinfunction "VCAP_1_49") (pintype "power_in"))
    )
    (net (code "78") (name "Net-(C613-1)") (class "Default")
      (node (ref "C613") (pin "P$1") (pinfunction "1_P$1") (pintype "passive"))
      (node (ref "U101") (pin "73") (pinfunction "VCAP_2_73") (pintype "power_in"))
    )
    (net (code "79") (name "Net-(C703-1)") (class "Default")
      (node (ref "C703") (pin "P$1") (pinfunction "1_P$1") (pintype "passive"))
      (node (ref "J701") (pin "P$1") (pinfunction "1_P$1") (pintype "passive"))
      (node (ref "R703") (pin "P$1") (pinfunction "1_P$1") (pintype "passive"))
      (node (ref "U702") (pin "1") (pinfunction "OUT_1") (pintype "output"))
    )
    (net (code "80") (name "Net-(C704-1)") (class "Default")
      (node (ref "C704") (pin "P$1") (pinfunction "1_P$1") (pintype "passive"))
      (node (ref "R705") (pin "P$1") (pinfunction "1_P$1") (pintype "passive"))
      (node (ref "U702") (pin "6") (pinfunction "VCC_6") (pintype "bidirectional"))
    )
    (net (code "81") (name "Net-(C805-1)") (class "Default")
      (node (ref "C805") (pin "P$1") (pinfunction "1_P$1") (pintype "passive"))
      (node (ref "U801") (pin "5") (pinfunction "PD0/OSC<=_5") (pintype "bidirectional"))
      (node (ref "X801") (pin "3") (pinfunction "3_3") (pintype "bidirectional"))
    )
    (net (code "82") (name "Net-(C806-2)") (class "Default")
      (node (ref "C806") (pin "P$2") (pinfunction "2_P$2") (pintype "passive"))
      (node (ref "U801") (pin "6") (pinfunction "PD1/OSC=>_6") (pintype "bidirectional"))
      (node (ref "X801") (pin "1") (pinfunction "1_1") (pintype "bidirectional"))
    )
    (net (code "83") (name "Net-(C1002-1)") (class "Default")
      (node (ref "C1002") (pin "P$1") (pinfunction "1_P$1") (pintype "passive"))
      (node (ref "U$1002") (pin "6") (pinfunction "CSET_6") (pintype "bidirectional"))
    )
    (net (code "84") (name "Net-(D1-C)") (class "Default")
      (node (ref "D1") (pin "CATHODE") (pinfunction "C_CATHODE") (pintype "passive"))
      (node (ref "L901") (pin "P$1") (pinfunction "P$1_P$1") (pintype "bidirectional"))
      (node (ref "U$6") (pin "C") (pinfunction "C_C") (pintype "passive"))
    )
    (net (code "85") (name "Net-(D1001-A1)") (class "Default")
      (node (ref "D1001") (pin "1") (pinfunction "A1_1") (pintype "passive"))
      (node (ref "F2") (pin "2") (pinfunction "2_2") (pintype "bidirectional"))
    )
    (net (code "86") (name "Net-(D1001-A2)") (class "Default")
      (node (ref "D1001") (pin "2") (pinfunction "A2_2") (pintype "passive"))
      (node (ref "U$1001") (pin "8") (pinfunction "OUT_8") (pintype "bidirectional"))
    )
    (net (code "87") (name "Net-(J201-1)") (class "Default")
      (node (ref "J201") (pin "P$1") (pinfunction "1_P$1") (pintype "passive"))
      (node (ref "L201") (pin "P$2") (pinfunction "P$2_P$2") (pintype "bidirectional"))
      (node (ref "U$201") (pin "C") (pinfunction "C_C") (pintype "passive"))
    )
    (net (code "88") (name "Net-(J202-1)") (class "Default")
      (node (ref "J202") (pin "P$1") (pinfunction "1_P$1") (pintype "passive"))
      (node (ref "L202") (pin "P$2") (pinfunction "P$2_P$2") (pintype "bidirectional"))
      (node (ref "U$202") (pin "C") (pinfunction "C_C") (pintype "passive"))
    )
    (net (code "89") (name "Net-(J203-1)") (class "Default")
      (node (ref "J203") (pin "P$1") (pinfunction "1_P$1") (pintype "passive"))
      (node (ref "J204") (pin "P$1") (pinfunction "1_P$1") (pintype "passive"))
      (node (ref "L203") (pin "P$2") (pinfunction "P$2_P$2") (pintype "bidirectional"))
      (node (ref "U$203") (pin "C") (pinfunction "C_C") (pintype "passive"))
    )
    (net (code "90") (name "Net-(J203-4)") (class "Default")
      (node (ref "J203") (pin "P$4") (pinfunction "4_P$4") (pintype "passive"))
      (node (ref "R12") (pin "P$2") (pinfunction "2_P$2") (pintype "passive"))
    )
    (net (code "91") (name "Net-(J203-5)") (class "Default")
      (node (ref "J203") (pin "P$5") (pinfunction "5_P$5") (pintype "passive"))
      (node (ref "R13") (pin "P$2") (pinfunction "2_P$2") (pintype "passive"))
    )
    (net (code "92") (name "Net-(J301-2)") (class "Default")
      (node (ref "J301") (pin "D-") (pinfunction "2_D-") (pintype "bidirectional"))
      (node (ref "J302") (pin "P$3") (pinfunction "3_P$3") (pintype "passive"))
      (node (ref "U$301") (pin "1") (pinfunction "D1I_1") (pintype "bidirectional"))
    )
    (net (code "93") (name "Net-(J301-3)") (class "Default")
      (node (ref "J301") (pin "D+") (pinfunction "3_D+") (pintype "bidirectional"))
      (node (ref "J302") (pin "P$2") (pinfunction "2_P$2") (pintype "passive"))
      (node (ref "U$301") (pin "3") (pinfunction "D2I_3") (pintype "bidirectional"))
    )
    (net (code "94") (name "Net-(J401-1)") (class "Default")
      (node (ref "J401") (pin "P$1") (pinfunction "1_P$1") (pintype "passive"))
      (node (ref "J402") (pin "P$1") (pinfunction "1_P$1") (pintype "passive"))
      (node (ref "L401") (pin "P$2") (pinfunction "P$2_P$2") (pintype "bidirectional"))
      (node (ref "U$401") (pin "C") (pinfunction "C_C") (pintype "passive"))
    )
    (net (code "95") (name "Net-(J401-2)") (class "Default")
      (node (ref "J401") (pin "P$2") (pinfunction "2_P$2") (pintype "passive"))
      (node (ref "R404") (pin "P$2") (pinfunction "2_P$2") (pintype "passive"))
    )
    (net (code "96") (name "Net-(J401-3)") (class "Default")
      (node (ref "J401") (pin "P$3") (pinfunction "3_P$3") (pintype "passive"))
      (node (ref "R405") (pin "P$2") (pinfunction "2_P$2") (pintype "passive"))
    )
    (net (code "97") (name "Net-(J403-1)") (class "Default")
      (node (ref "J403") (pin "P$1") (pinfunction "1_P$1") (pintype "passive"))
      (node (ref "L402") (pin "P$2") (pinfunction "P$2_P$2") (pintype "bidirectional"))
      (node (ref "U$402") (pin "C") (pinfunction "C_C") (pintype "passive"))
    )
    (net (code "98") (name "Net-(J404-1)") (class "Default")
      (node (ref "J404") (pin "P$1") (pinfunction "1_P$1") (pintype "passive"))
      (node (ref "L404") (pin "P$2") (pinfunction "P$2_P$2") (pintype "bidirectional"))
      (node (ref "U$403") (pin "C") (pinfunction "C_C") (pintype "passive"))
    )
    (net (code "99") (name "Net-(J404-2)") (class "Default")
      (node (ref "J404") (pin "P$2") (pinfunction "2_P$2") (pintype "passive"))
      (node (ref "R407") (pin "P$2") (pinfunction "2_P$2") (pintype "passive"))
    )
    (net (code "100") (name "Net-(J404-4)") (class "Default")
      (node (ref "J404") (pin "P$4") (pinfunction "4_P$4") (pintype "passive"))
      (node (ref "R408") (pin "P$2") (pinfunction "2_P$2") (pintype "passive"))
    )
    (net (code "101") (name "Net-(J405-1)") (class "Default")
      (node (ref "J405") (pin "P$1") (pinfunction "1_P$1") (pintype "passive"))
      (node (ref "L403") (pin "P$2") (pinfunction "P$2_P$2") (pintype "bidirectional"))
      (node (ref "U$404") (pin "C") (pinfunction "C_C") (pintype "passive"))
    )
    (net (code "102") (name "Net-(J601-3)") (class "Default")
      (node (ref "J601") (pin "P$3") (pinfunction "3_P$3") (pintype "passive"))
      (node (ref "L601") (pin "P$1") (pinfunction "P$1_P$1") (pintype "bidirectional"))
    )
    (net (code "103") (name "Net-(J601-4)") (class "Default")
      (node (ref "J601") (pin "P$4") (pinfunction "4_P$4") (pintype "passive"))
      (node (ref "L602") (pin "P$1") (pinfunction "P$1_P$1") (pintype "bidirectional"))
    )
    (net (code "104") (name "Net-(J702-2)") (class "Default")
      (node (ref "J702") (pin "P$2") (pinfunction "2_P$2") (pintype "passive"))
      (node (ref "R710") (pin "P$1") (pinfunction "1_P$1") (pintype "passive"))
    )
    (net (code "105") (name "Net-(J901A-S)") (class "Default")
      (node (ref "J901") (pin "1") (pinfunction "S_1") (pintype "passive"))
      (node (ref "R909") (pin "P$2") (pinfunction "2_P$2") (pintype "passive"))
    )
    (net (code "106") (name "Net-(J901B-S)") (class "Default")
      (node (ref "J901") (pin "10") (pinfunction "S_10") (pintype "passive"))
      (node (ref "R914") (pin "P$2") (pinfunction "2_P$2") (pintype "passive"))
    )
    (net (code "107") (name "Net-(J901C-S)") (class "Default")
      (node (ref "J901") (pin "13") (pinfunction "S_13") (pintype "passive"))
      (node (ref "R906") (pin "P$2") (pinfunction "2_P$2") (pintype "passive"))
    )
    (net (code "108") (name "Net-(J901D-S)") (class "Default")
      (node (ref "J901") (pin "16") (pinfunction "S_16") (pintype "passive"))
      (node (ref "R915") (pin "P$2") (pinfunction "2_P$2") (pintype "passive"))
    )
    (net (code "109") (name "Net-(J901E-S)") (class "Default")
      (node (ref "J901") (pin "19") (pinfunction "S_19") (pintype "passive"))
      (node (ref "R907") (pin "P$2") (pinfunction "2_P$2") (pintype "passive"))
    )
    (net (code "110") (name "Net-(J901G-S)") (class "Default")
      (node (ref "J901") (pin "22") (pinfunction "S_22") (pintype "passive"))
      (node (ref "R916") (pin "P$2") (pinfunction "2_P$2") (pintype "passive"))
    )
    (net (code "111") (name "Net-(J901H-S)") (class "Default")
      (node (ref "J901") (pin "25") (pinfunction "S_25") (pintype "passive"))
      (node (ref "R908") (pin "P$2") (pinfunction "2_P$2") (pintype "passive"))
    )
    (net (code "112") (name "Net-(J901I-S)") (class "Default")
      (node (ref "J901") (pin "28") (pinfunction "S_28") (pintype "passive"))
      (node (ref "R917") (pin "P$2") (pinfunction "2_P$2") (pintype "passive"))
    )
    (net (code "113") (name "Net-(J901J-S)") (class "Default")
      (node (ref "J901") (pin "31") (pinfunction "S_31") (pintype "passive"))
      (node (ref "R902") (pin "P$2") (pinfunction "2_P$2") (pintype "passive"))
    )
    (net (code "114") (name "Net-(J901K-S)") (class "Default")
      (node (ref "J901") (pin "34") (pinfunction "S_34") (pintype "passive"))
      (node (ref "R911") (pin "P$2") (pinfunction "2_P$2") (pintype "passive"))
    )
    (net (code "115") (name "Net-(J901L-S)") (class "Default")
      (node (ref "J901") (pin "37") (pinfunction "S_37") (pintype "passive"))
      (node (ref "R903") (pin "P$2") (pinfunction "2_P$2") (pintype "passive"))
    )
    (net (code "116") (name "Net-(J901M-S)") (class "Default")
      (node (ref "J901") (pin "4") (pinfunction "S_4") (pintype "passive"))
      (node (ref "R910") (pin "P$2") (pinfunction "2_P$2") (pintype "passive"))
    )
    (net (code "117") (name "Net-(J901N-S)") (class "Default")
      (node (ref "J901") (pin "40") (pinfunction "S_40") (pintype "passive"))
      (node (ref "R912") (pin "P$2") (pinfunction "2_P$2") (pintype "passive"))
    )
    (net (code "118") (name "Net-(J901O-S)") (class "Default")
      (node (ref "J901") (pin "43") (pinfunction "S_43") (pintype "passive"))
      (node (ref "R904") (pin "P$2") (pinfunction "2_P$2") (pintype "passive"))
    )
    (net (code "119") (name "Net-(J901P-S)") (class "Default")
      (node (ref "J901") (pin "46") (pinfunction "S_46") (pintype "passive"))
      (node (ref "R913") (pin "P$2") (pinfunction "2_P$2") (pintype "passive"))
    )
    (net (code "120") (name "Net-(J901Q-S)") (class "Default")
      (node (ref "J901") (pin "7") (pinfunction "S_7") (pintype "passive"))
      (node (ref "R905") (pin "P$2") (pinfunction "2_P$2") (pintype "passive"))
    )
    (net (code "121") (name "Net-(L701-2)") (class "Default")
      (node (ref "L701") (pin "P$2") (pinfunction "2_P$2") (pintype "passive"))
      (node (ref "U702") (pin "5") (pinfunction "SW_5") (pintype "passive"))
    )
    (net (code "122") (name "Net-(R1-2)") (class "Default")
      (node (ref "R1") (pin "P$2") (pinfunction "2_P$2") (pintype "passive"))
      (node (ref "R2") (pin "P$1") (pinfunction "1_P$1") (pintype "passive"))
      (node (ref "U$2") (pin "P$1") (pinfunction "UV1_P$1") (pintype "bidirectional"))
    )
    (net (code "123") (name "Net-(R2-2)") (class "Default")
      (node (ref "R2") (pin "P$2") (pinfunction "2_P$2") (pintype "passive"))
      (node (ref "R5") (pin "P$1") (pinfunction "1_P$1") (pintype "passive"))
      (node (ref "U$2") (pin "P$2") (pinfunction "OV1_P$2") (pintype "bidirectional"))
    )
    (net (code "124") (name "Net-(R3-1)") (class "Default")
      (node (ref "R3") (pin "P$1") (pinfunction "1_P$1") (pintype "passive"))
      (node (ref "R707") (pin "P$2") (pinfunction "2_P$2") (pintype "passive"))
    )
    (net (code "125") (name "Net-(R3-2)") (class "Default")
      (node (ref "LED701") (pin "C") (pinfunction "C_C") (pintype "passive"))
      (node (ref "R3") (pin "P$2") (pinfunction "2_P$2") (pintype "passive"))
    )
    (net (code "126") (name "Net-(R4-1)") (class "Default")
      (node (ref "R4") (pin "P$1") (pinfunction "1_P$1") (pintype "passive"))
      (node (ref "R709") (pin "P$2") (pinfunction "2_P$2") (pintype "passive"))
    )
    (net (code "127") (name "Net-(R4-2)") (class "Default")
      (node (ref "LED703") (pin "C") (pinfunction "C_C") (pintype "passive"))
      (node (ref "R4") (pin "P$2") (pinfunction "2_P$2") (pintype "passive"))
    )
    (net (code "128") (name "Net-(R6-2)") (class "Default")
      (node (ref "R6") (pin "P$2") (pinfunction "2_P$2") (pintype "passive"))
      (node (ref "R7") (pin "P$1") (pinfunction "1_P$1") (pintype "passive"))
      (node (ref "U$2") (pin "P$5") (pinfunction "UV3_P$5") (pintype "bidirectional"))
    )
    (net (code "129") (name "Net-(R7-2)") (class "Default")
      (node (ref "R7") (pin "P$2") (pinfunction "2_P$2") (pintype "passive"))
      (node (ref "R8") (pin "P$1") (pinfunction "1_P$1") (pintype "passive"))
      (node (ref "U$2") (pin "P$6") (pinfunction "OV3_P$6") (pintype "bidirectional"))
    )
    (net (code "130") (name "Net-(R10-1)") (class "Default")
      (node (ref "R10") (pin "P$1") (pinfunction "1_P$1") (pintype "passive"))
      (node (ref "R9") (pin "P$2") (pinfunction "2_P$2") (pintype "passive"))
      (node (ref "U$2") (pin "P$3") (pinfunction "UV2_P$3") (pintype "bidirectional"))
    )
    (net (code "131") (name "Net-(R10-2)") (class "Default")
      (node (ref "R10") (pin "P$2") (pinfunction "2_P$2") (pintype "passive"))
      (node (ref "R11") (pin "P$1") (pinfunction "1_P$1") (pintype "passive"))
      (node (ref "U$2") (pin "P$4") (pinfunction "OV2_P$4") (pintype "bidirectional"))
    )
    (net (code "132") (name "Net-(R101-1)") (class "Default")
      (node (ref "R101") (pin "P$1") (pinfunction "1_P$1") (pintype "passive"))
      (node (ref "U101") (pin "69") (pinfunction "PA10_69") (pintype "bidirectional"))
    )
    (net (code "133") (name "Net-(R102-1)") (class "Default")
      (node (ref "R102") (pin "P$1") (pinfunction "1_P$1") (pintype "passive"))
      (node (ref "U101") (pin "37") (pinfunction "PB2_37") (pintype "bidirectional"))
    )
    (net (code "134") (name "Net-(R201-1)") (class "Default")
      (node (ref "R201") (pin "P$1") (pinfunction "1_P$1") (pintype "passive"))
      (node (ref "U201") (pin "20") (pinfunction "B1_20") (pintype "bidirectional"))
    )
    (net (code "135") (name "Net-(R202-1)") (class "Default")
      (node (ref "R202") (pin "P$1") (pinfunction "1_P$1") (pintype "passive"))
      (node (ref "U201") (pin "17") (pinfunction "B3_17") (pintype "bidirectional"))
    )
    (net (code "136") (name "Net-(R203-1)") (class "Default")
      (node (ref "R203") (pin "P$1") (pinfunction "1_P$1") (pintype "passive"))
      (node (ref "U201") (pin "15") (pinfunction "B5_15") (pintype "bidirectional"))
    )
    (net (code "137") (name "Net-(R204-1)") (class "Default")
      (node (ref "R204") (pin "P$1") (pinfunction "1_P$1") (pintype "passive"))
      (node (ref "U201") (pin "13") (pinfunction "B7_13") (pintype "bidirectional"))
    )
    (net (code "138") (name "Net-(R205-1)") (class "Default")
      (node (ref "R205") (pin "P$1") (pinfunction "1_P$1") (pintype "passive"))
      (node (ref "U202") (pin "17") (pinfunction "B3_17") (pintype "bidirectional"))
    )
    (net (code "139") (name "Net-(R206-1)") (class "Default")
      (node (ref "R206") (pin "P$1") (pinfunction "1_P$1") (pintype "passive"))
      (node (ref "U202") (pin "15") (pinfunction "B5_15") (pintype "bidirectional"))
    )
    (net (code "140") (name "Net-(R207-1)") (class "Default")
      (node (ref "R207") (pin "P$1") (pinfunction "1_P$1") (pintype "passive"))
      (node (ref "U202") (pin "13") (pinfunction "B7_13") (pintype "bidirectional"))
    )
    (net (code "141") (name "Net-(R208-1)") (class "Default")
      (node (ref "R208") (pin "P$1") (pinfunction "1_P$1") (pintype "passive"))
      (node (ref "U201") (pin "18") (pinfunction "B2_18") (pintype "bidirectional"))
    )
    (net (code "142") (name "Net-(R209-1)") (class "Default")
      (node (ref "R209") (pin "P$1") (pinfunction "1_P$1") (pintype "passive"))
      (node (ref "U201") (pin "16") (pinfunction "B4_16") (pintype "bidirectional"))
    )
    (net (code "143") (name "Net-(R210-1)") (class "Default")
      (node (ref "R210") (pin "P$1") (pinfunction "1_P$1") (pintype "passive"))
      (node (ref "U201") (pin "14") (pinfunction "B6_14") (pintype "bidirectional"))
    )
    (net (code "144") (name "Net-(R211-1)") (class "Default")
      (node (ref "R211") (pin "P$1") (pinfunction "1_P$1") (pintype "passive"))
      (node (ref "U201") (pin "12") (pinfunction "B8_12") (pintype "bidirectional"))
    )
    (net (code "145") (name "Net-(R212-1)") (class "Default")
      (node (ref "R212") (pin "P$1") (pinfunction "1_P$1") (pintype "passive"))
      (node (ref "U202") (pin "16") (pinfunction "B4_16") (pintype "bidirectional"))
    )
    (net (code "146") (name "Net-(R213-1)") (class "Default")
      (node (ref "R213") (pin "P$1") (pinfunction "1_P$1") (pintype "passive"))
      (node (ref "U202") (pin "14") (pinfunction "B6_14") (pintype "bidirectional"))
    )
    (net (code "147") (name "Net-(R214-1)") (class "Default")
      (node (ref "R214") (pin "P$1") (pinfunction "1_P$1") (pintype "passive"))
      (node (ref "U202") (pin "12") (pinfunction "B8_12") (pintype "bidirectional"))
    )
    (net (code "148") (name "Net-(R602-1)") (class "Default")
      (node (ref "R602") (pin "P$1") (pinfunction "1_P$1") (pintype "passive"))
      (node (ref "U$602") (pin "7") (pinfunction "ILIM_7") (pintype "bidirectional"))
    )
    (net (code "149") (name "Net-(R604-2)") (class "Default")
      (node (ref "L601") (pin "P$2") (pinfunction "P$2_P$2") (pintype "bidirectional"))
      (node (ref "R604") (pin "P$2") (pinfunction "2_P$2") (pintype "passive"))
    )
    (net (code "150") (name "Net-(R605-2)") (class "Default")
      (node (ref "L602") (pin "P$2") (pinfunction "P$2_P$2") (pintype "bidirectional"))
      (node (ref "R605") (pin "P$2") (pinfunction "2_P$2") (pintype "passive"))
    )
    (net (code "151") (name "Net-(R606-1)") (class "Default")
      (node (ref "R606") (pin "P$1") (pinfunction "1_P$1") (pintype "passive"))
      (node (ref "U$604") (pin "7") (pinfunction "ILIM_7") (pintype "bidirectional"))
    )
    (net (code "152") (name "Net-(R701-1)") (class "Default")
      (node (ref "R701") (pin "P$1") (pinfunction "1_P$1") (pintype "passive"))
      (node (ref "U702") (pin "7") (pinfunction "+IN_7") (pintype "input"))
    )
    (net (code "153") (name "Net-(R702-1)") (class "Default")
      (node (ref "R702") (pin "P$1") (pinfunction "1_P$1") (pintype "passive"))
      (node (ref "R703") (pin "P$2") (pinfunction "2_P$2") (pintype "passive"))
      (node (ref "U702") (pin "8") (pinfunction "-IN_8") (pintype "input"))
    )
    (net (code "154") (name "Net-(R704-2)") (class "Default")
      (node (ref "R704") (pin "P$2") (pinfunction "2_P$2") (pintype "passive"))
      (node (ref "U701") (pin "6") (pinfunction "REXT_6") (pintype "bidirectional"))
    )
    (net (code "155") (name "Net-(R705-2)") (class "Default")
      (node (ref "R705") (pin "P$2") (pinfunction "2_P$2") (pintype "passive"))
      (node (ref "R706") (pin "P$1") (pinfunction "1_P$1") (pintype "passive"))
      (node (ref "U702") (pin "2") (pinfunction "FB_2") (pintype "bidirectional"))
    )
    (net (code "156") (name "Net-(R708-2)") (class "Default")
      (node (ref "LED702") (pin "C") (pinfunction "C_C") (pintype "passive"))
      (node (ref "R708") (pin "P$2") (pinfunction "2_P$2") (pintype "passive"))
    )
    (net (code "157") (name "Net-(R711-2)") (class "Default")
      (node (ref "LED704") (pin "C") (pinfunction "C_C") (pintype "passive"))
      (node (ref "R711") (pin "P$2") (pinfunction "2_P$2") (pintype "passive"))
    )
    (net (code "158") (name "Net-(R712-2)") (class "Default")
      (node (ref "LED705") (pin "C") (pinfunction "C_C") (pintype "passive"))
      (node (ref "R712") (pin "P$2") (pinfunction "2_P$2") (pintype "passive"))
    )
    (net (code "159") (name "Net-(R802-1)") (class "Default")
      (node (ref "R802") (pin "P$1") (pinfunction "1_P$1") (pintype "passive"))
      (node (ref "U801") (pin "20") (pinfunction "PB2_20") (pintype "bidirectional"))
    )
    (net (code "160") (name "Net-(R803-1)") (class "Default")
      (node (ref "R803") (pin "P$1") (pinfunction "1_P$1") (pintype "passive"))
      (node (ref "U801") (pin "12") (pinfunction "PA2_12") (pintype "bidirectional"))
    )
    (net (code "161") (name "Net-(R804-1)") (class "Default")
      (node (ref "R804") (pin "P$1") (pinfunction "1_P$1") (pintype "passive"))
      (node (ref "U801") (pin "13") (pinfunction "PA3_13") (pintype "bidirectional"))
    )
    (net (code "162") (name "Net-(R901-2)") (class "Default")
      (node (ref "R901") (pin "P$2") (pinfunction "2_P$2") (pintype "passive"))
      (node (ref "R910") (pin "P$1") (pinfunction "1_P$1") (pintype "passive"))
      (node (ref "U$902") (pin "C") (pinfunction "C_C") (pintype "passive"))
      (node (ref "U903") (pin "3") (pinfunction "2Y_3") (pintype "bidirectional"))
    )
    (net (code "163") (name "Net-(R902-1)") (class "Default")
      (node (ref "R902") (pin "P$1") (pinfunction "1_P$1") (pintype "passive"))
      (node (ref "U901") (pin "20") (pinfunction "B1_20") (pintype "bidirectional"))
    )
    (net (code "164") (name "Net-(R903-1)") (class "Default")
      (node (ref "R903") (pin "P$1") (pinfunction "1_P$1") (pintype "passive"))
      (node (ref "U901") (pin "17") (pinfunction "B3_17") (pintype "bidirectional"))
    )
    (net (code "165") (name "Net-(R904-1)") (class "Default")
      (node (ref "R904") (pin "P$1") (pinfunction "1_P$1") (pintype "passive"))
      (node (ref "U901") (pin "15") (pinfunction "B5_15") (pintype "bidirectional"))
    )
    (net (code "166") (name "Net-(R905-1)") (class "Default")
      (node (ref "R905") (pin "P$1") (pinfunction "1_P$1") (pintype "passive"))
      (node (ref "U902") (pin "20") (pinfunction "B1_20") (pintype "bidirectional"))
    )
    (net (code "167") (name "Net-(R906-1)") (class "Default")
      (node (ref "R906") (pin "P$1") (pinfunction "1_P$1") (pintype "passive"))
      (node (ref "U902") (pin "17") (pinfunction "B3_17") (pintype "bidirectional"))
    )
    (net (code "168") (name "Net-(R907-1)") (class "Default")
      (node (ref "R907") (pin "P$1") (pinfunction "1_P$1") (pintype "passive"))
      (node (ref "U902") (pin "15") (pinfunction "B5_15") (pintype "bidirectional"))
    )
    (net (code "169") (name "Net-(R908-1)") (class "Default")
      (node (ref "R908") (pin "P$1") (pinfunction "1_P$1") (pintype "passive"))
      (node (ref "U902") (pin "13") (pinfunction "B7_13") (pintype "bidirectional"))
    )
    (net (code "170") (name "Net-(R911-1)") (class "Default")
      (node (ref "R911") (pin "P$1") (pinfunction "1_P$1") (pintype "passive"))
      (node (ref "U901") (pin "18") (pinfunction "B2_18") (pintype "bidirectional"))
    )
    (net (code "171") (name "Net-(R912-1)") (class "Default")
      (node (ref "R912") (pin "P$1") (pinfunction "1_P$1") (pintype "passive"))
      (node (ref "U901") (pin "16") (pinfunction "B4_16") (pintype "bidirectional"))
    )
    (net (code "172") (name "Net-(R913-1)") (class "Default")
      (node (ref "R913") (pin "P$1") (pinfunction "1_P$1") (pintype "passive"))
      (node (ref "U901") (pin "14") (pinfunction "B6_14") (pintype "bidirectional"))
    )
    (net (code "173") (name "Net-(R914-1)") (class "Default")
      (node (ref "R914") (pin "P$1") (pinfunction "1_P$1") (pintype "passive"))
      (node (ref "U902") (pin "18") (pinfunction "B2_18") (pintype "bidirectional"))
    )
    (net (code "174") (name "Net-(R915-1)") (class "Default")
      (node (ref "R915") (pin "P$1") (pinfunction "1_P$1") (pintype "passive"))
      (node (ref "U902") (pin "16") (pinfunction "B4_16") (pintype "bidirectional"))
    )
    (net (code "175") (name "Net-(R916-1)") (class "Default")
      (node (ref "R916") (pin "P$1") (pinfunction "1_P$1") (pintype "passive"))
      (node (ref "U902") (pin "14") (pinfunction "B6_14") (pintype "bidirectional"))
    )
    (net (code "176") (name "Net-(R917-1)") (class "Default")
      (node (ref "R917") (pin "P$1") (pinfunction "1_P$1") (pintype "passive"))
      (node (ref "U902") (pin "12") (pinfunction "B8_12") (pintype "bidirectional"))
    )
    (net (code "177") (name "Net-(R918-2)") (class "Default")
      (node (ref "R918") (pin "P$2") (pinfunction "2_P$2") (pintype "passive"))
      (node (ref "R922") (pin "P$1") (pinfunction "1_P$1") (pintype "passive"))
    )
    (net (code "178") (name "Net-(R1001-2)") (class "Default")
      (node (ref "R1001") (pin "P$2") (pinfunction "2_P$2") (pintype "passive"))
      (node (ref "U$1001") (pin "7") (pinfunction "ILIM_7") (pintype "bidirectional"))
    )
    (net (code "179") (name "Net-(U$2-G1)") (class "Default")
      (node (ref "U$2") (pin "P$17") (pinfunction "G1_P$17") (pintype "bidirectional"))
      (node (ref "U$3") (pin "P$2") (pinfunction "G_P$2") (pintype "passive"))
      (node (ref "U$3") (pin "P$4") (pinfunction "G_P$4") (pintype "passive"))
    )
    (net (code "180") (name "Net-(U$2-G2)") (class "Default")
      (node (ref "U$2") (pin "P$15") (pinfunction "G2_P$15") (pintype "bidirectional"))
      (node (ref "U$4") (pin "P$2") (pinfunction "G_P$2") (pintype "passive"))
      (node (ref "U$4") (pin "P$4") (pinfunction "G_P$4") (pintype "passive"))
    )
    (net (code "181") (name "Net-(U$2-G3)") (class "Default")
      (node (ref "U$2") (pin "P$13") (pinfunction "G3_P$13") (pintype "bidirectional"))
      (node (ref "U$5") (pin "P$2") (pinfunction "G_P$2") (pintype "passive"))
      (node (ref "U$5") (pin "P$4") (pinfunction "G_P$4") (pintype "passive"))
    )
    (net (code "182") (name "Net-(U$2-VS1)") (class "Default")
      (node (ref "U$2") (pin "P$18") (pinfunction "VS1_P$18") (pintype "bidirectional"))
      (node (ref "U$3") (pin "P$1") (pinfunction "S_P$1") (pintype "passive"))
      (node (ref "U$3") (pin "P$3") (pinfunction "S_P$3") (pintype "passive"))
    )
    (net (code "183") (name "Net-(U$2-VS2)") (class "Default")
      (node (ref "U$2") (pin "P$16") (pinfunction "VS2_P$16") (pintype "bidirectional"))
      (node (ref "U$4") (pin "P$1") (pinfunction "S_P$1") (pintype "passive"))
      (node (ref "U$4") (pin "P$3") (pinfunction "S_P$3") (pintype "passive"))
    )
    (net (code "184") (name "Net-(U$2-VS3)") (class "Default")
      (node (ref "U$2") (pin "P$14") (pinfunction "VS3_P$14") (pintype "bidirectional"))
      (node (ref "U$5") (pin "P$1") (pinfunction "S_P$1") (pintype "passive"))
      (node (ref "U$5") (pin "P$3") (pinfunction "S_P$3") (pintype "passive"))
    )
    (net (code "185") (name "Net-(U701-OUT0)") (class "Default")
      (node (ref "U701") (pin "9") (pinfunction "OUT0_9") (pintype "open_collector"))
      (node (ref "U703") (pin "C1") (pinfunction "C_C1") (pintype "passive"))
    )
    (net (code "186") (name "Net-(U701-OUT1)") (class "Default")
      (node (ref "U701") (pin "8") (pinfunction "OUT1_8") (pintype "open_collector"))
      (node (ref "U703") (pin "C2") (pinfunction "C_C2") (pintype "passive"))
    )
    (net (code "187") (name "Net-(U701-OUT2)") (class "Default")
      (node (ref "U701") (pin "7") (pinfunction "OUT2_7") (pintype "open_collector"))
      (node (ref "U703") (pin "C3") (pinfunction "C_C3") (pintype "passive"))
    )
    (net (code "188") (name "OTG_FS_DM") (class "Default")
      (node (ref "U$301") (pin "6") (pinfunction "D1O_6") (pintype "bidirectional"))
      (node (ref "U101") (pin "70") (pinfunction "PA11_70") (pintype "bidirectional"))
    )
    (net (code "189") (name "OTG_FS_DP") (class "Default")
      (node (ref "U$301") (pin "4") (pinfunction "D2O_4") (pintype "bidirectional"))
      (node (ref "U101") (pin "71") (pinfunction "PA12_71") (pintype "bidirectional"))
    )
    (net (code "190") (name "PPM_INPUT") (class "Default")
      (node (ref "R909") (pin "P$1") (pinfunction "1_P$1") (pintype "passive"))
      (node (ref "U$901") (pin "C") (pinfunction "C_C") (pintype "passive"))
      (node (ref "U801") (pin "29") (pinfunction "PA8_29") (pintype "bidirectional"))
      (node (ref "U903") (pin "2") (pinfunction "1A_2") (pintype "bidirectional"))
    )
    (net (code "191") (name "PRESSURE_SENS") (class "Default")
      (node (ref "C401") (pin "P$1") (pinfunction "1_P$1") (pintype "passive"))
      (node (ref "R403") (pin "P$2") (pinfunction "2_P$2") (pintype "passive"))
      (node (ref "R406") (pin "P$1") (pinfunction "1_P$1") (pintype "passive"))
      (node (ref "U101") (pin "34") (pinfunction "PC5_34") (pintype "bidirectional"))
    )
    (net (code "192") (name "PRESSURE_SENS_IN") (class "Default")
      (node (ref "ADC_PR") (pin "P$1") (pinfunction "P$1_P$1") (pintype "passive"))
      (node (ref "J402") (pin "P$2") (pinfunction "2_P$2") (pintype "passive"))
      (node (ref "R406") (pin "P$2") (pinfunction "2_P$2") (pintype "passive"))
    )
    (net (code "193") (name "RSSI_IN") (class "Default")
      (node (ref "R901") (pin "P$1") (pinfunction "1_P$1") (pintype "passive"))
      (node (ref "U801") (pin "15") (pinfunction "PA5_15") (pintype "bidirectional"))
      (node (ref "U801") (pin "33") (pinfunction "PA12_33") (pintype "bidirectional"))
    )
    (net (code "194") (name "SAFETY") (class "Default")
      (node (ref "J702") (pin "P$3") (pinfunction "3_P$3") (pintype "passive"))
      (node (ref "R713") (pin "P$1") (pinfunction "1_P$1") (pintype "passive"))
      (node (ref "U801") (pin "41") (pinfunction "PB5_41") (pintype "bidirectional"))
    )
    (net (code "195") (name "SBUS_INPUT") (class "Default")
      (node (ref "U801") (pin "22") (pinfunction "PB11_22") (pintype "bidirectional"))
      (node (ref "U903") (pin "6") (pinfunction "1Y_6") (pintype "bidirectional"))
    )
    (net (code "196") (name "SBUS_OUTPUT") (class "Default")
      (node (ref "U801") (pin "21") (pinfunction "PB10_21") (pintype "bidirectional"))
      (node (ref "U903") (pin "5") (pinfunction "2A_5") (pintype "bidirectional"))
    )
    (net (code "197") (name "SDIO_CK") (class "Default")
      (node (ref "U101") (pin "80") (pinfunction "PC12_80") (pintype "bidirectional"))
      (node (ref "U301") (pin "5") (pinfunction "CLK_5") (pintype "bidirectional"))
    )
    (net (code "198") (name "SDIO_CMD") (class "Default")
      (node (ref "R303") (pin "P$1") (pinfunction "1_P$1") (pintype "passive"))
      (node (ref "U101") (pin "83") (pinfunction "PD2_83") (pintype "bidirectional"))
      (node (ref "U301") (pin "3") (pinfunction "CMD_3") (pintype "bidirectional"))
    )
    (net (code "199") (name "SDIO_D0") (class "Default")
      (node (ref "R304") (pin "P$1") (pinfunction "1_P$1") (pintype "passive"))
      (node (ref "U101") (pin "65") (pinfunction "PC8_65") (pintype "bidirectional"))
      (node (ref "U301") (pin "7") (pinfunction "D0_7") (pintype "bidirectional"))
    )
    (net (code "200") (name "SDIO_D1") (class "Default")
      (node (ref "R305") (pin "P$1") (pinfunction "1_P$1") (pintype "passive"))
      (node (ref "U101") (pin "66") (pinfunction "PC9_66") (pintype "bidirectional"))
      (node (ref "U301") (pin "8") (pinfunction "D1_8") (pintype "bidirectional"))
    )
    (net (code "201") (name "SDIO_D2") (class "Default")
      (node (ref "R301") (pin "P$1") (pinfunction "1_P$1") (pintype "passive"))
      (node (ref "U101") (pin "78") (pinfunction "PC10_78") (pintype "bidirectional"))
      (node (ref "U301") (pin "1") (pinfunction "D2_1") (pintype "bidirectional"))
    )
    (net (code "202") (name "SDIO_D3") (class "Default")
      (node (ref "R302") (pin "P$1") (pinfunction "1_P$1") (pintype "passive"))
      (node (ref "U101") (pin "79") (pinfunction "PC11_79") (pintype "bidirectional"))
      (node (ref "U301") (pin "2") (pinfunction "D3_2") (pintype "bidirectional"))
    )
    (net (code "203") (name "SERIAL1_CTS") (class "Default")
      (node (ref "J201") (pin "P$4") (pinfunction "4_P$4") (pintype "passive"))
      (node (ref "R211") (pin "P$2") (pinfunction "2_P$2") (pintype "passive"))
    )
    (net (code "204") (name "SERIAL1_RTS") (class "Default")
      (node (ref "J201") (pin "P$5") (pinfunction "5_P$5") (pintype "passive"))
      (node (ref "R204") (pin "P$2") (pinfunction "2_P$2") (pintype "passive"))
    )
    (net (code "205") (name "SERIAL1_RX") (class "Default")
      (node (ref "J201") (pin "P$3") (pinfunction "3_P$3") (pintype "passive"))
      (node (ref "R203") (pin "P$2") (pinfunction "2_P$2") (pintype "passive"))
      (node (ref "S1RX") (pin "P$1") (pinfunction "P$1_P$1") (pintype "passive"))
    )
    (net (code "206") (name "SERIAL1_TX") (class "Default")
      (node (ref "J201") (pin "P$2") (pinfunction "2_P$2") (pintype "passive"))
      (node (ref "R210") (pin "P$2") (pinfunction "2_P$2") (pintype "passive"))
      (node (ref "S1TX") (pin "P$1") (pinfunction "P$1_P$1") (pintype "passive"))
    )
    (net (code "207") (name "SERIAL2_CTS") (class "Default")
      (node (ref "J202") (pin "P$4") (pinfunction "4_P$4") (pintype "passive"))
      (node (ref "R208") (pin "P$2") (pinfunction "2_P$2") (pintype "passive"))
    )
    (net (code "208") (name "SERIAL2_RTS") (class "Default")
      (node (ref "J202") (pin "P$5") (pinfunction "5_P$5") (pintype "passive"))
      (node (ref "R201") (pin "P$2") (pinfunction "2_P$2") (pintype "passive"))
    )
    (net (code "209") (name "SERIAL2_RX") (class "Default")
      (node (ref "J202") (pin "P$3") (pinfunction "3_P$3") (pintype "passive"))
      (node (ref "R202") (pin "P$2") (pinfunction "2_P$2") (pintype "passive"))
      (node (ref "S2RX") (pin "P$1") (pinfunction "P$1_P$1") (pintype "passive"))
    )
    (net (code "210") (name "SERIAL2_TX") (class "Default")
      (node (ref "J202") (pin "P$2") (pinfunction "2_P$2") (pintype "passive"))
      (node (ref "R209") (pin "P$2") (pinfunction "2_P$2") (pintype "passive"))
      (node (ref "S2TX") (pin "P$1") (pinfunction "P$1_P$1") (pintype "passive"))
    )
    (net (code "211") (name "SERIAL3_RX") (class "Default")
      (node (ref "J203") (pin "P$3") (pinfunction "3_P$3") (pintype "passive"))
      (node (ref "R207") (pin "P$2") (pinfunction "2_P$2") (pintype "passive"))
      (node (ref "S3RX") (pin "P$1") (pinfunction "P$1_P$1") (pintype "passive"))
    )
    (net (code "212") (name "SERIAL3_TX") (class "Default")
      (node (ref "J203") (pin "P$2") (pinfunction "2_P$2") (pintype "passive"))
      (node (ref "R214") (pin "P$2") (pinfunction "2_P$2") (pintype "passive"))
      (node (ref "S3TX") (pin "P$1") (pinfunction "P$1_P$1") (pintype "passive"))
    )
    (net (code "213") (name "SERIAL4_RX") (class "Default")
      (node (ref "J204") (pin "P$3") (pinfunction "3_P$3") (pintype "passive"))
      (node (ref "R206") (pin "P$2") (pinfunction "2_P$2") (pintype "passive"))
      (node (ref "S4RX") (pin "P$1") (pinfunction "P$1_P$1") (pintype "passive"))
    )
    (net (code "214") (name "SERIAL4_TX") (class "Default")
      (node (ref "J204") (pin "P$2") (pinfunction "2_P$2") (pintype "passive"))
      (node (ref "R213") (pin "P$2") (pinfunction "2_P$2") (pintype "passive"))
      (node (ref "S4TX") (pin "P$1") (pinfunction "P$1_P$1") (pintype "passive"))
    )
    (net (code "215") (name "SERIAL5_RX") (class "Default")
      (node (ref "J204") (pin "P$5") (pinfunction "5_P$5") (pintype "passive"))
      (node (ref "R205") (pin "P$2") (pinfunction "2_P$2") (pintype "passive"))
      (node (ref "S5_RX") (pin "P$1") (pinfunction "P$1_P$1") (pintype "passive"))
    )
    (net (code "216") (name "SERIAL5_TX") (class "Default")
      (node (ref "J204") (pin "P$4") (pinfunction "4_P$4") (pintype "passive"))
      (node (ref "R212") (pin "P$2") (pinfunction "2_P$2") (pintype "passive"))
      (node (ref "S5_TX") (pin "P$1") (pinfunction "P$1_P$1") (pintype "passive"))
    )
    (net (code "217") (name "SERIAL_FMU_TO_IO") (class "Default")
      (node (ref "R804") (pin "P$2") (pinfunction "2_P$2") (pintype "passive"))
      (node (ref "U101") (pin "63") (pinfunction "PC6_63") (pintype "bidirectional"))
    )
    (net (code "218") (name "SERIAL_IO_TO_FMU") (class "Default")
      (node (ref "R803") (pin "P$2") (pinfunction "2_P$2") (pintype "passive"))
      (node (ref "U101") (pin "64") (pinfunction "PC7_64") (pintype "bidirectional"))
    )
    (net (code "219") (name "SPI_EXT_MISO") (class "Default")
      (node (ref "J403") (pin "P$3") (pinfunction "3_P$3") (pintype "passive"))
      (node (ref "U101") (pin "4") (pinfunction "PE5_4") (pintype "bidirectional"))
    )
    (net (code "220") (name "SPI_EXT_MOSI") (class "Default")
      (node (ref "J403") (pin "P$4") (pinfunction "4_P$4") (pintype "passive"))
      (node (ref "U101") (pin "5") (pinfunction "PE6_5") (pintype "bidirectional"))
    )
    (net (code "221") (name "SPI_EXT_SCK") (class "Default")
      (node (ref "J403") (pin "P$2") (pinfunction "2_P$2") (pintype "passive"))
      (node (ref "U101") (pin "1") (pinfunction "PE2_1") (pintype "bidirectional"))
    )
    (net (code "222") (name "SPI_INT_MISO") (class "Default")
      (node (ref "U$1") (pin "9") (pinfunction "S_9") (pintype "passive"))
      (node (ref "U$501") (pin "7") (pinfunction "SDO/SA0_7") (pintype "bidirectional"))
      (node (ref "U101") (pin "31") (pinfunction "PA6_31") (pintype "bidirectional"))
      (node (ref "U501") (pin "4") (pinfunction "SDO/SA0_4") (pintype "bidirectional"))
      (node (ref "U502") (pin "4") (pinfunction "SDO/SA0_4") (pintype "bidirectional"))
      (node (ref "U503") (pin "6") (pinfunction "SDO_6") (pintype "bidirectional"))
    )
    (net (code "223") (name "SPI_INT_MOSI") (class "Default")
      (node (ref "U$1") (pin "8") (pinfunction "S_8") (pintype "passive"))
      (node (ref "U$501") (pin "6") (pinfunction "SDA/SDI/SDO_6") (pintype "bidirectional"))
      (node (ref "U101") (pin "32") (pinfunction "PA7_32") (pintype "bidirectional"))
      (node (ref "U501") (pin "3") (pinfunction "SDA/SDI/SDO_3") (pintype "bidirectional"))
      (node (ref "U502") (pin "3") (pinfunction "SDA/SDI/SDO_3") (pintype "bidirectional"))
      (node (ref "U503") (pin "7") (pinfunction "SDI/SDA_7") (pintype "bidirectional"))
    )
    (net (code "224") (name "SPI_INT_SCK") (class "Default")
      (node (ref "U$1") (pin "10") (pinfunction "S_10") (pintype "passive"))
      (node (ref "U$501") (pin "4") (pinfunction "SCL/SPC_4") (pintype "bidirectional"))
      (node (ref "U101") (pin "30") (pinfunction "PA5_30") (pintype "bidirectional"))
      (node (ref "U501") (pin "2") (pinfunction "SCL/SPC_2") (pintype "input"))
      (node (ref "U502") (pin "2") (pinfunction "SCL/SPC_2") (pintype "bidirectional"))
      (node (ref "U503") (pin "8") (pinfunction "SCLK_8") (pintype "bidirectional"))
    )
    (net (code "225") (name "VBAT") (class "Default")
      (node (ref "B601") (pin "1") (pinfunction "POS_1") (pintype "bidirectional"))
      (node (ref "R608") (pin "P$1") (pinfunction "1_P$1") (pintype "passive"))
      (node (ref "U101") (pin "6") (pinfunction "VBAT_6") (pintype "power_in"))
      (node (ref "U801") (pin "1") (pinfunction "VBAT_1") (pintype "power_in"))
    )
    (net (code "226") (name "VBUS") (class "Default")
      (node (ref "J301") (pin "VBUS") (pinfunction "1_VBUS") (pintype "power_in"))
      (node (ref "J302") (pin "P$1") (pinfunction "1_P$1") (pintype "passive"))
      (node (ref "R6") (pin "P$1") (pinfunction "1_P$1") (pintype "passive"))
      (node (ref "U$2") (pin "P$19") (pinfunction "V3_P$19") (pintype "bidirectional"))
      (node (ref "U$301") (pin "5") (pinfunction "VBUS_5") (pintype "bidirectional"))
      (node (ref "U$5") (pin "P$7") (pinfunction "D_P$7") (pintype "passive"))
      (node (ref "U$5") (pin "P$8") (pinfunction "D_P$8") (pintype "passive"))
      (node (ref "U101") (pin "68") (pinfunction "PA9_68") (pintype "bidirectional"))
    )
    (net (code "227") (name "VDD_3V3_SENSORS") (class "Default")
      (node (ref "C501") (pin "P$1") (pinfunction "1_P$1") (pintype "passive"))
      (node (ref "C502") (pin "P$1") (pinfunction "1_P$1") (pintype "passive"))
      (node (ref "C503") (pin "P$1") (pinfunction "1_P$1") (pintype "passive"))
      (node (ref "C506") (pin "P$1") (pinfunction "1_P$1") (pintype "passive"))
      (node (ref "C507") (pin "P$1") (pinfunction "1_P$1") (pintype "passive"))
      (node (ref "C508") (pin "P$1") (pinfunction "1_P$1") (pintype "passive"))
      (node (ref "C605") (pin "P$1") (pinfunction "1_P$1") (pintype "passive"))
      (node (ref "U$1") (pin "1") (pinfunction "S_1") (pintype "passive"))
      (node (ref "U$501") (pin "1") (pinfunction "VDD_IO_1") (pintype "bidirectional"))
      (node (ref "U$501") (pin "14") (pinfunction "VDD_14") (pintype "bidirectional"))
      (node (ref "U$605") (pin "8") (pinfunction "VOUT1_8") (pintype "bidirectional"))
      (node (ref "U501") (pin "1") (pinfunction "VDD_IO_1") (pintype "bidirectional"))
      (node (ref "U501") (pin "15") (pinfunction "RES_P15_VDD_15") (pintype "bidirectional"))
      (node (ref "U501") (pin "16") (pinfunction "VDD_16") (pintype "bidirectional"))
      (node (ref "U502") (pin "1") (pinfunction "VDD_IO_1") (pintype "bidirectional"))
      (node (ref "U502") (pin "15") (pinfunction "VDD_15") (pintype "bidirectional"))
      (node (ref "U502") (pin "16") (pinfunction "VDD_16") (pintype "bidirectional"))
      (node (ref "U503") (pin "1") (pinfunction "VDD_1") (pintype "bidirectional"))
      (node (ref "VDDA_3V1101") (pin "P$1") (pinfunction "P$1_P$1") (pintype "passive"))
    )
    (net (code "228") (name "VDD_3V3_SENSORS_EN") (class "Default")
      (node (ref "R603") (pin "P$1") (pinfunction "1_P$1") (pintype "passive"))
      (node (ref "U$605") (pin "5") (pinfunction "EN1_5") (pintype "bidirectional"))
      (node (ref "U101") (pin "2") (pinfunction "PE3_2") (pintype "bidirectional"))
    )
    (net (code "229") (name "VDD_3V3_SPEKTRUM") (class "Default")
      (node (ref "C1003") (pin "P$1") (pinfunction "1_P$1") (pintype "passive"))
      (node (ref "J801") (pin "P$1") (pinfunction "P$1_P$1") (pintype "bidirectional"))
      (node (ref "U$1002") (pin "8") (pinfunction "VOUT1_8") (pintype "bidirectional"))
      (node (ref "U$801") (pin "C") (pinfunction "C_C") (pintype "passive"))
    )
    (net (code "230") (name "VDD_3V3_SPEKTRUM_EN") (class "Default")
      (node (ref "R1002") (pin "P$2") (pinfunction "2_P$2") (pintype "passive"))
      (node (ref "U$1002") (pin "5") (pinfunction "EN1_5") (pintype "bidirectional"))
      (node (ref "U801") (pin "2") (pinfunction "PC13_2") (pintype "bidirectional"))
    )
    (net (code "231") (name "VDD_5V_BRICK") (class "Default")
      (node (ref "J601") (pin "P$1") (pinfunction "1_P$1") (pintype "passive"))
      (node (ref "J601") (pin "P$2") (pinfunction "2_P$2") (pintype "passive"))
      (node (ref "R1") (pin "P$1") (pinfunction "1_P$1") (pintype "passive"))
      (node (ref "U$2") (pin "P$21") (pinfunction "V1_P$21") (pintype "bidirectional"))
      (node (ref "U$3") (pin "P$7") (pinfunction "D_P$7") (pintype "passive"))
      (node (ref "U$3") (pin "P$8") (pinfunction "D_P$8") (pintype "passive"))
      (node (ref "VDD_5V_BRICK") (pin "P$1") (pinfunction "P$1_P$1") (pintype "passive"))
    )
    (net (code "232") (name "VDD_5V_HIPOWER") (class "Default")
      (node (ref "L201") (pin "P$1") (pinfunction "P$1_P$1") (pintype "bidirectional"))
      (node (ref "U$602") (pin "8") (pinfunction "OUT_8") (pintype "bidirectional"))
    )
    (net (code "233") (name "VDD_5V_IN") (class "Default")
      (node (ref "C702") (pin "P$1") (pinfunction "1_P$1") (pintype "passive"))
      (node (ref "F2") (pin "1") (pinfunction "1_1") (pintype "bidirectional"))
      (node (ref "L603") (pin "P$1") (pinfunction "P$1_P$1") (pintype "bidirectional"))
      (node (ref "L701") (pin "P$1") (pinfunction "1_P$1") (pintype "passive"))
      (node (ref "LED701") (pin "A") (pinfunction "A_A") (pintype "passive"))
      (node (ref "LED704") (pin "A") (pinfunction "A_A") (pintype "passive"))
      (node (ref "R609") (pin "P$2") (pinfunction "2_P$2") (pintype "passive"))
      (node (ref "U$2") (pin "P$12") (pinfunction "VOUT_P$12") (pintype "bidirectional"))
      (node (ref "U$3") (pin "P$5") (pinfunction "D_P$5") (pintype "passive"))
      (node (ref "U$3") (pin "P$6") (pinfunction "D_P$6") (pintype "passive"))
      (node (ref "U$4") (pin "P$5") (pinfunction "D_P$5") (pintype "passive"))
      (node (ref "U$4") (pin "P$6") (pinfunction "D_P$6") (pintype "passive"))
      (node (ref "U$5") (pin "P$5") (pinfunction "D_P$5") (pintype "passive"))
      (node (ref "U$5") (pin "P$6") (pinfunction "D_P$6") (pintype "passive"))
      (node (ref "U$602") (pin "1") (pinfunction "IN_1") (pintype "bidirectional"))
      (node (ref "U$604") (pin "1") (pinfunction "IN_1") (pintype "bidirectional"))
      (node (ref "U702") (pin "3") (pinfunction "VIN_3") (pintype "power_in"))
      (node (ref "U703") (pin "A1") (pinfunction "A_A1") (pintype "passive"))
      (node (ref "U703") (pin "A2") (pinfunction "A_A2") (pintype "passive"))
      (node (ref "U703") (pin "A3") (pinfunction "A_A3") (pintype "passive"))
    )
    (net (code "234") (name "VDD_5V_PERIPH") (class "Default")
      (node (ref "L202") (pin "P$1") (pinfunction "P$1_P$1") (pintype "bidirectional"))
      (node (ref "L203") (pin "P$1") (pinfunction "P$1_P$1") (pintype "bidirectional"))
      (node (ref "L401") (pin "P$1") (pinfunction "P$1_P$1") (pintype "bidirectional"))
      (node (ref "L402") (pin "P$1") (pinfunction "P$1_P$1") (pintype "bidirectional"))
      (node (ref "L403") (pin "P$1") (pinfunction "P$1_P$1") (pintype "bidirectional"))
      (node (ref "L404") (pin "P$1") (pinfunction "P$1_P$1") (pintype "bidirectional"))
      (node (ref "U$604") (pin "8") (pinfunction "OUT_8") (pintype "bidirectional"))
    )
    (net (code "235") (name "VDD_5V_SENS") (class "Default")
      (node (ref "R609") (pin "P$1") (pinfunction "1_P$1") (pintype "passive"))
      (node (ref "R610") (pin "P$1") (pinfunction "1_P$1") (pintype "passive"))
      (node (ref "U101") (pin "29") (pinfunction "PA4_29") (pintype "bidirectional"))
    )
    (net (code "236") (name "VDD_SERVO") (class "Default")
      (node (ref "D1") (pin "ANODE") (pinfunction "A_ANODE") (pintype "passive"))
      (node (ref "J901") (pin "11") (pinfunction "S_11") (pintype "passive"))
      (node (ref "J901") (pin "14") (pinfunction "S_14") (pintype "passive"))
      (node (ref "J901") (pin "17") (pinfunction "S_17") (pintype "passive"))
      (node (ref "J901") (pin "20") (pinfunction "S_20") (pintype "passive"))
      (node (ref "J901") (pin "23") (pinfunction "S_23") (pintype "passive"))
      (node (ref "J901") (pin "26") (pinfunction "S_26") (pintype "passive"))
      (node (ref "J901") (pin "29") (pinfunction "S_29") (pintype "passive"))
      (node (ref "J901") (pin "32") (pinfunction "S_32") (pintype "passive"))
      (node (ref "J901") (pin "35") (pinfunction "S_35") (pintype "passive"))
      (node (ref "J901") (pin "38") (pinfunction "S_38") (pintype "passive"))
      (node (ref "J901") (pin "41") (pinfunction "S_41") (pintype "passive"))
      (node (ref "J901") (pin "44") (pinfunction "S_44") (pintype "passive"))
      (node (ref "J901") (pin "47") (pinfunction "S_47") (pintype "passive"))
      (node (ref "J901") (pin "5") (pinfunction "S_5") (pintype "passive"))
      (node (ref "J901") (pin "8") (pinfunction "S_8") (pintype "passive"))
      (node (ref "R9") (pin "P$1") (pinfunction "1_P$1") (pintype "passive"))
      (node (ref "R922") (pin "P$2") (pinfunction "2_P$2") (pintype "passive"))
      (node (ref "U$2") (pin "P$20") (pinfunction "V2_P$20") (pintype "bidirectional"))
      (node (ref "U$4") (pin "P$7") (pinfunction "D_P$7") (pintype "passive"))
      (node (ref "U$4") (pin "P$8") (pinfunction "D_P$8") (pintype "passive"))
    )
    (net (code "237") (name "VDD_SERVO_IN") (class "Default")
      (node (ref "L901") (pin "P$2") (pinfunction "P$2_P$2") (pintype "bidirectional"))
      (node (ref "U$1001") (pin "1") (pinfunction "IN_1") (pintype "bidirectional"))
    )
    (net (code "238") (name "VDD_SERVO_SENS") (class "Default")
      (node (ref "R918") (pin "P$1") (pinfunction "1_P$1") (pintype "passive"))
      (node (ref "R919") (pin "P$2") (pinfunction "2_P$2") (pintype "passive"))
      (node (ref "U801") (pin "14") (pinfunction "PA4_14") (pintype "bidirectional"))
    )
    (net (code "239") (name "unconnected-(J301-4-PadID)") (class "Default")
      (node (ref "J301") (pin "ID") (pinfunction "4_ID") (pintype "passive"))
    )
    (net (code "240") (name "unconnected-(JX301A-S-Pad10)") (class "Default")
      (node (ref "JX301") (pin "10") (pinfunction "S_10") (pintype "passive"))
    )
    (net (code "241") (name "unconnected-(JX301F-S-Pad8)") (class "Default")
      (node (ref "JX301") (pin "8") (pinfunction "S_8") (pintype "passive"))
    )
    (net (code "242") (name "unconnected-(JX802A-S-Pad10)") (class "Default")
      (node (ref "JX802") (pin "10") (pinfunction "S_10") (pintype "passive"))
    )
    (net (code "243") (name "unconnected-(JX802F-S-Pad8)") (class "Default")
      (node (ref "JX802") (pin "8") (pinfunction "S_8") (pintype "passive"))
    )
    (net (code "244") (name "unconnected-(U$2-CAS-PadP$11)") (class "Default")
      (node (ref "U$2") (pin "P$11") (pinfunction "CAS_P$11") (pintype "bidirectional"))
    )
    (net (code "245") (name "unconnected-(U$2-EN-PadP$22)") (class "Default")
      (node (ref "U$2") (pin "P$22") (pinfunction "EN_P$22") (pintype "bidirectional"))
    )
    (net (code "246") (name "unconnected-(U$2-~{SHDN}-PadP$23)") (class "Default")
      (node (ref "U$2") (pin "P$23") (pinfunction "~{SHDN}_P$23") (pintype "bidirectional"))
    )
    (net (code "247") (name "unconnected-(U101I-PC0-Pad15)") (class "Default")
      (node (ref "U101") (pin "15") (pinfunction "PC0_15") (pintype "bidirectional"))
    )
    (net (code "248") (name "unconnected-(U101I-PC1-Pad16)") (class "Default")
      (node (ref "U101") (pin "16") (pinfunction "PC1_16") (pintype "bidirectional"))
    )
    (net (code "249") (name "unconnected-(U101I-PC2-Pad17)") (class "Default")
      (node (ref "U101") (pin "17") (pinfunction "PC2_17") (pintype "bidirectional"))
    )
    (net (code "250") (name "unconnected-(U101J-PD15-Pad62)") (class "Default")
      (node (ref "U101") (pin "62") (pinfunction "PD15_62") (pintype "bidirectional"))
    )
    (net (code "251") (name "unconnected-(U202-A1-Pad1)") (class "Default")
      (node (ref "U202") (pin "1") (pinfunction "A1_1") (pintype "bidirectional"))
    )
    (net (code "252") (name "unconnected-(U202-A2-Pad3)") (class "Default")
      (node (ref "U202") (pin "3") (pinfunction "A2_3") (pintype "bidirectional"))
    )
    (net (code "253") (name "unconnected-(U202-B1-Pad20)") (class "Default")
      (node (ref "U202") (pin "20") (pinfunction "B1_20") (pintype "bidirectional"))
    )
    (net (code "254") (name "unconnected-(U202-B2-Pad18)") (class "Default")
      (node (ref "U202") (pin "18") (pinfunction "B2_18") (pintype "bidirectional"))
    )
    (net (code "255") (name "unconnected-(U501-INT1-Pad7)") (class "Default")
      (node (ref "U501") (pin "7") (pinfunction "INT1_7") (pintype "output"))
    )
    (net (code "256") (name "unconnected-(U502-DEN-Pad8)") (class "Default")
      (node (ref "U502") (pin "8") (pinfunction "DEN_8") (pintype "bidirectional"))
    )
    (net (code "257") (name "unconnected-(U502-INT1-Pad7)") (class "Default")
      (node (ref "U502") (pin "7") (pinfunction "INT1_7") (pintype "bidirectional"))
    )
    (net (code "258") (name "unconnected-(U503-CSB1-Pad4)") (class "Default")
      (node (ref "U503") (pin "4") (pinfunction "CSB1_4") (pintype "bidirectional"))
    )
    (net (code "259") (name "unconnected-(U801B-PA11-Pad32)") (class "Default")
      (node (ref "U801") (pin "32") (pinfunction "PA11_32") (pintype "bidirectional"))
    )
    (net (code "260") (name "unconnected-(U801D-PB12-Pad25)") (class "Default")
      (node (ref "U801") (pin "25") (pinfunction "PB12_25") (pintype "bidirectional"))
    )
    (net (code "261") (name "unconnected-(U801E-PB6-Pad42)") (class "Default")
      (node (ref "U801") (pin "42") (pinfunction "PB6_42") (pintype "bidirectional"))
    )
    (net (code "262") (name "unconnected-(U801E-PB7-Pad43)") (class "Default")
      (node (ref "U801") (pin "43") (pinfunction "PB7_43") (pintype "bidirectional"))
    )
    (net (code "263") (name "unconnected-(U801F-PC14-Pad3)") (class "Default")
      (node (ref "U801") (pin "3") (pinfunction "PC14_3") (pintype "bidirectional"))
    )
    (net (code "264") (name "unconnected-(U801F-PC15-Pad4)") (class "Default")
      (node (ref "U801") (pin "4") (pinfunction "PC15_4") (pintype "bidirectional"))
    )
    (net (code "265") (name "unconnected-(U901-A7-Pad8)") (class "Default")
      (node (ref "U901") (pin "8") (pinfunction "A7_8") (pintype "bidirectional"))
    )
    (net (code "266") (name "unconnected-(U901-A8-Pad9)") (class "Default")
      (node (ref "U901") (pin "9") (pinfunction "A8_9") (pintype "bidirectional"))
    )
    (net (code "267") (name "unconnected-(U901-B7-Pad13)") (class "Default")
      (node (ref "U901") (pin "13") (pinfunction "B7_13") (pintype "bidirectional"))
    )
    (net (code "268") (name "unconnected-(U901-B8-Pad12)") (class "Default")
      (node (ref "U901") (pin "12") (pinfunction "B8_12") (pintype "bidirectional"))
    )
    (net (code "269") (name "~{ACCEL_MAG_CS}") (class "Default")
      (node (ref "U$1") (pin "6") (pinfunction "S_6") (pintype "passive"))
      (node (ref "U$501") (pin "8") (pinfunction "CS_8") (pintype "bidirectional"))
      (node (ref "U101") (pin "9") (pinfunction "PC15_9") (pintype "bidirectional"))
    )
    (net (code "270") (name "~{BARO_CS}") (class "Default")
      (node (ref "U101") (pin "88") (pinfunction "PD7_88") (pintype "bidirectional"))
      (node (ref "U503") (pin "5") (pinfunction "CSB2_5") (pintype "bidirectional"))
    )
    (net (code "271") (name "~{FMU-LED_AMBER}") (class "Default")
      (node (ref "R707") (pin "P$1") (pinfunction "1_P$1") (pintype "passive"))
      (node (ref "U101") (pin "43") (pinfunction "PE12_43") (pintype "bidirectional"))
    )
    (net (code "272") (name "~{FRAM_CS}") (class "Default")
      (node (ref "U101") (pin "57") (pinfunction "PD10_57") (pintype "bidirectional"))
      (node (ref "U102") (pin "1") (pinfunction "~{S}_1") (pintype "bidirectional"))
    )
    (net (code "273") (name "~{GYRO_CS}") (class "Default")
      (node (ref "U$1") (pin "7") (pinfunction "S_7") (pintype "passive"))
      (node (ref "U101") (pin "7") (pinfunction "PC13_7") (pintype "bidirectional"))
      (node (ref "U501") (pin "5") (pinfunction "CS_5") (pintype "input"))
      (node (ref "U502") (pin "5") (pinfunction "CS_5") (pintype "bidirectional"))
    )
    (net (code "274") (name "~{IO-LED_AMBER}") (class "Default")
      (node (ref "R709") (pin "P$1") (pinfunction "1_P$1") (pintype "passive"))
      (node (ref "U801") (pin "28") (pinfunction "PB15_28") (pintype "bidirectional"))
    )
    (net (code "275") (name "~{IO-LED_BLUE}") (class "Default")
      (node (ref "R712") (pin "P$1") (pinfunction "1_P$1") (pintype "passive"))
      (node (ref "U801") (pin "27") (pinfunction "PB14_27") (pintype "bidirectional"))
    )
    (net (code "276") (name "~{IO-LED_SAFETY}") (class "Default")
      (node (ref "R710") (pin "P$2") (pinfunction "2_P$2") (pintype "passive"))
      (node (ref "U801") (pin "26") (pinfunction "PB13_26") (pintype "bidirectional"))
    )
    (net (code "277") (name "~{SBUS_OUTPUT_EN}") (class "Default")
      (node (ref "U801") (pin "40") (pinfunction "PB4_40") (pintype "bidirectional"))
      (node (ref "U903") (pin "7") (pinfunction "~{2OE}_7") (pintype "input"))
    )
    (net (code "278") (name "~{SPI_EXT_NSS}") (class "Default")
      (node (ref "J403") (pin "P$5") (pinfunction "5_P$5") (pintype "passive"))
      (node (ref "U101") (pin "3") (pinfunction "PE4_3") (pintype "bidirectional"))
    )
    (net (code "279") (name "~{VBUS_VALID}") (class "Default")
      (node (ref "U$2") (pin "P$9") (pinfunction "~{VALID3}_P$9") (pintype "bidirectional"))
    )
    (net (code "280") (name "~{VDD_5V_HIPOWER_OC}") (class "Default")
      (node (ref "U$602") (pin "4") (pinfunction "~{FAULT}_4") (pintype "bidirectional"))
      (node (ref "U101") (pin "41") (pinfunction "PE10_41") (pintype "bidirectional"))
    )
    (net (code "281") (name "~{VDD_5V_PERIPH_EN}") (class "Default")
      (node (ref "R607") (pin "P$1") (pinfunction "1_P$1") (pintype "passive"))
      (node (ref "U$602") (pin "5") (pinfunction "~{CE}_5") (pintype "bidirectional"))
      (node (ref "U$604") (pin "5") (pinfunction "~{CE}_5") (pintype "bidirectional"))
      (node (ref "U101") (pin "67") (pinfunction "PA8_67") (pintype "bidirectional"))
    )
    (net (code "282") (name "~{VDD_5V_PERIPH_OC}") (class "Default")
      (node (ref "U$604") (pin "4") (pinfunction "~{FAULT}_4") (pintype "bidirectional"))
      (node (ref "U101") (pin "46") (pinfunction "PE15_46") (pintype "bidirectional"))
    )
    (net (code "283") (name "~{VDD_BRICK_VALID}") (class "Default")
      (node (ref "U$2") (pin "P$7") (pinfunction "~{VALID1}_P$7") (pintype "bidirectional"))
      (node (ref "U101") (pin "91") (pinfunction "PB5_91") (pintype "bidirectional"))
    )
    (net (code "284") (name "~{VDD_SERVO_VALID}") (class "Default")
      (node (ref "U$2") (pin "P$8") (pinfunction "~{VALID2}_P$8") (pintype "bidirectional"))
      (node (ref "U101") (pin "93") (pinfunction "PB7_93") (pintype "bidirectional"))
    )
  )
)
